# BMS.net
KiCad netlist of a schematic drawn in EAGLE
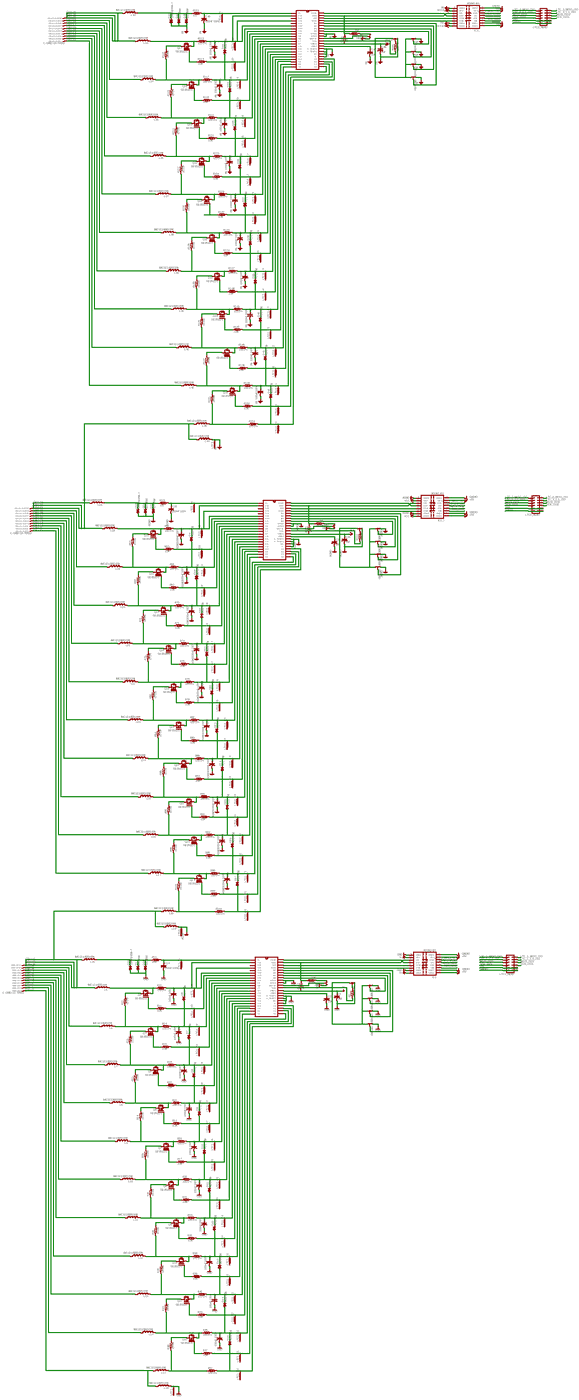
[diagram p0: schematic, sheet 1, overview]
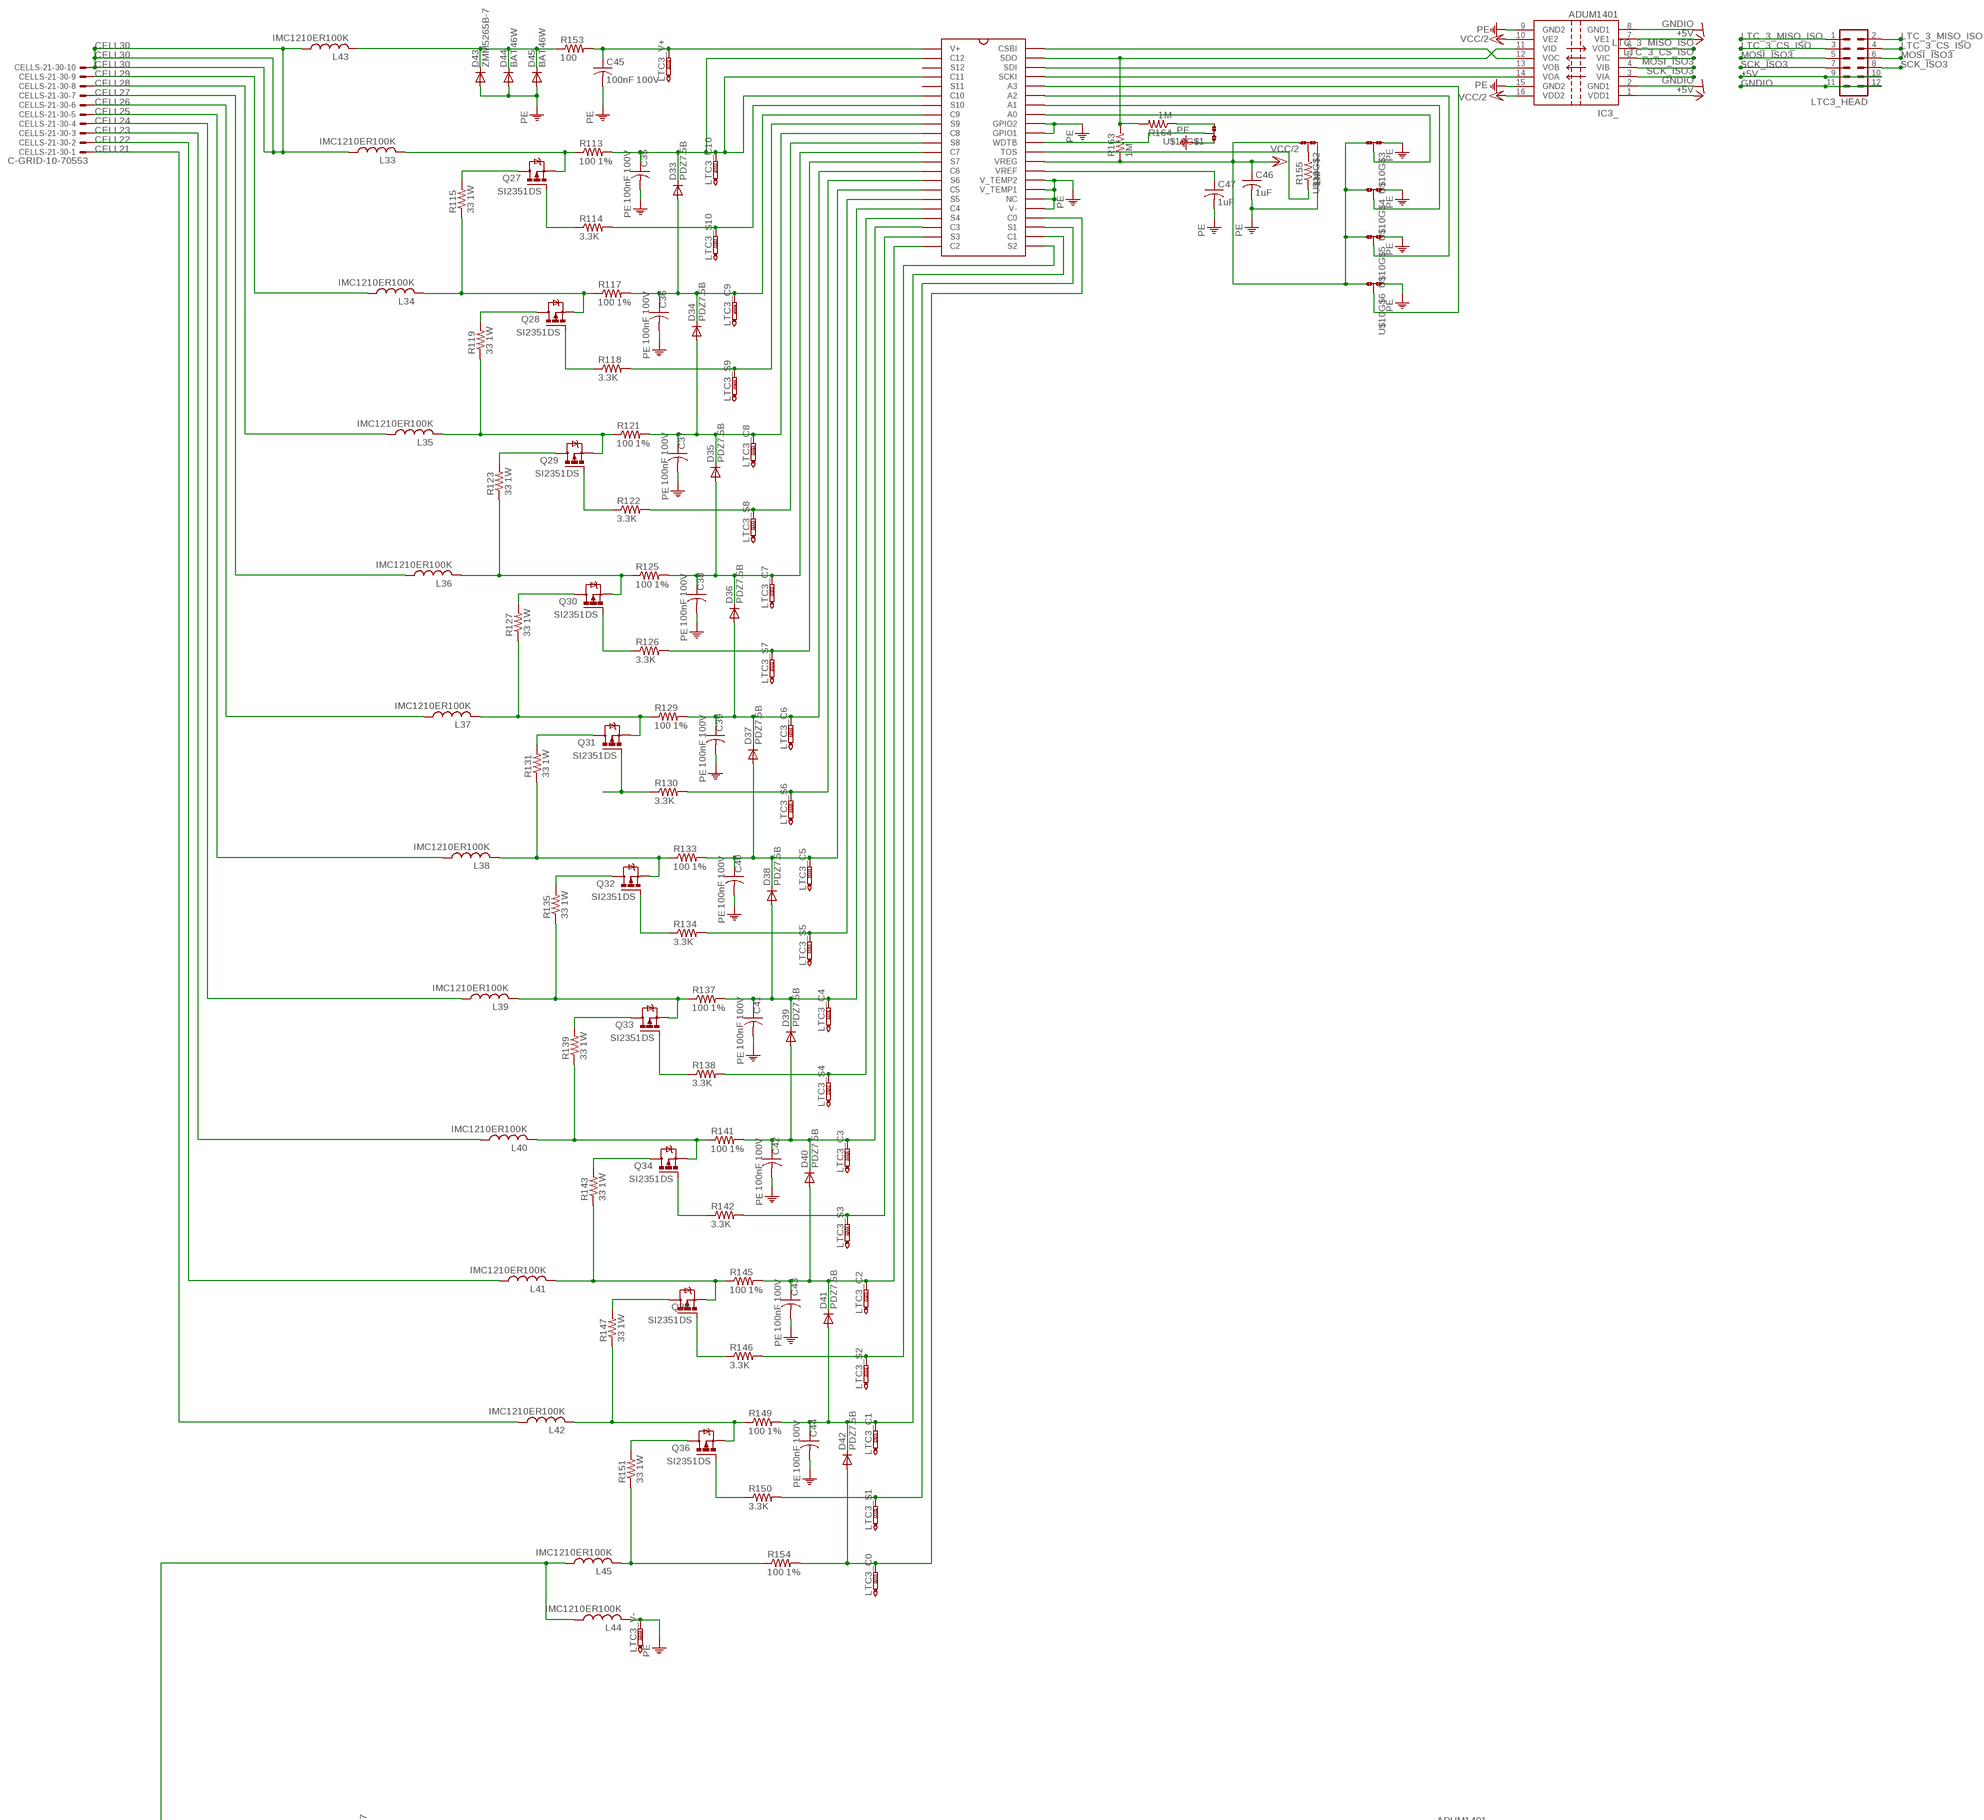
[diagram p1: schematic, sheet 1, part 1 of 4]
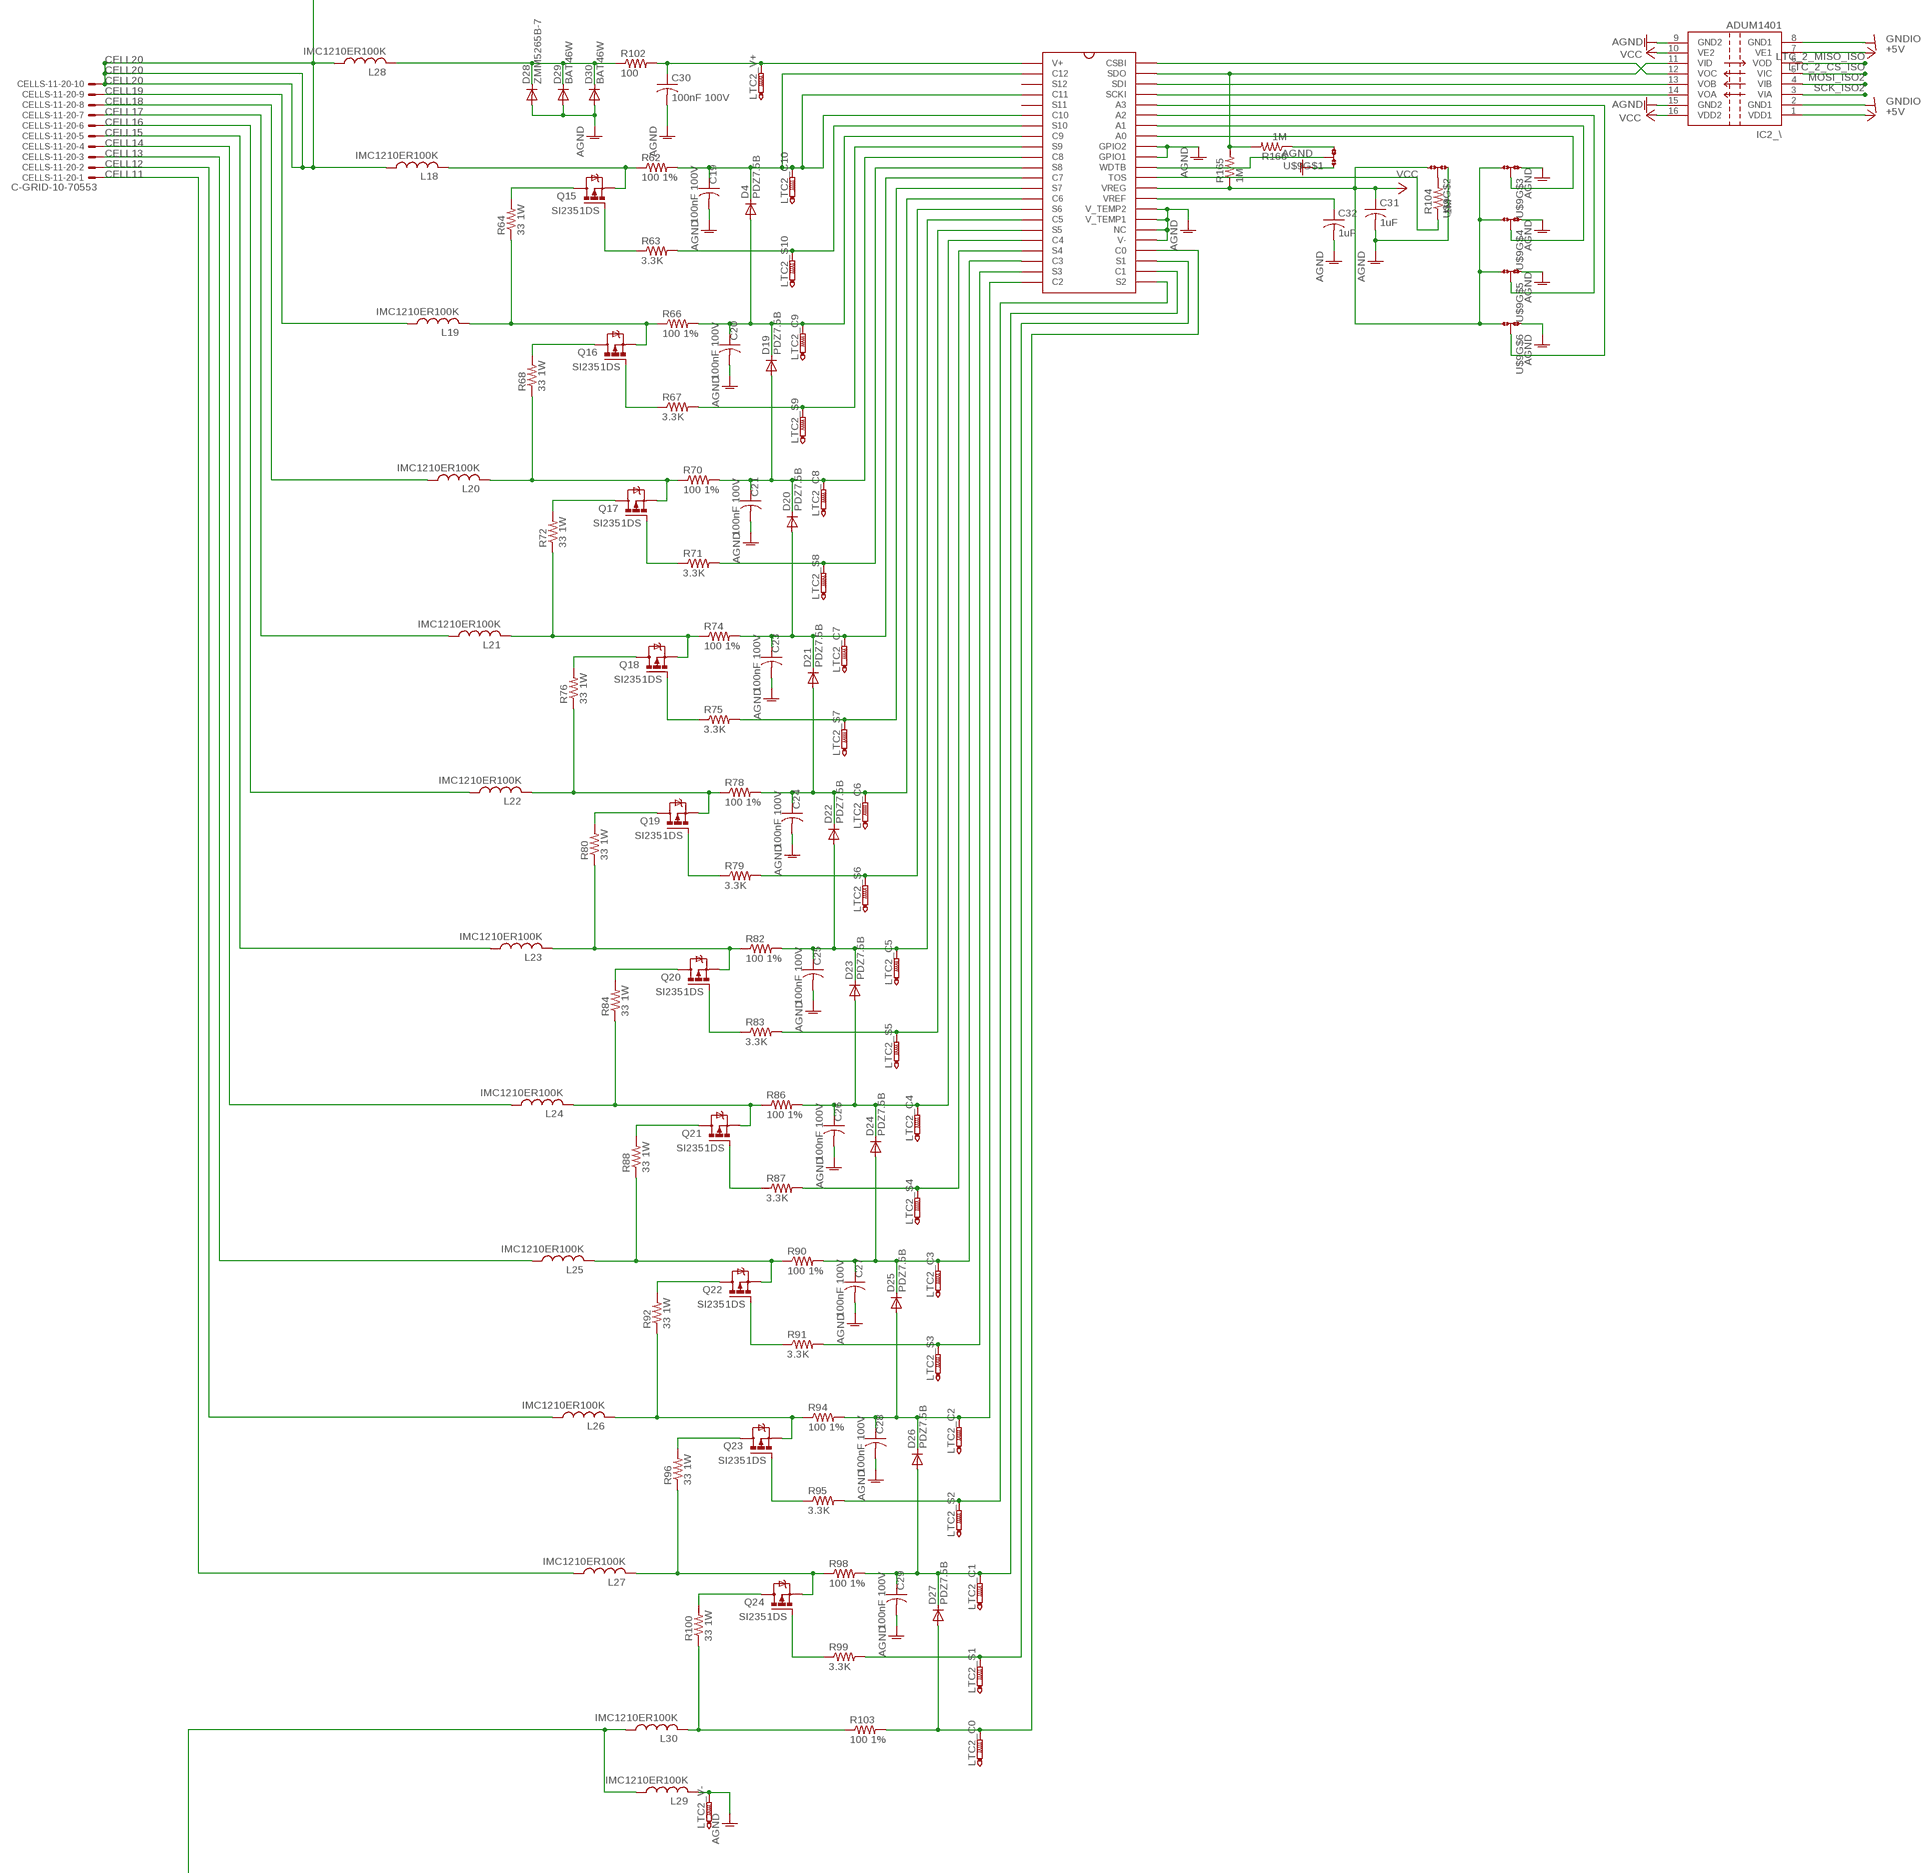
[diagram p2: schematic, sheet 1, part 2 of 4]
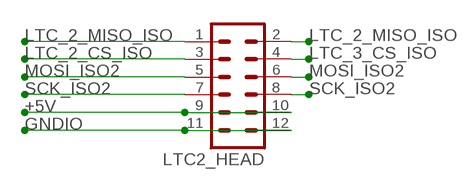
[diagram p3: schematic, sheet 1, part 3 of 4]
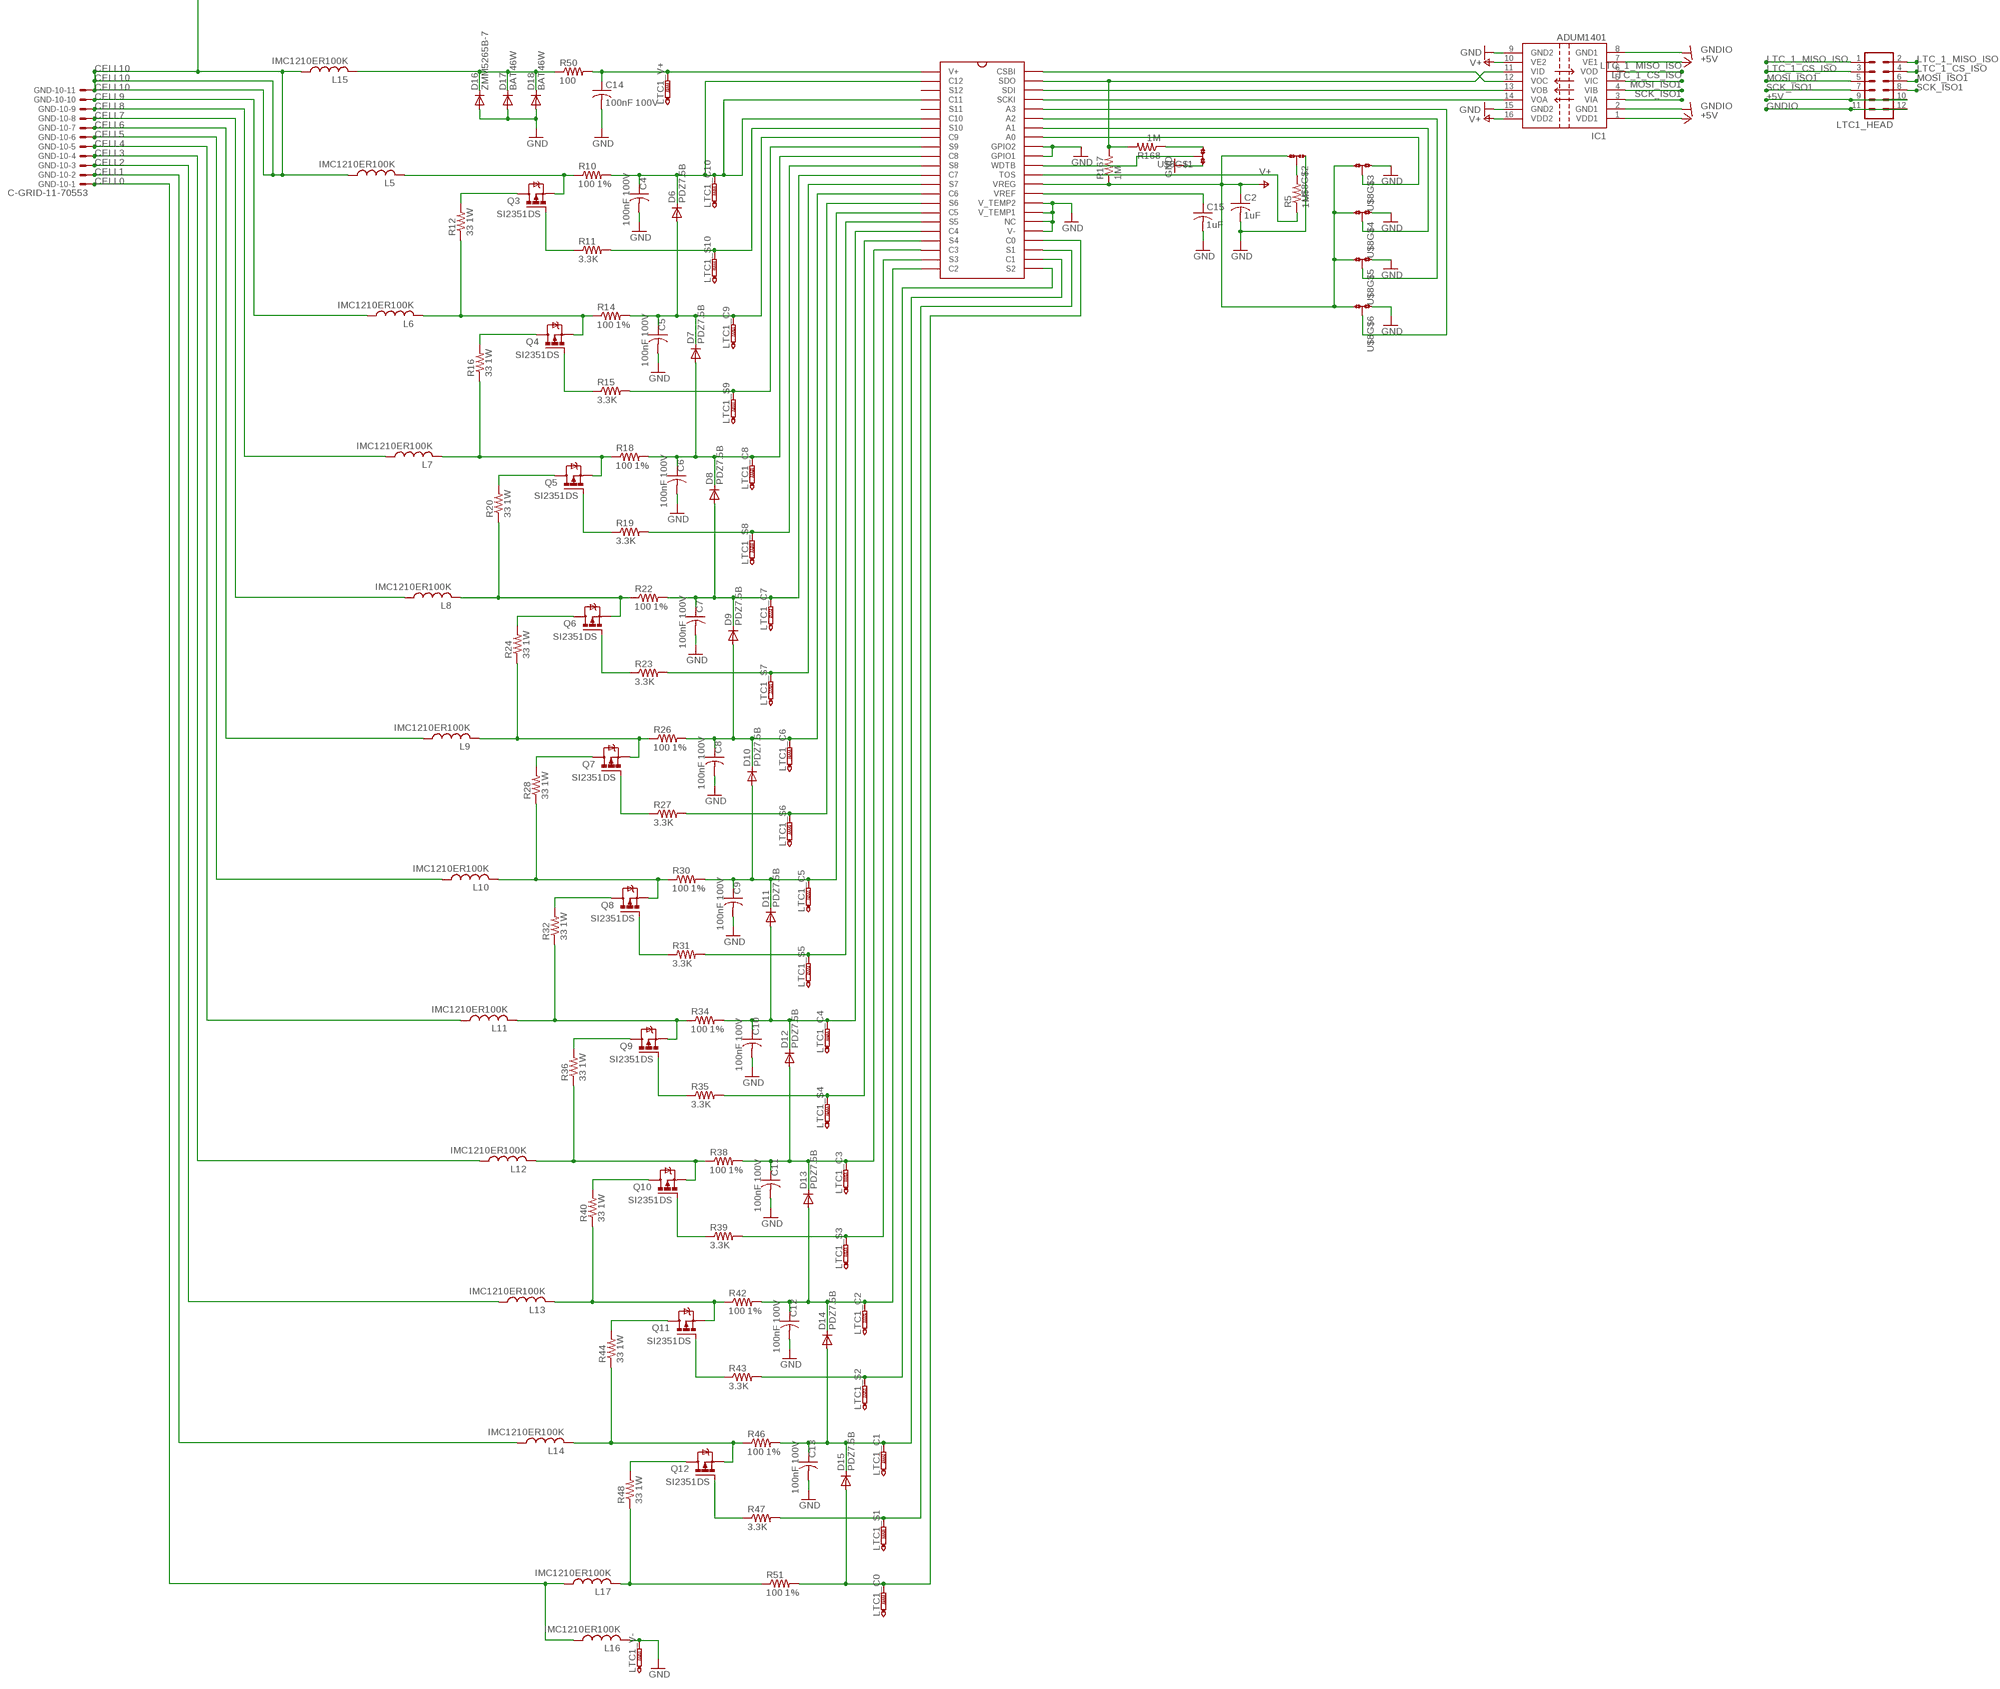
[diagram p4: schematic, sheet 1, part 4 of 4]
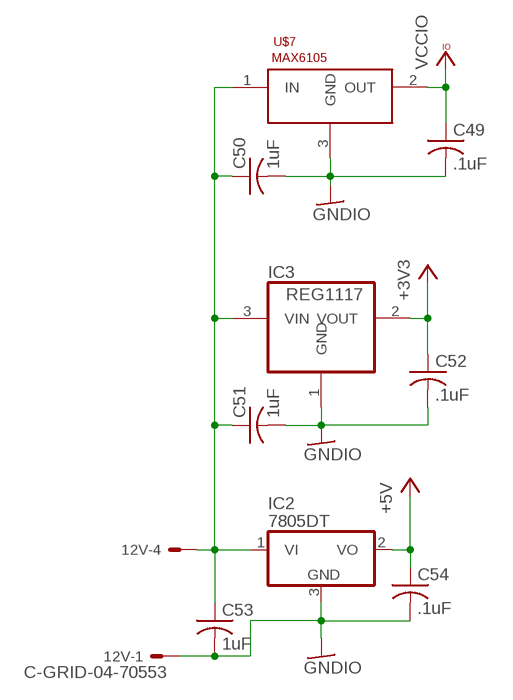
[diagram p5: schematic, sheet 2]
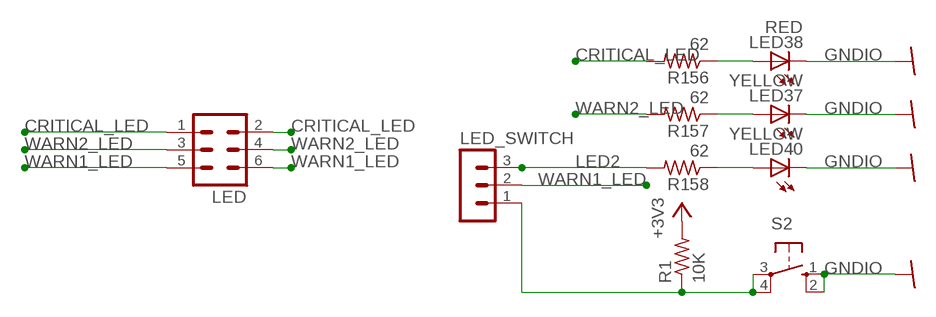
[diagram p6: schematic, sheet 3]
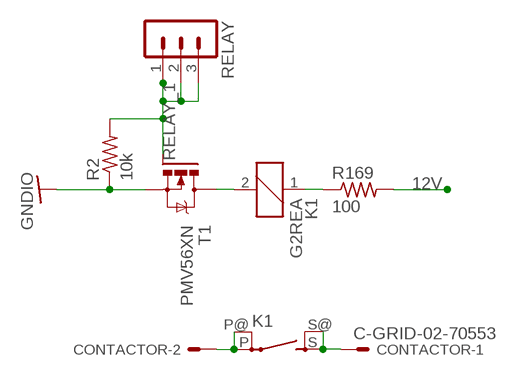
[diagram p7: schematic, sheet 4]
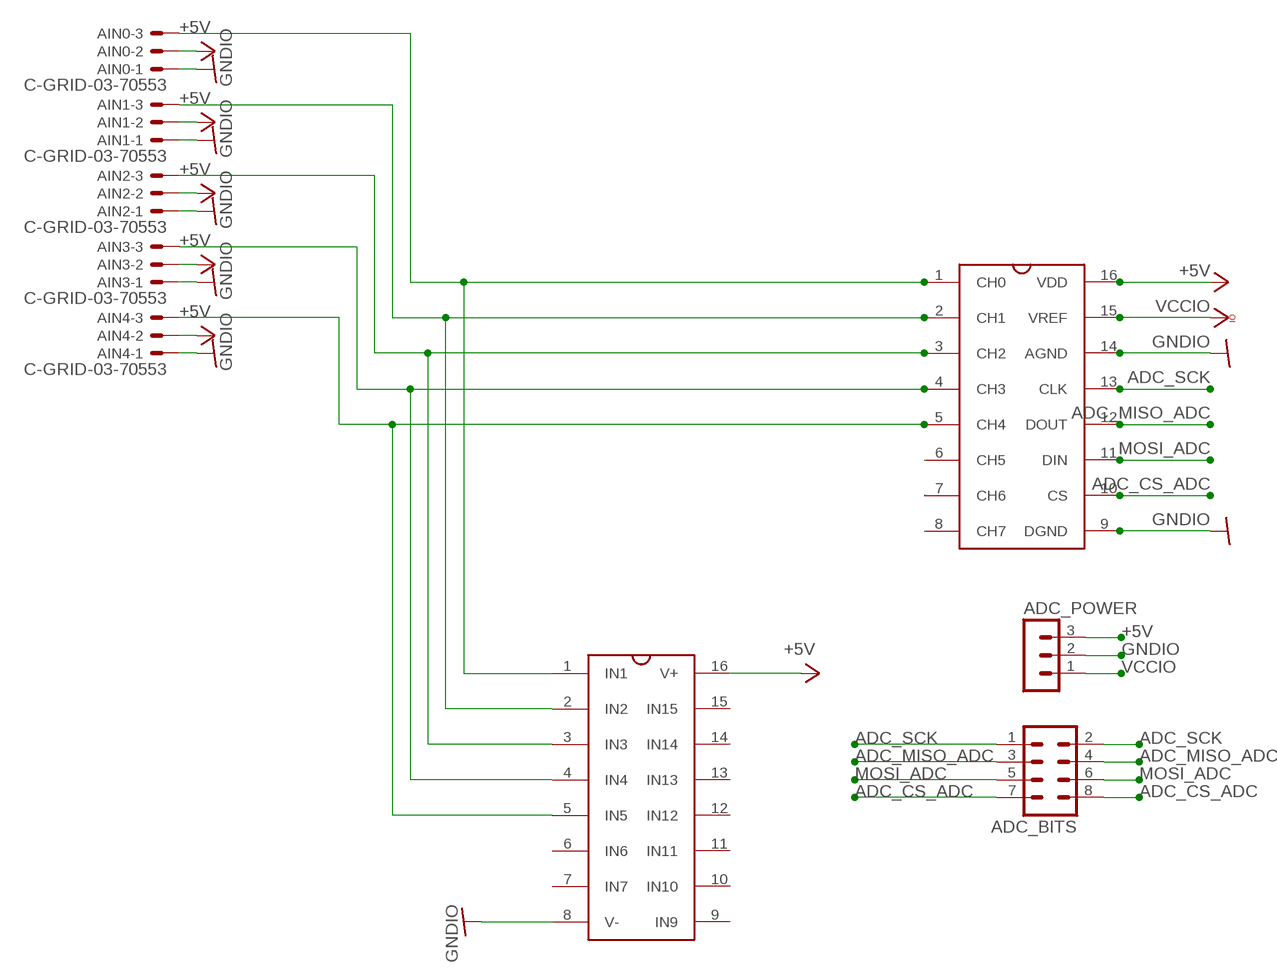
[diagram p8: schematic, sheet 5]
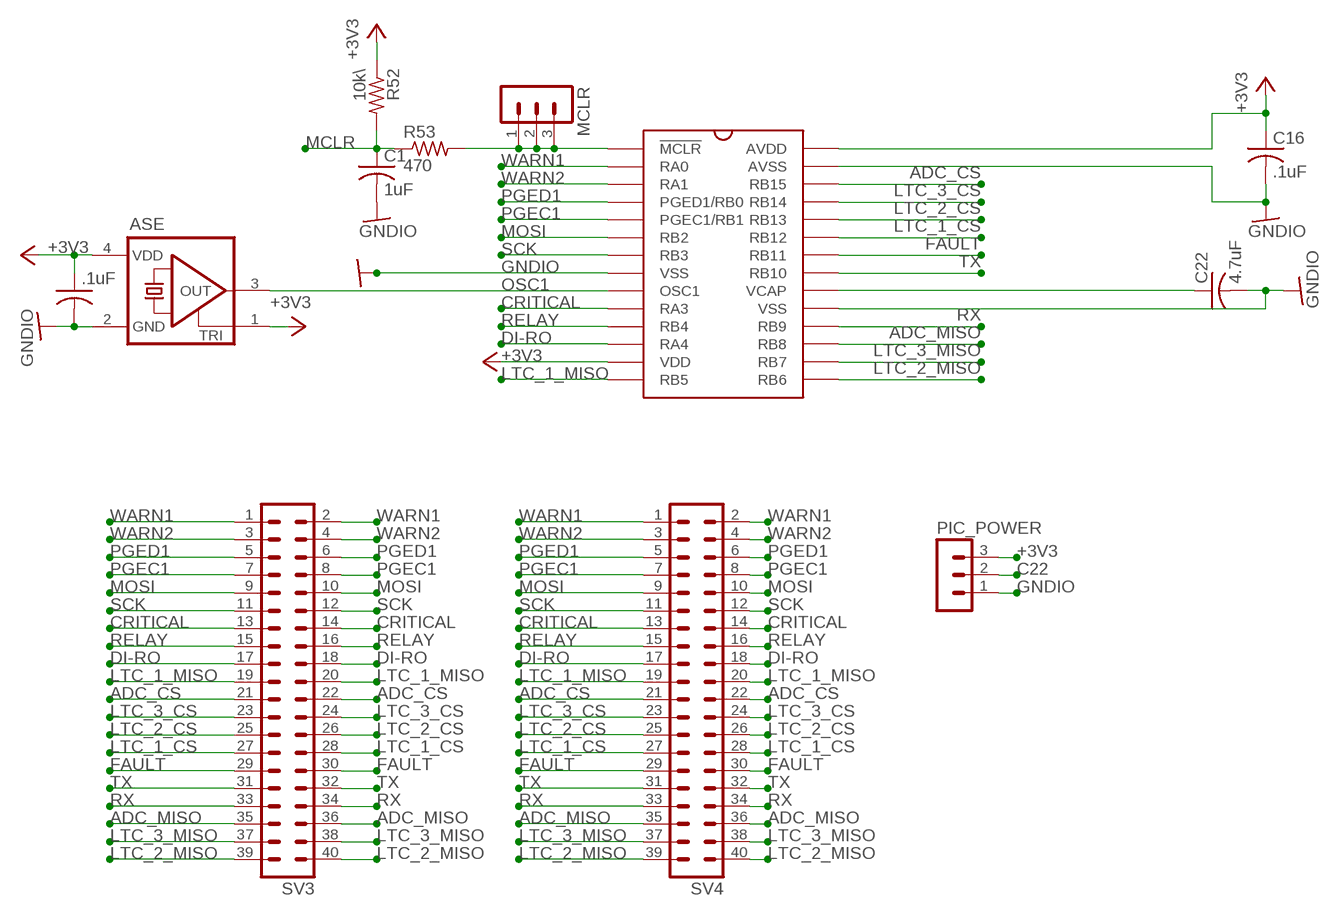
[diagram p9: schematic, sheet 6]
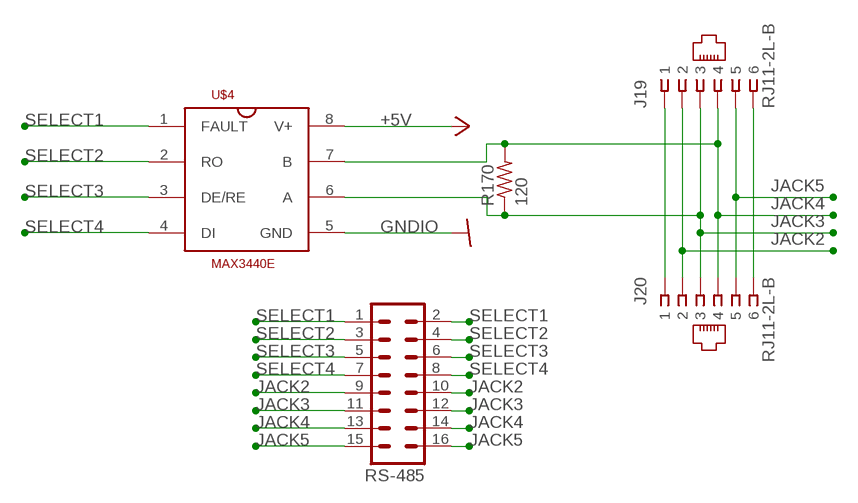
[diagram p10: schematic, sheet 7]
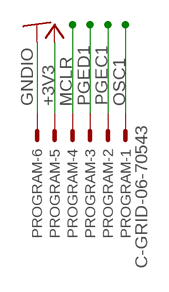
[diagram p11: schematic, sheet 8]

(export (version "E")
  (design (tool "Eeschema 10.0.6"))
  (components
    (comp (ref "C2")
      (value "1uF")
      (footprint "eagle-import:C1206")
      (libsource (lib "eagle-import") (part "C-USC1206"))
    )
    (comp (ref "C4")
      (value "100nF 100V")
      (footprint "eagle-import:C1206")
      (libsource (lib "eagle-import") (part "C-USC1206"))
    )
    (comp (ref "C5")
      (value "100nF 100V")
      (footprint "eagle-import:C1206")
      (libsource (lib "eagle-import") (part "C-USC1206"))
    )
    (comp (ref "C6")
      (value "100nF 100V")
      (footprint "eagle-import:C1206")
      (libsource (lib "eagle-import") (part "C-USC1206"))
    )
    (comp (ref "C7")
      (value "100nF 100V")
      (footprint "eagle-import:C1206")
      (libsource (lib "eagle-import") (part "C-USC1206"))
    )
    (comp (ref "C8")
      (value "100nF 100V")
      (footprint "eagle-import:C1206")
      (libsource (lib "eagle-import") (part "C-USC1206"))
    )
    (comp (ref "C9")
      (value "100nF 100V")
      (footprint "eagle-import:C1206")
      (libsource (lib "eagle-import") (part "C-USC1206"))
    )
    (comp (ref "C10")
      (value "100nF 100V")
      (footprint "eagle-import:C1206")
      (libsource (lib "eagle-import") (part "C-USC1206"))
    )
    (comp (ref "C11")
      (value "100nF 100V")
      (footprint "eagle-import:C1206")
      (libsource (lib "eagle-import") (part "C-USC1206"))
    )
    (comp (ref "C12")
      (value "100nF 100V")
      (footprint "eagle-import:C1206")
      (libsource (lib "eagle-import") (part "C-USC1206"))
    )
    (comp (ref "C13")
      (value "100nF 100V")
      (footprint "eagle-import:C1206")
      (libsource (lib "eagle-import") (part "C-USC1206"))
    )
    (comp (ref "C14")
      (value "100nF 100V")
      (footprint "eagle-import:C1206")
      (libsource (lib "eagle-import") (part "C-USC1206"))
    )
    (comp (ref "C15")
      (value "1uF")
      (footprint "eagle-import:C1206")
      (libsource (lib "eagle-import") (part "C-USC1206"))
    )
    (comp (ref "C19")
      (value "100nF 100V")
      (footprint "eagle-import:C1206")
      (libsource (lib "eagle-import") (part "C-USC1206"))
    )
    (comp (ref "C20")
      (value "100nF 100V")
      (footprint "eagle-import:C1206")
      (libsource (lib "eagle-import") (part "C-USC1206"))
    )
    (comp (ref "C21")
      (value "100nF 100V")
      (footprint "eagle-import:C1206")
      (libsource (lib "eagle-import") (part "C-USC1206"))
    )
    (comp (ref "C23")
      (value "100nF 100V")
      (footprint "eagle-import:C1206")
      (libsource (lib "eagle-import") (part "C-USC1206"))
    )
    (comp (ref "C24")
      (value "100nF 100V")
      (footprint "eagle-import:C1206")
      (libsource (lib "eagle-import") (part "C-USC1206"))
    )
    (comp (ref "C25")
      (value "100nF 100V")
      (footprint "eagle-import:C1206")
      (libsource (lib "eagle-import") (part "C-USC1206"))
    )
    (comp (ref "C26")
      (value "100nF 100V")
      (footprint "eagle-import:C1206")
      (libsource (lib "eagle-import") (part "C-USC1206"))
    )
    (comp (ref "C27")
      (value "100nF 100V")
      (footprint "eagle-import:C1206")
      (libsource (lib "eagle-import") (part "C-USC1206"))
    )
    (comp (ref "C28")
      (value "100nF 100V")
      (footprint "eagle-import:C1206")
      (libsource (lib "eagle-import") (part "C-USC1206"))
    )
    (comp (ref "C29")
      (value "100nF 100V")
      (footprint "eagle-import:C1206")
      (libsource (lib "eagle-import") (part "C-USC1206"))
    )
    (comp (ref "C30")
      (value "100nF 100V")
      (footprint "eagle-import:C1206")
      (libsource (lib "eagle-import") (part "C-USC1206"))
    )
    (comp (ref "C31")
      (value "1uF")
      (footprint "eagle-import:C1206")
      (libsource (lib "eagle-import") (part "C-USC1206"))
    )
    (comp (ref "C32")
      (value "1uF")
      (footprint "eagle-import:C1206")
      (libsource (lib "eagle-import") (part "C-USC1206"))
    )
    (comp (ref "C35")
      (value "100nF 100V")
      (footprint "eagle-import:C1206")
      (libsource (lib "eagle-import") (part "C-USC1206"))
    )
    (comp (ref "C36")
      (value "100nF 100V")
      (footprint "eagle-import:C1206")
      (libsource (lib "eagle-import") (part "C-USC1206"))
    )
    (comp (ref "C37")
      (value "100nF 100V")
      (footprint "eagle-import:C1206")
      (libsource (lib "eagle-import") (part "C-USC1206"))
    )
    (comp (ref "C38")
      (value "100nF 100V")
      (footprint "eagle-import:C1206")
      (libsource (lib "eagle-import") (part "C-USC1206"))
    )
    (comp (ref "C39")
      (value "100nF 100V")
      (footprint "eagle-import:C1206")
      (libsource (lib "eagle-import") (part "C-USC1206"))
    )
    (comp (ref "C40")
      (value "100nF 100V")
      (footprint "eagle-import:C1206")
      (libsource (lib "eagle-import") (part "C-USC1206"))
    )
    (comp (ref "C41")
      (value "100nF 100V")
      (footprint "eagle-import:C1206")
      (libsource (lib "eagle-import") (part "C-USC1206"))
    )
    (comp (ref "C42")
      (value "100nF 100V")
      (footprint "eagle-import:C1206")
      (libsource (lib "eagle-import") (part "C-USC1206"))
    )
    (comp (ref "C43")
      (value "100nF 100V")
      (footprint "eagle-import:C1206")
      (libsource (lib "eagle-import") (part "C-USC1206"))
    )
    (comp (ref "C44")
      (value "100nF 100V")
      (footprint "eagle-import:C1206")
      (libsource (lib "eagle-import") (part "C-USC1206"))
    )
    (comp (ref "C45")
      (value "100nF 100V")
      (footprint "eagle-import:C1206")
      (libsource (lib "eagle-import") (part "C-USC1206"))
    )
    (comp (ref "C46")
      (value "1uF")
      (footprint "eagle-import:C1206")
      (libsource (lib "eagle-import") (part "C-USC1206"))
    )
    (comp (ref "C47")
      (value "1uF")
      (footprint "eagle-import:C1206")
      (libsource (lib "eagle-import") (part "C-USC1206"))
    )
    (comp (ref "CELLS-11-20")
      (value "C-GRID-10-70553")
      (footprint "eagle-import:70553-10")
      (libsource (lib "eagle-import") (part "C-GRID-10-70553"))
    )
    (comp (ref "CELLS-21-30")
      (value "C-GRID-10-70553")
      (footprint "eagle-import:70553-10")
      (libsource (lib "eagle-import") (part "C-GRID-10-70553"))
    )
    (comp (ref "D4")
      (value "PDZ7.5B")
      (footprint "eagle-import:SOD323-W")
      (libsource (lib "eagle-import") (part "DIODE-SOD323-W"))
    )
    (comp (ref "D6")
      (value "PDZ7.5B")
      (footprint "eagle-import:SOD323-W")
      (libsource (lib "eagle-import") (part "DIODE-SOD323-W"))
    )
    (comp (ref "D7")
      (value "PDZ7.5B")
      (footprint "eagle-import:SOD323-W")
      (libsource (lib "eagle-import") (part "DIODE-SOD323-W"))
    )
    (comp (ref "D8")
      (value "PDZ7.5B")
      (footprint "eagle-import:SOD323-W")
      (libsource (lib "eagle-import") (part "DIODE-SOD323-W"))
    )
    (comp (ref "D9")
      (value "PDZ7.5B")
      (footprint "eagle-import:SOD323-W")
      (libsource (lib "eagle-import") (part "DIODE-SOD323-W"))
    )
    (comp (ref "D10")
      (value "PDZ7.5B")
      (footprint "eagle-import:SOD323-W")
      (libsource (lib "eagle-import") (part "DIODE-SOD323-W"))
    )
    (comp (ref "D11")
      (value "PDZ7.5B")
      (footprint "eagle-import:SOD323-W")
      (libsource (lib "eagle-import") (part "DIODE-SOD323-W"))
    )
    (comp (ref "D12")
      (value "PDZ7.5B")
      (footprint "eagle-import:SOD323-W")
      (libsource (lib "eagle-import") (part "DIODE-SOD323-W"))
    )
    (comp (ref "D13")
      (value "PDZ7.5B")
      (footprint "eagle-import:SOD323-W")
      (libsource (lib "eagle-import") (part "DIODE-SOD323-W"))
    )
    (comp (ref "D14")
      (value "PDZ7.5B")
      (footprint "eagle-import:SOD323-W")
      (libsource (lib "eagle-import") (part "DIODE-SOD323-W"))
    )
    (comp (ref "D15")
      (value "PDZ7.5B")
      (footprint "eagle-import:SOD323-W")
      (libsource (lib "eagle-import") (part "DIODE-SOD323-W"))
    )
    (comp (ref "D16")
      (value "ZMM5265B-7")
      (footprint "eagle-import:MINIMELF")
      (libsource (lib "eagle-import") (part "DIODE-MINIMELF"))
    )
    (comp (ref "D17")
      (value "BAT46W")
      (footprint "eagle-import:SOD123")
      (libsource (lib "eagle-import") (part "DIODE-SOD123"))
    )
    (comp (ref "D18")
      (value "BAT46W")
      (footprint "eagle-import:SOD123")
      (libsource (lib "eagle-import") (part "DIODE-SOD123"))
    )
    (comp (ref "D19")
      (value "PDZ7.5B")
      (footprint "eagle-import:SOD323-W")
      (libsource (lib "eagle-import") (part "DIODE-SOD323-W"))
    )
    (comp (ref "D20")
      (value "PDZ7.5B")
      (footprint "eagle-import:SOD323-W")
      (libsource (lib "eagle-import") (part "DIODE-SOD323-W"))
    )
    (comp (ref "D21")
      (value "PDZ7.5B")
      (footprint "eagle-import:SOD323-W")
      (libsource (lib "eagle-import") (part "DIODE-SOD323-W"))
    )
    (comp (ref "D22")
      (value "PDZ7.5B")
      (footprint "eagle-import:SOD323-W")
      (libsource (lib "eagle-import") (part "DIODE-SOD323-W"))
    )
    (comp (ref "D23")
      (value "PDZ7.5B")
      (footprint "eagle-import:SOD323-W")
      (libsource (lib "eagle-import") (part "DIODE-SOD323-W"))
    )
    (comp (ref "D24")
      (value "PDZ7.5B")
      (footprint "eagle-import:SOD323-W")
      (libsource (lib "eagle-import") (part "DIODE-SOD323-W"))
    )
    (comp (ref "D25")
      (value "PDZ7.5B")
      (footprint "eagle-import:SOD323-W")
      (libsource (lib "eagle-import") (part "DIODE-SOD323-W"))
    )
    (comp (ref "D26")
      (value "PDZ7.5B")
      (footprint "eagle-import:SOD323-W")
      (libsource (lib "eagle-import") (part "DIODE-SOD323-W"))
    )
    (comp (ref "D27")
      (value "PDZ7.5B")
      (footprint "eagle-import:SOD323-W")
      (libsource (lib "eagle-import") (part "DIODE-SOD323-W"))
    )
    (comp (ref "D28")
      (value "ZMM5265B-7")
      (footprint "eagle-import:MINIMELF")
      (libsource (lib "eagle-import") (part "DIODE-MINIMELF"))
    )
    (comp (ref "D29")
      (value "BAT46W")
      (footprint "eagle-import:SOD123")
      (libsource (lib "eagle-import") (part "DIODE-SOD123"))
    )
    (comp (ref "D30")
      (value "BAT46W")
      (footprint "eagle-import:SOD123")
      (libsource (lib "eagle-import") (part "DIODE-SOD123"))
    )
    (comp (ref "D33")
      (value "PDZ7.5B")
      (footprint "eagle-import:SOD323-W")
      (libsource (lib "eagle-import") (part "DIODE-SOD323-W"))
    )
    (comp (ref "D34")
      (value "PDZ7.5B")
      (footprint "eagle-import:SOD323-W")
      (libsource (lib "eagle-import") (part "DIODE-SOD323-W"))
    )
    (comp (ref "D35")
      (value "PDZ7.5B")
      (footprint "eagle-import:SOD323-W")
      (libsource (lib "eagle-import") (part "DIODE-SOD323-W"))
    )
    (comp (ref "D36")
      (value "PDZ7.5B")
      (footprint "eagle-import:SOD323-W")
      (libsource (lib "eagle-import") (part "DIODE-SOD323-W"))
    )
    (comp (ref "D37")
      (value "PDZ7.5B")
      (footprint "eagle-import:SOD323-W")
      (libsource (lib "eagle-import") (part "DIODE-SOD323-W"))
    )
    (comp (ref "D38")
      (value "PDZ7.5B")
      (footprint "eagle-import:SOD323-W")
      (libsource (lib "eagle-import") (part "DIODE-SOD323-W"))
    )
    (comp (ref "D39")
      (value "PDZ7.5B")
      (footprint "eagle-import:SOD323-W")
      (libsource (lib "eagle-import") (part "DIODE-SOD323-W"))
    )
    (comp (ref "D40")
      (value "PDZ7.5B")
      (footprint "eagle-import:SOD323-W")
      (libsource (lib "eagle-import") (part "DIODE-SOD323-W"))
    )
    (comp (ref "D41")
      (value "PDZ7.5B")
      (footprint "eagle-import:SOD323-W")
      (libsource (lib "eagle-import") (part "DIODE-SOD323-W"))
    )
    (comp (ref "D42")
      (value "PDZ7.5B")
      (footprint "eagle-import:SOD323-W")
      (libsource (lib "eagle-import") (part "DIODE-SOD323-W"))
    )
    (comp (ref "D43")
      (value "ZMM5265B-7")
      (footprint "eagle-import:MINIMELF")
      (libsource (lib "eagle-import") (part "DIODE-MINIMELF"))
    )
    (comp (ref "D44")
      (value "BAT46W")
      (footprint "eagle-import:SOD123")
      (libsource (lib "eagle-import") (part "DIODE-SOD123"))
    )
    (comp (ref "D45")
      (value "BAT46W")
      (footprint "eagle-import:SOD123")
      (libsource (lib "eagle-import") (part "DIODE-SOD123"))
    )
    (comp (ref "GND-10")
      (value "C-GRID-11-70553")
      (footprint "eagle-import:70553-11")
      (libsource (lib "eagle-import") (part "C-GRID-11-70553"))
    )
    (comp (ref "IC1")
      (value "ADUM1401")
      (footprint "eagle-import:SO16W")
      (libsource (lib "eagle-import") (part "ADUM1401"))
    )
    (comp (ref "IC2_\\")
      (value "ADUM1401")
      (footprint "eagle-import:SO16W")
      (libsource (lib "eagle-import") (part "ADUM1401"))
    )
    (comp (ref "IC3_")
      (value "ADUM1401")
      (footprint "eagle-import:SO16W")
      (libsource (lib "eagle-import") (part "ADUM1401"))
    )
    (comp (ref "L5")
      (value "IMC1210ER100K")
      (footprint "eagle-import:L3225M")
      (libsource (lib "eagle-import") (part "L-USL3225M"))
    )
    (comp (ref "L6")
      (value "IMC1210ER100K")
      (footprint "eagle-import:L3225M")
      (libsource (lib "eagle-import") (part "L-USL3225M"))
    )
    (comp (ref "L7")
      (value "IMC1210ER100K")
      (footprint "eagle-import:L3225M")
      (libsource (lib "eagle-import") (part "L-USL3225M"))
    )
    (comp (ref "L8")
      (value "IMC1210ER100K")
      (footprint "eagle-import:L3225M")
      (libsource (lib "eagle-import") (part "L-USL3225M"))
    )
    (comp (ref "L9")
      (value "IMC1210ER100K")
      (footprint "eagle-import:L3225M")
      (libsource (lib "eagle-import") (part "L-USL3225M"))
    )
    (comp (ref "L10")
      (value "IMC1210ER100K")
      (footprint "eagle-import:L3225M")
      (libsource (lib "eagle-import") (part "L-USL3225M"))
    )
    (comp (ref "L11")
      (value "IMC1210ER100K")
      (footprint "eagle-import:L3225M")
      (libsource (lib "eagle-import") (part "L-USL3225M"))
    )
    (comp (ref "L12")
      (value "IMC1210ER100K")
      (footprint "eagle-import:L3225M")
      (libsource (lib "eagle-import") (part "L-USL3225M"))
    )
    (comp (ref "L13")
      (value "IMC1210ER100K")
      (footprint "eagle-import:L3225M")
      (libsource (lib "eagle-import") (part "L-USL3225M"))
    )
    (comp (ref "L14")
      (value "IMC1210ER100K")
      (footprint "eagle-import:L3225M")
      (libsource (lib "eagle-import") (part "L-USL3225M"))
    )
    (comp (ref "L15")
      (value "IMC1210ER100K")
      (footprint "eagle-import:L3225M")
      (libsource (lib "eagle-import") (part "L-USL3225M"))
    )
    (comp (ref "L16")
      (value "IMC1210ER100K")
      (footprint "eagle-import:L3225M")
      (libsource (lib "eagle-import") (part "L-USL3225M"))
    )
    (comp (ref "L17")
      (value "IMC1210ER100K")
      (footprint "eagle-import:L3225M")
      (libsource (lib "eagle-import") (part "L-USL3225M"))
    )
    (comp (ref "L18")
      (value "IMC1210ER100K")
      (footprint "eagle-import:L3225M")
      (libsource (lib "eagle-import") (part "L-USL3225M"))
    )
    (comp (ref "L19")
      (value "IMC1210ER100K")
      (footprint "eagle-import:L3225M")
      (libsource (lib "eagle-import") (part "L-USL3225M"))
    )
    (comp (ref "L20")
      (value "IMC1210ER100K")
      (footprint "eagle-import:L3225M")
      (libsource (lib "eagle-import") (part "L-USL3225M"))
    )
    (comp (ref "L21")
      (value "IMC1210ER100K")
      (footprint "eagle-import:L3225M")
      (libsource (lib "eagle-import") (part "L-USL3225M"))
    )
    (comp (ref "L22")
      (value "IMC1210ER100K")
      (footprint "eagle-import:L3225M")
      (libsource (lib "eagle-import") (part "L-USL3225M"))
    )
    (comp (ref "L23")
      (value "IMC1210ER100K")
      (footprint "eagle-import:L3225M")
      (libsource (lib "eagle-import") (part "L-USL3225M"))
    )
    (comp (ref "L24")
      (value "IMC1210ER100K")
      (footprint "eagle-import:L3225M")
      (libsource (lib "eagle-import") (part "L-USL3225M"))
    )
    (comp (ref "L25")
      (value "IMC1210ER100K")
      (footprint "eagle-import:L3225M")
      (libsource (lib "eagle-import") (part "L-USL3225M"))
    )
    (comp (ref "L26")
      (value "IMC1210ER100K")
      (footprint "eagle-import:L3225M")
      (libsource (lib "eagle-import") (part "L-USL3225M"))
    )
    (comp (ref "L27")
      (value "IMC1210ER100K")
      (footprint "eagle-import:L3225M")
      (libsource (lib "eagle-import") (part "L-USL3225M"))
    )
    (comp (ref "L28")
      (value "IMC1210ER100K")
      (footprint "eagle-import:L3225M")
      (libsource (lib "eagle-import") (part "L-USL3225M"))
    )
    (comp (ref "L29")
      (value "IMC1210ER100K")
      (footprint "eagle-import:L3225M")
      (libsource (lib "eagle-import") (part "L-USL3225M"))
    )
    (comp (ref "L30")
      (value "IMC1210ER100K")
      (footprint "eagle-import:L3225M")
      (libsource (lib "eagle-import") (part "L-USL3225M"))
    )
    (comp (ref "L33")
      (value "IMC1210ER100K")
      (footprint "eagle-import:L3225M")
      (libsource (lib "eagle-import") (part "L-USL3225M"))
    )
    (comp (ref "L34")
      (value "IMC1210ER100K")
      (footprint "eagle-import:L3225M")
      (libsource (lib "eagle-import") (part "L-USL3225M"))
    )
    (comp (ref "L35")
      (value "IMC1210ER100K")
      (footprint "eagle-import:L3225M")
      (libsource (lib "eagle-import") (part "L-USL3225M"))
    )
    (comp (ref "L36")
      (value "IMC1210ER100K")
      (footprint "eagle-import:L3225M")
      (libsource (lib "eagle-import") (part "L-USL3225M"))
    )
    (comp (ref "L37")
      (value "IMC1210ER100K")
      (footprint "eagle-import:L3225M")
      (libsource (lib "eagle-import") (part "L-USL3225M"))
    )
    (comp (ref "L38")
      (value "IMC1210ER100K")
      (footprint "eagle-import:L3225M")
      (libsource (lib "eagle-import") (part "L-USL3225M"))
    )
    (comp (ref "L39")
      (value "IMC1210ER100K")
      (footprint "eagle-import:L3225M")
      (libsource (lib "eagle-import") (part "L-USL3225M"))
    )
    (comp (ref "L40")
      (value "IMC1210ER100K")
      (footprint "eagle-import:L3225M")
      (libsource (lib "eagle-import") (part "L-USL3225M"))
    )
    (comp (ref "L41")
      (value "IMC1210ER100K")
      (footprint "eagle-import:L3225M")
      (libsource (lib "eagle-import") (part "L-USL3225M"))
    )
    (comp (ref "L42")
      (value "IMC1210ER100K")
      (footprint "eagle-import:L3225M")
      (libsource (lib "eagle-import") (part "L-USL3225M"))
    )
    (comp (ref "L43")
      (value "IMC1210ER100K")
      (footprint "eagle-import:L3225M")
      (libsource (lib "eagle-import") (part "L-USL3225M"))
    )
    (comp (ref "L44")
      (value "IMC1210ER100K")
      (footprint "eagle-import:L3225M")
      (libsource (lib "eagle-import") (part "L-USL3225M"))
    )
    (comp (ref "L45")
      (value "IMC1210ER100K")
      (footprint "eagle-import:L3225M")
      (libsource (lib "eagle-import") (part "L-USL3225M"))
    )
    (comp (ref "LTC1")
      (value "LTC6803-4")
      (footprint "eagle-import:SSOP44")
      (libsource (lib "eagle-import") (part "LTC6803-4"))
    )
    (comp (ref "LTC1_C0")
      (value "TESTPAD-20MIL")
      (footprint "eagle-import:20MIL")
      (libsource (lib "eagle-import") (part "TESTPAD-20MIL"))
    )
    (comp (ref "LTC1_C1")
      (value "TESTPAD-20MIL")
      (footprint "eagle-import:20MIL")
      (libsource (lib "eagle-import") (part "TESTPAD-20MIL"))
    )
    (comp (ref "LTC1_C2")
      (value "TESTPAD-20MIL")
      (footprint "eagle-import:20MIL")
      (libsource (lib "eagle-import") (part "TESTPAD-20MIL"))
    )
    (comp (ref "LTC1_C3")
      (value "TESTPAD-20MIL")
      (footprint "eagle-import:20MIL")
      (libsource (lib "eagle-import") (part "TESTPAD-20MIL"))
    )
    (comp (ref "LTC1_C4")
      (value "TESTPAD-20MIL")
      (footprint "eagle-import:20MIL")
      (libsource (lib "eagle-import") (part "TESTPAD-20MIL"))
    )
    (comp (ref "LTC1_C5")
      (value "TESTPAD-20MIL")
      (footprint "eagle-import:20MIL")
      (libsource (lib "eagle-import") (part "TESTPAD-20MIL"))
    )
    (comp (ref "LTC1_C6")
      (value "TESTPAD-20MIL")
      (footprint "eagle-import:20MIL")
      (libsource (lib "eagle-import") (part "TESTPAD-20MIL"))
    )
    (comp (ref "LTC1_C7")
      (value "TESTPAD-20MIL")
      (footprint "eagle-import:20MIL")
      (libsource (lib "eagle-import") (part "TESTPAD-20MIL"))
    )
    (comp (ref "LTC1_C8")
      (value "TESTPAD-20MIL")
      (footprint "eagle-import:20MIL")
      (libsource (lib "eagle-import") (part "TESTPAD-20MIL"))
    )
    (comp (ref "LTC1_C9")
      (value "TESTPAD-20MIL")
      (footprint "eagle-import:20MIL")
      (libsource (lib "eagle-import") (part "TESTPAD-20MIL"))
    )
    (comp (ref "LTC1_C10")
      (value "TESTPAD-20MIL")
      (footprint "eagle-import:20MIL")
      (libsource (lib "eagle-import") (part "TESTPAD-20MIL"))
    )
    (comp (ref "LTC1_HEAD")
      (value "MA06-2")
      (footprint "eagle-import:MA06-2")
      (libsource (lib "eagle-import") (part "MA06-2"))
    )
    (comp (ref "LTC1_S1")
      (value "TESTPAD-20MIL")
      (footprint "eagle-import:20MIL")
      (libsource (lib "eagle-import") (part "TESTPAD-20MIL"))
    )
    (comp (ref "LTC1_S2")
      (value "TESTPAD-20MIL")
      (footprint "eagle-import:20MIL")
      (libsource (lib "eagle-import") (part "TESTPAD-20MIL"))
    )
    (comp (ref "LTC1_S3")
      (value "TESTPAD-20MIL")
      (footprint "eagle-import:20MIL")
      (libsource (lib "eagle-import") (part "TESTPAD-20MIL"))
    )
    (comp (ref "LTC1_S4")
      (value "TESTPAD-20MIL")
      (footprint "eagle-import:20MIL")
      (libsource (lib "eagle-import") (part "TESTPAD-20MIL"))
    )
    (comp (ref "LTC1_S5")
      (value "TESTPAD-20MIL")
      (footprint "eagle-import:20MIL")
      (libsource (lib "eagle-import") (part "TESTPAD-20MIL"))
    )
    (comp (ref "LTC1_S6")
      (value "TESTPAD-20MIL")
      (footprint "eagle-import:20MIL")
      (libsource (lib "eagle-import") (part "TESTPAD-20MIL"))
    )
    (comp (ref "LTC1_S7")
      (value "TESTPAD-20MIL")
      (footprint "eagle-import:20MIL")
      (libsource (lib "eagle-import") (part "TESTPAD-20MIL"))
    )
    (comp (ref "LTC1_S8")
      (value "TESTPAD-20MIL")
      (footprint "eagle-import:20MIL")
      (libsource (lib "eagle-import") (part "TESTPAD-20MIL"))
    )
    (comp (ref "LTC1_S9")
      (value "TESTPAD-20MIL")
      (footprint "eagle-import:20MIL")
      (libsource (lib "eagle-import") (part "TESTPAD-20MIL"))
    )
    (comp (ref "LTC1_S10")
      (value "TESTPAD-20MIL")
      (footprint "eagle-import:20MIL")
      (libsource (lib "eagle-import") (part "TESTPAD-20MIL"))
    )
    (comp (ref "LTC1_V+")
      (value "TESTPAD-20MIL")
      (footprint "eagle-import:20MIL")
      (libsource (lib "eagle-import") (part "TESTPAD-20MIL"))
    )
    (comp (ref "LTC1_V-")
      (value "TESTPAD-20MIL")
      (footprint "eagle-import:20MIL")
      (libsource (lib "eagle-import") (part "TESTPAD-20MIL"))
    )
    (comp (ref "LTC2")
      (value "LTC6803-4")
      (footprint "eagle-import:SSOP44")
      (libsource (lib "eagle-import") (part "LTC6803-4"))
    )
    (comp (ref "LTC2_C0")
      (value "TESTPAD-20MIL")
      (footprint "eagle-import:20MIL")
      (libsource (lib "eagle-import") (part "TESTPAD-20MIL"))
    )
    (comp (ref "LTC2_C1")
      (value "TESTPAD-20MIL")
      (footprint "eagle-import:20MIL")
      (libsource (lib "eagle-import") (part "TESTPAD-20MIL"))
    )
    (comp (ref "LTC2_C2")
      (value "TESTPAD-20MIL")
      (footprint "eagle-import:20MIL")
      (libsource (lib "eagle-import") (part "TESTPAD-20MIL"))
    )
    (comp (ref "LTC2_C3")
      (value "TESTPAD-20MIL")
      (footprint "eagle-import:20MIL")
      (libsource (lib "eagle-import") (part "TESTPAD-20MIL"))
    )
    (comp (ref "LTC2_C4")
      (value "TESTPAD-20MIL")
      (footprint "eagle-import:20MIL")
      (libsource (lib "eagle-import") (part "TESTPAD-20MIL"))
    )
    (comp (ref "LTC2_C5")
      (value "TESTPAD-20MIL")
      (footprint "eagle-import:20MIL")
      (libsource (lib "eagle-import") (part "TESTPAD-20MIL"))
    )
    (comp (ref "LTC2_C6")
      (value "TESTPAD-20MIL")
      (footprint "eagle-import:20MIL")
      (libsource (lib "eagle-import") (part "TESTPAD-20MIL"))
    )
    (comp (ref "LTC2_C7")
      (value "TESTPAD-20MIL")
      (footprint "eagle-import:20MIL")
      (libsource (lib "eagle-import") (part "TESTPAD-20MIL"))
    )
    (comp (ref "LTC2_C8")
      (value "TESTPAD-20MIL")
      (footprint "eagle-import:20MIL")
      (libsource (lib "eagle-import") (part "TESTPAD-20MIL"))
    )
    (comp (ref "LTC2_C9")
      (value "TESTPAD-20MIL")
      (footprint "eagle-import:20MIL")
      (libsource (lib "eagle-import") (part "TESTPAD-20MIL"))
    )
    (comp (ref "LTC2_C10")
      (value "TESTPAD-20MIL")
      (footprint "eagle-import:20MIL")
      (libsource (lib "eagle-import") (part "TESTPAD-20MIL"))
    )
    (comp (ref "LTC2_HEAD")
      (value "MA06-2")
      (footprint "eagle-import:MA06-2")
      (libsource (lib "eagle-import") (part "MA06-2"))
    )
    (comp (ref "LTC2_S1")
      (value "TESTPAD-20MIL")
      (footprint "eagle-import:20MIL")
      (libsource (lib "eagle-import") (part "TESTPAD-20MIL"))
    )
    (comp (ref "LTC2_S2")
      (value "TESTPAD-20MIL")
      (footprint "eagle-import:20MIL")
      (libsource (lib "eagle-import") (part "TESTPAD-20MIL"))
    )
    (comp (ref "LTC2_S3")
      (value "TESTPAD-20MIL")
      (footprint "eagle-import:20MIL")
      (libsource (lib "eagle-import") (part "TESTPAD-20MIL"))
    )
    (comp (ref "LTC2_S4")
      (value "TESTPAD-20MIL")
      (footprint "eagle-import:20MIL")
      (libsource (lib "eagle-import") (part "TESTPAD-20MIL"))
    )
    (comp (ref "LTC2_S5")
      (value "TESTPAD-20MIL")
      (footprint "eagle-import:20MIL")
      (libsource (lib "eagle-import") (part "TESTPAD-20MIL"))
    )
    (comp (ref "LTC2_S6")
      (value "TESTPAD-20MIL")
      (footprint "eagle-import:20MIL")
      (libsource (lib "eagle-import") (part "TESTPAD-20MIL"))
    )
    (comp (ref "LTC2_S7")
      (value "TESTPAD-20MIL")
      (footprint "eagle-import:20MIL")
      (libsource (lib "eagle-import") (part "TESTPAD-20MIL"))
    )
    (comp (ref "LTC2_S8")
      (value "TESTPAD-20MIL")
      (footprint "eagle-import:20MIL")
      (libsource (lib "eagle-import") (part "TESTPAD-20MIL"))
    )
    (comp (ref "LTC2_S9")
      (value "TESTPAD-20MIL")
      (footprint "eagle-import:20MIL")
      (libsource (lib "eagle-import") (part "TESTPAD-20MIL"))
    )
    (comp (ref "LTC2_S10")
      (value "TESTPAD-20MIL")
      (footprint "eagle-import:20MIL")
      (libsource (lib "eagle-import") (part "TESTPAD-20MIL"))
    )
    (comp (ref "LTC2_V+")
      (value "TESTPAD-20MIL")
      (footprint "eagle-import:20MIL")
      (libsource (lib "eagle-import") (part "TESTPAD-20MIL"))
    )
    (comp (ref "LTC2_V-")
      (value "TESTPAD-20MIL")
      (footprint "eagle-import:20MIL")
      (libsource (lib "eagle-import") (part "TESTPAD-20MIL"))
    )
    (comp (ref "LTC3")
      (value "LTC6803-4")
      (footprint "eagle-import:SSOP44")
      (libsource (lib "eagle-import") (part "LTC6803-4"))
    )
    (comp (ref "LTC3_C0")
      (value "TESTPAD-20MIL")
      (footprint "eagle-import:20MIL")
      (libsource (lib "eagle-import") (part "TESTPAD-20MIL"))
    )
    (comp (ref "LTC3_C1")
      (value "TESTPAD-20MIL")
      (footprint "eagle-import:20MIL")
      (libsource (lib "eagle-import") (part "TESTPAD-20MIL"))
    )
    (comp (ref "LTC3_C2")
      (value "TESTPAD-20MIL")
      (footprint "eagle-import:20MIL")
      (libsource (lib "eagle-import") (part "TESTPAD-20MIL"))
    )
    (comp (ref "LTC3_C3")
      (value "TESTPAD-20MIL")
      (footprint "eagle-import:20MIL")
      (libsource (lib "eagle-import") (part "TESTPAD-20MIL"))
    )
    (comp (ref "LTC3_C4")
      (value "TESTPAD-20MIL")
      (footprint "eagle-import:20MIL")
      (libsource (lib "eagle-import") (part "TESTPAD-20MIL"))
    )
    (comp (ref "LTC3_C5")
      (value "TESTPAD-20MIL")
      (footprint "eagle-import:20MIL")
      (libsource (lib "eagle-import") (part "TESTPAD-20MIL"))
    )
    (comp (ref "LTC3_C6")
      (value "TESTPAD-20MIL")
      (footprint "eagle-import:20MIL")
      (libsource (lib "eagle-import") (part "TESTPAD-20MIL"))
    )
    (comp (ref "LTC3_C7")
      (value "TESTPAD-20MIL")
      (footprint "eagle-import:20MIL")
      (libsource (lib "eagle-import") (part "TESTPAD-20MIL"))
    )
    (comp (ref "LTC3_C8")
      (value "TESTPAD-20MIL")
      (footprint "eagle-import:20MIL")
      (libsource (lib "eagle-import") (part "TESTPAD-20MIL"))
    )
    (comp (ref "LTC3_C9")
      (value "TESTPAD-20MIL")
      (footprint "eagle-import:20MIL")
      (libsource (lib "eagle-import") (part "TESTPAD-20MIL"))
    )
    (comp (ref "LTC3_C10")
      (value "TESTPAD-20MIL")
      (footprint "eagle-import:20MIL")
      (libsource (lib "eagle-import") (part "TESTPAD-20MIL"))
    )
    (comp (ref "LTC3_HEAD")
      (value "MA06-2")
      (footprint "eagle-import:MA06-2")
      (libsource (lib "eagle-import") (part "MA06-2"))
    )
    (comp (ref "LTC3_S1")
      (value "TESTPAD-20MIL")
      (footprint "eagle-import:20MIL")
      (libsource (lib "eagle-import") (part "TESTPAD-20MIL"))
    )
    (comp (ref "LTC3_S2")
      (value "TESTPAD-20MIL")
      (footprint "eagle-import:20MIL")
      (libsource (lib "eagle-import") (part "TESTPAD-20MIL"))
    )
    (comp (ref "LTC3_S3")
      (value "TESTPAD-20MIL")
      (footprint "eagle-import:20MIL")
      (libsource (lib "eagle-import") (part "TESTPAD-20MIL"))
    )
    (comp (ref "LTC3_S4")
      (value "TESTPAD-20MIL")
      (footprint "eagle-import:20MIL")
      (libsource (lib "eagle-import") (part "TESTPAD-20MIL"))
    )
    (comp (ref "LTC3_S5")
      (value "TESTPAD-20MIL")
      (footprint "eagle-import:20MIL")
      (libsource (lib "eagle-import") (part "TESTPAD-20MIL"))
    )
    (comp (ref "LTC3_S6")
      (value "TESTPAD-20MIL")
      (footprint "eagle-import:20MIL")
      (libsource (lib "eagle-import") (part "TESTPAD-20MIL"))
    )
    (comp (ref "LTC3_S7")
      (value "TESTPAD-20MIL")
      (footprint "eagle-import:20MIL")
      (libsource (lib "eagle-import") (part "TESTPAD-20MIL"))
    )
    (comp (ref "LTC3_S8")
      (value "TESTPAD-20MIL")
      (footprint "eagle-import:20MIL")
      (libsource (lib "eagle-import") (part "TESTPAD-20MIL"))
    )
    (comp (ref "LTC3_S9")
      (value "TESTPAD-20MIL")
      (footprint "eagle-import:20MIL")
      (libsource (lib "eagle-import") (part "TESTPAD-20MIL"))
    )
    (comp (ref "LTC3_S10")
      (value "TESTPAD-20MIL")
      (footprint "eagle-import:20MIL")
      (libsource (lib "eagle-import") (part "TESTPAD-20MIL"))
    )
    (comp (ref "LTC3_V+")
      (value "TESTPAD-20MIL")
      (footprint "eagle-import:20MIL")
      (libsource (lib "eagle-import") (part "TESTPAD-20MIL"))
    )
    (comp (ref "LTC3_V-")
      (value "TESTPAD-20MIL")
      (footprint "eagle-import:20MIL")
      (libsource (lib "eagle-import") (part "TESTPAD-20MIL"))
    )
    (comp (ref "Q3")
      (value "SI2351DS")
      (footprint "eagle-import:MICRO3")
      (libsource (lib "eagle-import") (part "IRLML5203"))
    )
    (comp (ref "Q4")
      (value "SI2351DS")
      (footprint "eagle-import:MICRO3")
      (libsource (lib "eagle-import") (part "IRLML5203"))
    )
    (comp (ref "Q5")
      (value "SI2351DS")
      (footprint "eagle-import:MICRO3")
      (libsource (lib "eagle-import") (part "IRLML5203"))
    )
    (comp (ref "Q6")
      (value "SI2351DS")
      (footprint "eagle-import:MICRO3")
      (libsource (lib "eagle-import") (part "IRLML5203"))
    )
    (comp (ref "Q7")
      (value "SI2351DS")
      (footprint "eagle-import:MICRO3")
      (libsource (lib "eagle-import") (part "IRLML5203"))
    )
    (comp (ref "Q8")
      (value "SI2351DS")
      (footprint "eagle-import:MICRO3")
      (libsource (lib "eagle-import") (part "IRLML5203"))
    )
    (comp (ref "Q9")
      (value "SI2351DS")
      (footprint "eagle-import:MICRO3")
      (libsource (lib "eagle-import") (part "IRLML5203"))
    )
    (comp (ref "Q10")
      (value "SI2351DS")
      (footprint "eagle-import:MICRO3")
      (libsource (lib "eagle-import") (part "IRLML5203"))
    )
    (comp (ref "Q11")
      (value "SI2351DS")
      (footprint "eagle-import:MICRO3")
      (libsource (lib "eagle-import") (part "IRLML5203"))
    )
    (comp (ref "Q12")
      (value "SI2351DS")
      (footprint "eagle-import:MICRO3")
      (libsource (lib "eagle-import") (part "IRLML5203"))
    )
    (comp (ref "Q15")
      (value "SI2351DS")
      (footprint "eagle-import:MICRO3")
      (libsource (lib "eagle-import") (part "IRLML5203"))
    )
    (comp (ref "Q16")
      (value "SI2351DS")
      (footprint "eagle-import:MICRO3")
      (libsource (lib "eagle-import") (part "IRLML5203"))
    )
    (comp (ref "Q17")
      (value "SI2351DS")
      (footprint "eagle-import:MICRO3")
      (libsource (lib "eagle-import") (part "IRLML5203"))
    )
    (comp (ref "Q18")
      (value "SI2351DS")
      (footprint "eagle-import:MICRO3")
      (libsource (lib "eagle-import") (part "IRLML5203"))
    )
    (comp (ref "Q19")
      (value "SI2351DS")
      (footprint "eagle-import:MICRO3")
      (libsource (lib "eagle-import") (part "IRLML5203"))
    )
    (comp (ref "Q20")
      (value "SI2351DS")
      (footprint "eagle-import:MICRO3")
      (libsource (lib "eagle-import") (part "IRLML5203"))
    )
    (comp (ref "Q21")
      (value "SI2351DS")
      (footprint "eagle-import:MICRO3")
      (libsource (lib "eagle-import") (part "IRLML5203"))
    )
    (comp (ref "Q22")
      (value "SI2351DS")
      (footprint "eagle-import:MICRO3")
      (libsource (lib "eagle-import") (part "IRLML5203"))
    )
    (comp (ref "Q23")
      (value "SI2351DS")
      (footprint "eagle-import:MICRO3")
      (libsource (lib "eagle-import") (part "IRLML5203"))
    )
    (comp (ref "Q24")
      (value "SI2351DS")
      (footprint "eagle-import:MICRO3")
      (libsource (lib "eagle-import") (part "IRLML5203"))
    )
    (comp (ref "Q27")
      (value "SI2351DS")
      (footprint "eagle-import:MICRO3")
      (libsource (lib "eagle-import") (part "IRLML5203"))
    )
    (comp (ref "Q28")
      (value "SI2351DS")
      (footprint "eagle-import:MICRO3")
      (libsource (lib "eagle-import") (part "IRLML5203"))
    )
    (comp (ref "Q29")
      (value "SI2351DS")
      (footprint "eagle-import:MICRO3")
      (libsource (lib "eagle-import") (part "IRLML5203"))
    )
    (comp (ref "Q30")
      (value "SI2351DS")
      (footprint "eagle-import:MICRO3")
      (libsource (lib "eagle-import") (part "IRLML5203"))
    )
    (comp (ref "Q31")
      (value "SI2351DS")
      (footprint "eagle-import:MICRO3")
      (libsource (lib "eagle-import") (part "IRLML5203"))
    )
    (comp (ref "Q32")
      (value "SI2351DS")
      (footprint "eagle-import:MICRO3")
      (libsource (lib "eagle-import") (part "IRLML5203"))
    )
    (comp (ref "Q33")
      (value "SI2351DS")
      (footprint "eagle-import:MICRO3")
      (libsource (lib "eagle-import") (part "IRLML5203"))
    )
    (comp (ref "Q34")
      (value "SI2351DS")
      (footprint "eagle-import:MICRO3")
      (libsource (lib "eagle-import") (part "IRLML5203"))
    )
    (comp (ref "Q35")
      (value "SI2351DS")
      (footprint "eagle-import:MICRO3")
      (libsource (lib "eagle-import") (part "IRLML5203"))
    )
    (comp (ref "Q36")
      (value "SI2351DS")
      (footprint "eagle-import:MICRO3")
      (libsource (lib "eagle-import") (part "IRLML5203"))
    )
    (comp (ref "R5")
      (value "1M")
      (footprint "eagle-import:R1206")
      (libsource (lib "eagle-import") (part "R-US_R1206"))
    )
    (comp (ref "R10")
      (value "100 1%")
      (footprint "eagle-import:R1206")
      (libsource (lib "eagle-import") (part "R-US_R1206"))
    )
    (comp (ref "R11")
      (value "3.3K")
      (footprint "eagle-import:R1206")
      (libsource (lib "eagle-import") (part "R-US_R1206"))
    )
    (comp (ref "R12")
      (value "33 1W")
      (footprint "eagle-import:R2512")
      (libsource (lib "eagle-import") (part "R-US_R2512"))
    )
    (comp (ref "R14")
      (value "100 1%")
      (footprint "eagle-import:R1206")
      (libsource (lib "eagle-import") (part "R-US_R1206"))
    )
    (comp (ref "R15")
      (value "3.3K")
      (footprint "eagle-import:R1206")
      (libsource (lib "eagle-import") (part "R-US_R1206"))
    )
    (comp (ref "R16")
      (value "33 1W")
      (footprint "eagle-import:R2512")
      (libsource (lib "eagle-import") (part "R-US_R2512"))
    )
    (comp (ref "R18")
      (value "100 1%")
      (footprint "eagle-import:R1206")
      (libsource (lib "eagle-import") (part "R-US_R1206"))
    )
    (comp (ref "R19")
      (value "3.3K")
      (footprint "eagle-import:R1206")
      (libsource (lib "eagle-import") (part "R-US_R1206"))
    )
    (comp (ref "R20")
      (value "33 1W")
      (footprint "eagle-import:R2512")
      (libsource (lib "eagle-import") (part "R-US_R2512"))
    )
    (comp (ref "R22")
      (value "100 1%")
      (footprint "eagle-import:R1206")
      (libsource (lib "eagle-import") (part "R-US_R1206"))
    )
    (comp (ref "R23")
      (value "3.3K")
      (footprint "eagle-import:R1206")
      (libsource (lib "eagle-import") (part "R-US_R1206"))
    )
    (comp (ref "R24")
      (value "33 1W")
      (footprint "eagle-import:R2512")
      (libsource (lib "eagle-import") (part "R-US_R2512"))
    )
    (comp (ref "R26")
      (value "100 1%")
      (footprint "eagle-import:R1206")
      (libsource (lib "eagle-import") (part "R-US_R1206"))
    )
    (comp (ref "R27")
      (value "3.3K")
      (footprint "eagle-import:R1206")
      (libsource (lib "eagle-import") (part "R-US_R1206"))
    )
    (comp (ref "R28")
      (value "33 1W")
      (footprint "eagle-import:R2512")
      (libsource (lib "eagle-import") (part "R-US_R2512"))
    )
    (comp (ref "R30")
      (value "100 1%")
      (footprint "eagle-import:R1206")
      (libsource (lib "eagle-import") (part "R-US_R1206"))
    )
    (comp (ref "R31")
      (value "3.3K")
      (footprint "eagle-import:R1206")
      (libsource (lib "eagle-import") (part "R-US_R1206"))
    )
    (comp (ref "R32")
      (value "33 1W")
      (footprint "eagle-import:R2512")
      (libsource (lib "eagle-import") (part "R-US_R2512"))
    )
    (comp (ref "R34")
      (value "100 1%")
      (footprint "eagle-import:R1206")
      (libsource (lib "eagle-import") (part "R-US_R1206"))
    )
    (comp (ref "R35")
      (value "3.3K")
      (footprint "eagle-import:R1206")
      (libsource (lib "eagle-import") (part "R-US_R1206"))
    )
    (comp (ref "R36")
      (value "33 1W")
      (footprint "eagle-import:R2512")
      (libsource (lib "eagle-import") (part "R-US_R2512"))
    )
    (comp (ref "R38")
      (value "100 1%")
      (footprint "eagle-import:R1206")
      (libsource (lib "eagle-import") (part "R-US_R1206"))
    )
    (comp (ref "R39")
      (value "3.3K")
      (footprint "eagle-import:R1206")
      (libsource (lib "eagle-import") (part "R-US_R1206"))
    )
    (comp (ref "R40")
      (value "33 1W")
      (footprint "eagle-import:R2512")
      (libsource (lib "eagle-import") (part "R-US_R2512"))
    )
    (comp (ref "R42")
      (value "100 1%")
      (footprint "eagle-import:R1206")
      (libsource (lib "eagle-import") (part "R-US_R1206"))
    )
    (comp (ref "R43")
      (value "3.3K")
      (footprint "eagle-import:R1206")
      (libsource (lib "eagle-import") (part "R-US_R1206"))
    )
    (comp (ref "R44")
      (value "33 1W")
      (footprint "eagle-import:R2512")
      (libsource (lib "eagle-import") (part "R-US_R2512"))
    )
    (comp (ref "R46")
      (value "100 1%")
      (footprint "eagle-import:R1206")
      (libsource (lib "eagle-import") (part "R-US_R1206"))
    )
    (comp (ref "R47")
      (value "3.3K")
      (footprint "eagle-import:R1206")
      (libsource (lib "eagle-import") (part "R-US_R1206"))
    )
    (comp (ref "R48")
      (value "33 1W")
      (footprint "eagle-import:R2512")
      (libsource (lib "eagle-import") (part "R-US_R2512"))
    )
    (comp (ref "R50")
      (value "100")
      (footprint "eagle-import:R1206")
      (libsource (lib "eagle-import") (part "R-US_R1206"))
    )
    (comp (ref "R51")
      (value "100 1%")
      (footprint "eagle-import:R1206")
      (libsource (lib "eagle-import") (part "R-US_R1206"))
    )
    (comp (ref "R62")
      (value "100 1%")
      (footprint "eagle-import:R1206")
      (libsource (lib "eagle-import") (part "R-US_R1206"))
    )
    (comp (ref "R63")
      (value "3.3K")
      (footprint "eagle-import:R1206")
      (libsource (lib "eagle-import") (part "R-US_R1206"))
    )
    (comp (ref "R64")
      (value "33 1W")
      (footprint "eagle-import:R2512")
      (libsource (lib "eagle-import") (part "R-US_R2512"))
    )
    (comp (ref "R66")
      (value "100 1%")
      (footprint "eagle-import:R1206")
      (libsource (lib "eagle-import") (part "R-US_R1206"))
    )
    (comp (ref "R67")
      (value "3.3K")
      (footprint "eagle-import:R1206")
      (libsource (lib "eagle-import") (part "R-US_R1206"))
    )
    (comp (ref "R68")
      (value "33 1W")
      (footprint "eagle-import:R2512")
      (libsource (lib "eagle-import") (part "R-US_R2512"))
    )
    (comp (ref "R70")
      (value "100 1%")
      (footprint "eagle-import:R1206")
      (libsource (lib "eagle-import") (part "R-US_R1206"))
    )
    (comp (ref "R71")
      (value "3.3K")
      (footprint "eagle-import:R1206")
      (libsource (lib "eagle-import") (part "R-US_R1206"))
    )
    (comp (ref "R72")
      (value "33 1W")
      (footprint "eagle-import:R2512")
      (libsource (lib "eagle-import") (part "R-US_R2512"))
    )
    (comp (ref "R74")
      (value "100 1%")
      (footprint "eagle-import:R1206")
      (libsource (lib "eagle-import") (part "R-US_R1206"))
    )
    (comp (ref "R75")
      (value "3.3K")
      (footprint "eagle-import:R1206")
      (libsource (lib "eagle-import") (part "R-US_R1206"))
    )
    (comp (ref "R76")
      (value "33 1W")
      (footprint "eagle-import:R2512")
      (libsource (lib "eagle-import") (part "R-US_R2512"))
    )
    (comp (ref "R78")
      (value "100 1%")
      (footprint "eagle-import:R1206")
      (libsource (lib "eagle-import") (part "R-US_R1206"))
    )
    (comp (ref "R79")
      (value "3.3K")
      (footprint "eagle-import:R1206")
      (libsource (lib "eagle-import") (part "R-US_R1206"))
    )
    (comp (ref "R80")
      (value "33 1W")
      (footprint "eagle-import:R2512")
      (libsource (lib "eagle-import") (part "R-US_R2512"))
    )
    (comp (ref "R82")
      (value "100 1%")
      (footprint "eagle-import:R1206")
      (libsource (lib "eagle-import") (part "R-US_R1206"))
    )
    (comp (ref "R83")
      (value "3.3K")
      (footprint "eagle-import:R1206")
      (libsource (lib "eagle-import") (part "R-US_R1206"))
    )
    (comp (ref "R84")
      (value "33 1W")
      (footprint "eagle-import:R2512")
      (libsource (lib "eagle-import") (part "R-US_R2512"))
    )
    (comp (ref "R86")
      (value "100 1%")
      (footprint "eagle-import:R1206")
      (libsource (lib "eagle-import") (part "R-US_R1206"))
    )
    (comp (ref "R87")
      (value "3.3K")
      (footprint "eagle-import:R1206")
      (libsource (lib "eagle-import") (part "R-US_R1206"))
    )
    (comp (ref "R88")
      (value "33 1W")
      (footprint "eagle-import:R2512")
      (libsource (lib "eagle-import") (part "R-US_R2512"))
    )
    (comp (ref "R90")
      (value "100 1%")
      (footprint "eagle-import:R1206")
      (libsource (lib "eagle-import") (part "R-US_R1206"))
    )
    (comp (ref "R91")
      (value "3.3K")
      (footprint "eagle-import:R1206")
      (libsource (lib "eagle-import") (part "R-US_R1206"))
    )
    (comp (ref "R92")
      (value "33 1W")
      (footprint "eagle-import:R2512")
      (libsource (lib "eagle-import") (part "R-US_R2512"))
    )
    (comp (ref "R94")
      (value "100 1%")
      (footprint "eagle-import:R1206")
      (libsource (lib "eagle-import") (part "R-US_R1206"))
    )
    (comp (ref "R95")
      (value "3.3K")
      (footprint "eagle-import:R1206")
      (libsource (lib "eagle-import") (part "R-US_R1206"))
    )
    (comp (ref "R96")
      (value "33 1W")
      (footprint "eagle-import:R2512")
      (libsource (lib "eagle-import") (part "R-US_R2512"))
    )
    (comp (ref "R98")
      (value "100 1%")
      (footprint "eagle-import:R1206")
      (libsource (lib "eagle-import") (part "R-US_R1206"))
    )
    (comp (ref "R99")
      (value "3.3K")
      (footprint "eagle-import:R1206")
      (libsource (lib "eagle-import") (part "R-US_R1206"))
    )
    (comp (ref "R100")
      (value "33 1W")
      (footprint "eagle-import:R2512")
      (libsource (lib "eagle-import") (part "R-US_R2512"))
    )
    (comp (ref "R102")
      (value "100")
      (footprint "eagle-import:R1206")
      (libsource (lib "eagle-import") (part "R-US_R1206"))
    )
    (comp (ref "R103")
      (value "100 1%")
      (footprint "eagle-import:R1206")
      (libsource (lib "eagle-import") (part "R-US_R1206"))
    )
    (comp (ref "R104")
      (value "1M")
      (footprint "eagle-import:R1206")
      (libsource (lib "eagle-import") (part "R-US_R1206"))
    )
    (comp (ref "R113")
      (value "100 1%")
      (footprint "eagle-import:R1206")
      (libsource (lib "eagle-import") (part "R-US_R1206"))
    )
    (comp (ref "R114")
      (value "3.3K")
      (footprint "eagle-import:R1206")
      (libsource (lib "eagle-import") (part "R-US_R1206"))
    )
    (comp (ref "R115")
      (value "33 1W")
      (footprint "eagle-import:R2512")
      (libsource (lib "eagle-import") (part "R-US_R2512"))
    )
    (comp (ref "R117")
      (value "100 1%")
      (footprint "eagle-import:R1206")
      (libsource (lib "eagle-import") (part "R-US_R1206"))
    )
    (comp (ref "R118")
      (value "3.3K")
      (footprint "eagle-import:R1206")
      (libsource (lib "eagle-import") (part "R-US_R1206"))
    )
    (comp (ref "R119")
      (value "33 1W")
      (footprint "eagle-import:R2512")
      (libsource (lib "eagle-import") (part "R-US_R2512"))
    )
    (comp (ref "R121")
      (value "100 1%")
      (footprint "eagle-import:R1206")
      (libsource (lib "eagle-import") (part "R-US_R1206"))
    )
    (comp (ref "R122")
      (value "3.3K")
      (footprint "eagle-import:R1206")
      (libsource (lib "eagle-import") (part "R-US_R1206"))
    )
    (comp (ref "R123")
      (value "33 1W")
      (footprint "eagle-import:R2512")
      (libsource (lib "eagle-import") (part "R-US_R2512"))
    )
    (comp (ref "R125")
      (value "100 1%")
      (footprint "eagle-import:R1206")
      (libsource (lib "eagle-import") (part "R-US_R1206"))
    )
    (comp (ref "R126")
      (value "3.3K")
      (footprint "eagle-import:R1206")
      (libsource (lib "eagle-import") (part "R-US_R1206"))
    )
    (comp (ref "R127")
      (value "33 1W")
      (footprint "eagle-import:R2512")
      (libsource (lib "eagle-import") (part "R-US_R2512"))
    )
    (comp (ref "R129")
      (value "100 1%")
      (footprint "eagle-import:R1206")
      (libsource (lib "eagle-import") (part "R-US_R1206"))
    )
    (comp (ref "R130")
      (value "3.3K")
      (footprint "eagle-import:R1206")
      (libsource (lib "eagle-import") (part "R-US_R1206"))
    )
    (comp (ref "R131")
      (value "33 1W")
      (footprint "eagle-import:R2512")
      (libsource (lib "eagle-import") (part "R-US_R2512"))
    )
    (comp (ref "R133")
      (value "100 1%")
      (footprint "eagle-import:R1206")
      (libsource (lib "eagle-import") (part "R-US_R1206"))
    )
    (comp (ref "R134")
      (value "3.3K")
      (footprint "eagle-import:R1206")
      (libsource (lib "eagle-import") (part "R-US_R1206"))
    )
    (comp (ref "R135")
      (value "33 1W")
      (footprint "eagle-import:R2512")
      (libsource (lib "eagle-import") (part "R-US_R2512"))
    )
    (comp (ref "R137")
      (value "100 1%")
      (footprint "eagle-import:R1206")
      (libsource (lib "eagle-import") (part "R-US_R1206"))
    )
    (comp (ref "R138")
      (value "3.3K")
      (footprint "eagle-import:R1206")
      (libsource (lib "eagle-import") (part "R-US_R1206"))
    )
    (comp (ref "R139")
      (value "33 1W")
      (footprint "eagle-import:R2512")
      (libsource (lib "eagle-import") (part "R-US_R2512"))
    )
    (comp (ref "R141")
      (value "100 1%")
      (footprint "eagle-import:R1206")
      (libsource (lib "eagle-import") (part "R-US_R1206"))
    )
    (comp (ref "R142")
      (value "3.3K")
      (footprint "eagle-import:R1206")
      (libsource (lib "eagle-import") (part "R-US_R1206"))
    )
    (comp (ref "R143")
      (value "33 1W")
      (footprint "eagle-import:R2512")
      (libsource (lib "eagle-import") (part "R-US_R2512"))
    )
    (comp (ref "R145")
      (value "100 1%")
      (footprint "eagle-import:R1206")
      (libsource (lib "eagle-import") (part "R-US_R1206"))
    )
    (comp (ref "R146")
      (value "3.3K")
      (footprint "eagle-import:R1206")
      (libsource (lib "eagle-import") (part "R-US_R1206"))
    )
    (comp (ref "R147")
      (value "33 1W")
      (footprint "eagle-import:R2512")
      (libsource (lib "eagle-import") (part "R-US_R2512"))
    )
    (comp (ref "R149")
      (value "100 1%")
      (footprint "eagle-import:R1206")
      (libsource (lib "eagle-import") (part "R-US_R1206"))
    )
    (comp (ref "R150")
      (value "3.3K")
      (footprint "eagle-import:R1206")
      (libsource (lib "eagle-import") (part "R-US_R1206"))
    )
    (comp (ref "R151")
      (value "33 1W")
      (footprint "eagle-import:R2512")
      (libsource (lib "eagle-import") (part "R-US_R2512"))
    )
    (comp (ref "R153")
      (value "100")
      (footprint "eagle-import:R1206")
      (libsource (lib "eagle-import") (part "R-US_R1206"))
    )
    (comp (ref "R154")
      (value "100 1%")
      (footprint "eagle-import:R1206")
      (libsource (lib "eagle-import") (part "R-US_R1206"))
    )
    (comp (ref "R155")
      (value "1M")
      (footprint "eagle-import:R1206")
      (libsource (lib "eagle-import") (part "R-US_R1206"))
    )
    (comp (ref "R163")
      (value "1M")
      (footprint "eagle-import:R1206")
      (libsource (lib "eagle-import") (part "resistor_R-US_R1206"))
    )
    (comp (ref "R164")
      (value "1M")
      (footprint "eagle-import:R1206")
      (libsource (lib "eagle-import") (part "resistor_R-US_R1206"))
    )
    (comp (ref "R165")
      (value "1M")
      (footprint "eagle-import:R1206")
      (libsource (lib "eagle-import") (part "resistor_R-US_R1206"))
    )
    (comp (ref "R166")
      (value "1M")
      (footprint "eagle-import:R1206")
      (libsource (lib "eagle-import") (part "resistor_R-US_R1206"))
    )
    (comp (ref "R167")
      (value "1M")
      (footprint "eagle-import:R1206")
      (libsource (lib "eagle-import") (part "resistor_R-US_R1206"))
    )
    (comp (ref "R168")
      (value "1M")
      (footprint "eagle-import:R1206")
      (libsource (lib "eagle-import") (part "resistor_R-US_R1206"))
    )
    (comp (ref "U$8")
      (value "3ROW_6POS")
      (footprint "eagle-import:3ROW_6POS")
      (libsource (lib "eagle-import") (part "3ROW_6POS"))
    )
    (comp (ref "U$9")
      (value "3ROW_6POS")
      (footprint "eagle-import:3ROW_6POS")
      (libsource (lib "eagle-import") (part "3ROW_6POS"))
    )
    (comp (ref "U$10")
      (value "3ROW_6POS")
      (footprint "eagle-import:3ROW_6POS")
      (libsource (lib "eagle-import") (part "3ROW_6POS"))
    )
    (comp (ref "LED")
      (value "MA03-2")
      (footprint "eagle-import:MA03-2")
      (libsource (lib "eagle-import") (part "MA03-2"))
    )
    (comp (ref "LED37")
      (value "YELLOW")
      (footprint "eagle-import:CHIPLED_1206")
      (libsource (lib "eagle-import") (part "LEDCHIPLED_1206"))
    )
    (comp (ref "LED38")
      (value "RED")
      (footprint "eagle-import:CHIPLED_1206")
      (libsource (lib "eagle-import") (part "LEDCHIPLED_1206"))
    )
    (comp (ref "LED40")
      (value "YELLOW")
      (footprint "eagle-import:CHIPLED_1206")
      (libsource (lib "eagle-import") (part "LEDCHIPLED_1206"))
    )
    (comp (ref "LED_SWITCH")
      (value "MA03-1")
      (footprint "eagle-import:MA03-1")
      (libsource (lib "eagle-import") (part "MA03-1"))
    )
    (comp (ref "R1")
      (value "10K")
      (footprint "eagle-import:R1206")
      (libsource (lib "eagle-import") (part "R-US_R1206"))
    )
    (comp (ref "R156")
      (value "62")
      (footprint "eagle-import:R1206")
      (libsource (lib "eagle-import") (part "R-US_R1206"))
    )
    (comp (ref "R157")
      (value "62")
      (footprint "eagle-import:R1206")
      (libsource (lib "eagle-import") (part "R-US_R1206"))
    )
    (comp (ref "R158")
      (value "62")
      (footprint "eagle-import:R1206")
      (libsource (lib "eagle-import") (part "R-US_R1206"))
    )
    (comp (ref "S2")
      (value "10-XX")
      (footprint "eagle-import:B3F-10XX")
      (fields (field (name "MPN") "B3F-1000"))
      (libsource (lib "eagle-import") (part "10-XX"))
    )
    (comp (ref "CONTACTOR")
      (value "C-GRID-02-70553")
      (footprint "eagle-import:70553-02")
      (libsource (lib "eagle-import") (part "C-GRID-02-70553"))
    )
    (comp (ref "K1")
      (value "G2REA")
      (footprint "eagle-import:G2REA")
      (libsource (lib "eagle-import") (part "G2REA"))
    )
    (comp (ref "R2")
      (value "10k")
      (footprint "eagle-import:R1206")
      (libsource (lib "eagle-import") (part "R-US_R1206"))
    )
    (comp (ref "R169")
      (value "100")
      (footprint "eagle-import:R1206")
      (libsource (lib "eagle-import") (part "R-US_R1206"))
    )
    (comp (ref "RELAY")
      (value "MA03-1")
      (footprint "eagle-import:MA03-1")
      (libsource (lib "eagle-import") (part "MA03-1"))
    )
    (comp (ref "T1")
      (value "PMV56XN")
      (footprint "eagle-import:SOT23")
      (fields (field (name "PART_NUM") "PMV56XN,215"))
      (libsource (lib "eagle-import") (part "N-CHANNEL_MOSFETPMV56XN,215"))
    )
    (comp (ref "J19")
      (value "RJ11-2L-B")
      (footprint "eagle-import:RJ11-NO_SHIELD")
      (fields (field (name "MF") "TYCO ELECTRONICS"))
      (libsource (lib "eagle-import") (part "RJ11-2L-B"))
    )
    (comp (ref "J20")
      (value "RJ11-2L-B")
      (footprint "eagle-import:RJ11-NO_SHIELD")
      (fields (field (name "MF") "TYCO ELECTRONICS"))
      (libsource (lib "eagle-import") (part "RJ11-2L-B"))
    )
    (comp (ref "R170")
      (value "120")
      (footprint "eagle-import:R1206")
      (libsource (lib "eagle-import") (part "R-US_R1206"))
    )
    (comp (ref "RS-485")
      (value "MA08-2")
      (footprint "eagle-import:MA08-2")
      (libsource (lib "eagle-import") (part "MA08-2"))
    )
    (comp (ref "U$4")
      (value "MAX3440E")
      (footprint "eagle-import:SO-08")
      (libsource (lib "eagle-import") (part "MAX3440E"))
    )
    (comp (ref "12V")
      (value "C-GRID-04-70553")
      (footprint "eagle-import:70553-04")
      (libsource (lib "eagle-import") (part "C-GRID-04-70553"))
    )
    (comp (ref "C49")
      (value ".1uF")
      (footprint "eagle-import:C1206")
      (libsource (lib "eagle-import") (part "C-USC1206"))
    )
    (comp (ref "C50")
      (value "1uF")
      (footprint "eagle-import:C1206")
      (libsource (lib "eagle-import") (part "C-USC1206"))
    )
    (comp (ref "C51")
      (value "1uF")
      (footprint "eagle-import:C1206")
      (libsource (lib "eagle-import") (part "C-USC1206"))
    )
    (comp (ref "C52")
      (value ".1uF")
      (footprint "eagle-import:C1206")
      (libsource (lib "eagle-import") (part "C-USC1206"))
    )
    (comp (ref "C53")
      (value "1uF")
      (footprint "eagle-import:C1206")
      (libsource (lib "eagle-import") (part "C-USC1206"))
    )
    (comp (ref "C54")
      (value ".1uF")
      (footprint "eagle-import:C1206")
      (libsource (lib "eagle-import") (part "C-USC1206"))
    )
    (comp (ref "IC2")
      (value "7805DT")
      (footprint "eagle-import:TO252")
      (libsource (lib "eagle-import") (part "78DT05"))
    )
    (comp (ref "IC3")
      (value "REG1117")
      (footprint "eagle-import:SOT223")
      (libsource (lib "eagle-import") (part "REG1117"))
    )
    (comp (ref "U$7")
      (value "MAX6105")
      (footprint "eagle-import:SOT23")
      (libsource (lib "eagle-import") (part "MAX6103"))
    )
    (comp (ref "PROGRAM")
      (value "C-GRID-06-70543")
      (footprint "eagle-import:70543-06")
      (libsource (lib "eagle-import") (part "C-GRID-06-70543"))
    )
    (comp (ref "ADC_BITS")
      (value "MA04-2")
      (footprint "eagle-import:MA04-2")
      (libsource (lib "eagle-import") (part "MA04-2"))
    )
    (comp (ref "ADC_POWER")
      (value "MA03-1")
      (footprint "eagle-import:MA03-1")
      (libsource (lib "eagle-import") (part "MA03-1"))
    )
    (comp (ref "AIN0")
      (value "C-GRID-03-70553")
      (footprint "eagle-import:70553-03")
      (libsource (lib "eagle-import") (part "C-GRID-03-70553"))
    )
    (comp (ref "AIN1")
      (value "C-GRID-03-70553")
      (footprint "eagle-import:70553-03")
      (libsource (lib "eagle-import") (part "C-GRID-03-70553"))
    )
    (comp (ref "AIN2")
      (value "C-GRID-03-70553")
      (footprint "eagle-import:70553-03")
      (libsource (lib "eagle-import") (part "C-GRID-03-70553"))
    )
    (comp (ref "AIN3")
      (value "C-GRID-03-70553")
      (footprint "eagle-import:70553-03")
      (libsource (lib "eagle-import") (part "C-GRID-03-70553"))
    )
    (comp (ref "AIN4")
      (value "C-GRID-03-70553")
      (footprint "eagle-import:70553-03")
      (libsource (lib "eagle-import") (part "C-GRID-03-70553"))
    )
    (comp (ref "U$1")
      (value "SP720APP")
      (footprint "eagle-import:SO16")
      (libsource (lib "eagle-import") (part "SP720APP"))
    )
    (comp (ref "U$6")
      (value "MCP-3008")
      (footprint "eagle-import:SO16")
      (libsource (lib "eagle-import") (part "MCP-3008"))
    )
    (comp (ref "C1")
      (value "1uF")
      (footprint "eagle-import:C1206")
      (libsource (lib "eagle-import") (part "C-USC1206"))
    )
    (comp (ref "C16")
      (value ".1uF")
      (footprint "eagle-import:C1206")
      (libsource (lib "eagle-import") (part "C-USC1206"))
    )
    (comp (ref "C22")
      (value "4.7uF")
      (footprint "eagle-import:C1206")
      (libsource (lib "eagle-import") (part "C-USC1206"))
    )
    (comp (ref "C48")
      (value ".1uF")
      (footprint "eagle-import:C1206")
      (libsource (lib "eagle-import") (part "C-USC1206"))
    )
    (comp (ref "MCLR")
      (value "MA03-1")
      (footprint "eagle-import:MA03-1")
      (libsource (lib "eagle-import") (part "MA03-1"))
    )
    (comp (ref "PIC_POWER")
      (value "MA03-1")
      (footprint "eagle-import:MA03-1")
      (libsource (lib "eagle-import") (part "MA03-1"))
    )
    (comp (ref "R52")
      (value "10k\\")
      (footprint "eagle-import:R1206")
      (libsource (lib "eagle-import") (part "R-US_R1206"))
    )
    (comp (ref "R53")
      (value "470")
      (footprint "eagle-import:R1206")
      (libsource (lib "eagle-import") (part "R-US_R1206"))
    )
    (comp (ref "SV3")
      (value "MA20-2")
      (footprint "eagle-import:MA20-2")
      (libsource (lib "eagle-import") (part "MA20-2"))
    )
    (comp (ref "SV4")
      (value "MA20-2")
      (footprint "eagle-import:MA20-2")
      (libsource (lib "eagle-import") (part "MA20-2"))
    )
    (comp (ref "U$2")
      (value "PIC24HJ128GP-202")
      (footprint "eagle-import:SO28W")
      (libsource (lib "eagle-import") (part "PIC24HJ128GP-202"))
    )
    (comp (ref "U$3")
      (value "ASE")
      (footprint "eagle-import:ASE")
      (libsource (lib "eagle-import") (part "ASE"))
    )
  )
  (nets
    (net (code "1") (name "+3V3") (class "Default")
      (node (ref "C16") (pin "1") (pinfunction "1_1") (pintype "passive"))
      (node (ref "C48") (pin "1") (pinfunction "1_1") (pintype "passive"))
      (node (ref "C52") (pin "1") (pinfunction "1_1") (pintype "passive"))
      (node (ref "IC3") (pin "2") (pinfunction "VOUT_2") (pintype "output"))
      (node (ref "PIC_POWER") (pin "3") (pinfunction "3_3") (pintype "passive"))
      (node (ref "PROGRAM") (pin "5") (pinfunction "S_5") (pintype "passive"))
      (node (ref "R1") (pin "2") (pinfunction "2_2") (pintype "passive"))
      (node (ref "R52") (pin "1") (pinfunction "1_1") (pintype "passive"))
      (node (ref "U$2") (pin "13") (pinfunction "VDD_13") (pintype "bidirectional"))
      (node (ref "U$2") (pin "28") (pinfunction "AVDD_28") (pintype "bidirectional"))
      (node (ref "U$3") (pin "1") (pinfunction "TRI_1") (pintype "input"))
      (node (ref "U$3") (pin "4") (pinfunction "VDD_4") (pintype "power_in"))
    )
    (net (code "2") (name "+5V") (class "Default")
      (node (ref "ADC_POWER") (pin "3") (pinfunction "3_3") (pintype "passive"))
      (node (ref "AIN0") (pin "2") (pinfunction "S_2") (pintype "passive"))
      (node (ref "AIN1") (pin "2") (pinfunction "S_2") (pintype "passive"))
      (node (ref "AIN2") (pin "2") (pinfunction "S_2") (pintype "passive"))
      (node (ref "AIN3") (pin "2") (pinfunction "S_2") (pintype "passive"))
      (node (ref "AIN4") (pin "2") (pinfunction "S_2") (pintype "passive"))
      (node (ref "C54") (pin "1") (pinfunction "1_1") (pintype "passive"))
      (node (ref "IC1") (pin "1") (pinfunction "VDD1_1") (pintype "power_in"))
      (node (ref "IC1") (pin "7") (pinfunction "VE1_7") (pintype "passive"))
      (node (ref "IC2") (pin "2") (pinfunction "VO_2") (pintype "passive"))
      (node (ref "IC2_\\") (pin "1") (pinfunction "VDD1_1") (pintype "power_in"))
      (node (ref "IC2_\\") (pin "7") (pinfunction "VE1_7") (pintype "passive"))
      (node (ref "IC3_") (pin "1") (pinfunction "VDD1_1") (pintype "power_in"))
      (node (ref "IC3_") (pin "7") (pinfunction "VE1_7") (pintype "passive"))
      (node (ref "LTC1_HEAD") (pin "10") (pinfunction "10_10") (pintype "passive"))
      (node (ref "LTC1_HEAD") (pin "9") (pinfunction "9_9") (pintype "passive"))
      (node (ref "LTC2_HEAD") (pin "10") (pinfunction "10_10") (pintype "passive"))
      (node (ref "LTC2_HEAD") (pin "9") (pinfunction "9_9") (pintype "passive"))
      (node (ref "LTC3_HEAD") (pin "10") (pinfunction "10_10") (pintype "passive"))
      (node (ref "LTC3_HEAD") (pin "9") (pinfunction "9_9") (pintype "passive"))
      (node (ref "U$1") (pin "16") (pinfunction "V+_16") (pintype "bidirectional"))
      (node (ref "U$4") (pin "8") (pinfunction "V+_8") (pintype "bidirectional"))
      (node (ref "U$6") (pin "16") (pinfunction "VDD_16") (pintype "bidirectional"))
    )
    (net (code "3") (name "12V") (class "Default")
      (node (ref "12V") (pin "4") (pinfunction "S_4") (pintype "passive"))
      (node (ref "C50") (pin "1") (pinfunction "1_1") (pintype "passive"))
      (node (ref "C51") (pin "1") (pinfunction "1_1") (pintype "passive"))
      (node (ref "C53") (pin "1") (pinfunction "1_1") (pintype "passive"))
      (node (ref "IC2") (pin "1") (pinfunction "VI_1") (pintype "input"))
      (node (ref "IC3") (pin "3") (pinfunction "VIN_3") (pintype "input"))
      (node (ref "R169") (pin "2") (pinfunction "2_2") (pintype "passive"))
      (node (ref "U$7") (pin "1") (pinfunction "IN_1") (pintype "bidirectional"))
    )
    (net (code "4") (name "ADC_CS") (class "Default")
      (node (ref "SV3") (pin "21") (pinfunction "21_21") (pintype "passive"))
      (node (ref "SV3") (pin "22") (pinfunction "22_22") (pintype "passive"))
      (node (ref "SV4") (pin "21") (pinfunction "21_21") (pintype "passive"))
      (node (ref "SV4") (pin "22") (pinfunction "22_22") (pintype "passive"))
      (node (ref "U$2") (pin "26") (pinfunction "RB15_26") (pintype "bidirectional"))
    )
    (net (code "5") (name "ADC_CS_ADC") (class "Default")
      (node (ref "ADC_BITS") (pin "7") (pinfunction "7_7") (pintype "passive"))
      (node (ref "ADC_BITS") (pin "8") (pinfunction "8_8") (pintype "passive"))
      (node (ref "U$6") (pin "10") (pinfunction "CS_10") (pintype "bidirectional"))
    )
    (net (code "6") (name "ADC_MISO") (class "Default")
      (node (ref "SV3") (pin "35") (pinfunction "35_35") (pintype "passive"))
      (node (ref "SV3") (pin "36") (pinfunction "36_36") (pintype "passive"))
      (node (ref "SV4") (pin "35") (pinfunction "35_35") (pintype "passive"))
      (node (ref "SV4") (pin "36") (pinfunction "36_36") (pintype "passive"))
      (node (ref "U$2") (pin "17") (pinfunction "RB8_17") (pintype "bidirectional"))
    )
    (net (code "7") (name "ADC_MISO_ADC") (class "Default")
      (node (ref "ADC_BITS") (pin "3") (pinfunction "3_3") (pintype "passive"))
      (node (ref "ADC_BITS") (pin "4") (pinfunction "4_4") (pintype "passive"))
      (node (ref "U$6") (pin "12") (pinfunction "DOUT_12") (pintype "bidirectional"))
    )
    (net (code "8") (name "ADC_SCK") (class "Default")
      (node (ref "ADC_BITS") (pin "1") (pinfunction "1_1") (pintype "passive"))
      (node (ref "ADC_BITS") (pin "2") (pinfunction "2_2") (pintype "passive"))
      (node (ref "U$6") (pin "13") (pinfunction "CLK_13") (pintype "bidirectional"))
    )
    (net (code "9") (name "AGND") (class "Default")
      (node (ref "C19") (pin "2") (pinfunction "2_2") (pintype "passive"))
      (node (ref "C20") (pin "2") (pinfunction "2_2") (pintype "passive"))
      (node (ref "C21") (pin "2") (pinfunction "2_2") (pintype "passive"))
      (node (ref "C23") (pin "2") (pinfunction "2_2") (pintype "passive"))
      (node (ref "C24") (pin "2") (pinfunction "2_2") (pintype "passive"))
      (node (ref "C25") (pin "2") (pinfunction "2_2") (pintype "passive"))
      (node (ref "C26") (pin "2") (pinfunction "2_2") (pintype "passive"))
      (node (ref "C27") (pin "2") (pinfunction "2_2") (pintype "passive"))
      (node (ref "C28") (pin "2") (pinfunction "2_2") (pintype "passive"))
      (node (ref "C29") (pin "2") (pinfunction "2_2") (pintype "passive"))
      (node (ref "C30") (pin "2") (pinfunction "2_2") (pintype "passive"))
      (node (ref "C31") (pin "2") (pinfunction "2_2") (pintype "passive"))
      (node (ref "C32") (pin "2") (pinfunction "2_2") (pintype "passive"))
      (node (ref "D28") (pin "A") (pinfunction "A_A") (pintype "passive"))
      (node (ref "D29") (pin "A") (pinfunction "A_A") (pintype "passive"))
      (node (ref "D30") (pin "A") (pinfunction "A_A") (pintype "passive"))
      (node (ref "IC2_\\") (pin "15") (pinfunction "GND2_15") (pintype "power_in"))
      (node (ref "IC2_\\") (pin "9") (pinfunction "GND2_9") (pintype "power_in"))
      (node (ref "L29") (pin "2") (pinfunction "2_2") (pintype "passive"))
      (node (ref "LTC2") (pin "P$27") (pinfunction "V-_P$27") (pintype "bidirectional"))
      (node (ref "LTC2") (pin "P$28") (pinfunction "NC_P$28") (pintype "bidirectional"))
      (node (ref "LTC2") (pin "P$29") (pinfunction "V_TEMP1_P$29") (pintype "bidirectional"))
      (node (ref "LTC2") (pin "P$30") (pinfunction "V_TEMP2_P$30") (pintype "bidirectional"))
      (node (ref "LTC2") (pin "P$35") (pinfunction "GPIO1_P$35") (pintype "bidirectional"))
      (node (ref "LTC2") (pin "P$36") (pinfunction "GPIO2_P$36") (pintype "bidirectional"))
      (node (ref "LTC2_V-") (pin "P$1") (pinfunction "TP_P$1") (pintype "input"))
      (node (ref "U$9") (pin "1") (pinfunction "1_1") (pintype "passive"))
      (node (ref "U$9") (pin "10") (pinfunction "1_10") (pintype "passive"))
      (node (ref "U$9") (pin "13") (pinfunction "1_13") (pintype "passive"))
      (node (ref "U$9") (pin "16") (pinfunction "1_16") (pintype "passive"))
      (node (ref "U$9") (pin "4") (pinfunction "1_4") (pintype "passive"))
      (node (ref "U$9") (pin "7") (pinfunction "1_7") (pintype "passive"))
    )
    (net (code "10") (name "C22") (class "Default")
      (node (ref "C22") (pin "1") (pinfunction "1_1") (pintype "passive"))
      (node (ref "PIC_POWER") (pin "2") (pinfunction "2_2") (pintype "passive"))
      (node (ref "U$2") (pin "20") (pinfunction "VCAP_20") (pintype "bidirectional"))
    )
    (net (code "11") (name "CELL0") (class "Default")
      (node (ref "GND-10") (pin "1") (pinfunction "S_1") (pintype "passive"))
      (node (ref "L16") (pin "1") (pinfunction "1_1") (pintype "passive"))
      (node (ref "L17") (pin "1") (pinfunction "1_1") (pintype "passive"))
    )
    (net (code "12") (name "CELL1") (class "Default")
      (node (ref "GND-10") (pin "2") (pinfunction "S_2") (pintype "passive"))
      (node (ref "L14") (pin "1") (pinfunction "1_1") (pintype "passive"))
    )
    (net (code "13") (name "CELL2") (class "Default")
      (node (ref "GND-10") (pin "3") (pinfunction "S_3") (pintype "passive"))
      (node (ref "L13") (pin "1") (pinfunction "1_1") (pintype "passive"))
    )
    (net (code "14") (name "CELL3") (class "Default")
      (node (ref "GND-10") (pin "4") (pinfunction "S_4") (pintype "passive"))
      (node (ref "L12") (pin "1") (pinfunction "1_1") (pintype "passive"))
    )
    (net (code "15") (name "CELL4") (class "Default")
      (node (ref "GND-10") (pin "5") (pinfunction "S_5") (pintype "passive"))
      (node (ref "L11") (pin "1") (pinfunction "1_1") (pintype "passive"))
    )
    (net (code "16") (name "CELL5") (class "Default")
      (node (ref "GND-10") (pin "6") (pinfunction "S_6") (pintype "passive"))
      (node (ref "L10") (pin "1") (pinfunction "1_1") (pintype "passive"))
    )
    (net (code "17") (name "CELL6") (class "Default")
      (node (ref "GND-10") (pin "7") (pinfunction "S_7") (pintype "passive"))
      (node (ref "L9") (pin "1") (pinfunction "1_1") (pintype "passive"))
    )
    (net (code "18") (name "CELL7") (class "Default")
      (node (ref "GND-10") (pin "8") (pinfunction "S_8") (pintype "passive"))
      (node (ref "L8") (pin "1") (pinfunction "1_1") (pintype "passive"))
    )
    (net (code "19") (name "CELL8") (class "Default")
      (node (ref "GND-10") (pin "9") (pinfunction "S_9") (pintype "passive"))
      (node (ref "L7") (pin "1") (pinfunction "1_1") (pintype "passive"))
    )
    (net (code "20") (name "CELL9") (class "Default")
      (node (ref "GND-10") (pin "10") (pinfunction "S_10") (pintype "passive"))
      (node (ref "L6") (pin "1") (pinfunction "1_1") (pintype "passive"))
    )
    (net (code "21") (name "CELL10") (class "Default")
      (node (ref "GND-10") (pin "11") (pinfunction "S_11") (pintype "passive"))
      (node (ref "L15") (pin "1") (pinfunction "1_1") (pintype "passive"))
      (node (ref "L29") (pin "1") (pinfunction "1_1") (pintype "passive"))
      (node (ref "L30") (pin "1") (pinfunction "1_1") (pintype "passive"))
      (node (ref "L5") (pin "1") (pinfunction "1_1") (pintype "passive"))
    )
    (net (code "22") (name "CELL11") (class "Default")
      (node (ref "CELLS-11-20") (pin "1") (pinfunction "S_1") (pintype "passive"))
      (node (ref "L27") (pin "1") (pinfunction "1_1") (pintype "passive"))
    )
    (net (code "23") (name "CELL12") (class "Default")
      (node (ref "CELLS-11-20") (pin "2") (pinfunction "S_2") (pintype "passive"))
      (node (ref "L26") (pin "1") (pinfunction "1_1") (pintype "passive"))
    )
    (net (code "24") (name "CELL13") (class "Default")
      (node (ref "CELLS-11-20") (pin "3") (pinfunction "S_3") (pintype "passive"))
      (node (ref "L25") (pin "1") (pinfunction "1_1") (pintype "passive"))
    )
    (net (code "25") (name "CELL14") (class "Default")
      (node (ref "CELLS-11-20") (pin "4") (pinfunction "S_4") (pintype "passive"))
      (node (ref "L24") (pin "1") (pinfunction "1_1") (pintype "passive"))
    )
    (net (code "26") (name "CELL15") (class "Default")
      (node (ref "CELLS-11-20") (pin "5") (pinfunction "S_5") (pintype "passive"))
      (node (ref "L23") (pin "1") (pinfunction "1_1") (pintype "passive"))
    )
    (net (code "27") (name "CELL16") (class "Default")
      (node (ref "CELLS-11-20") (pin "6") (pinfunction "S_6") (pintype "passive"))
      (node (ref "L22") (pin "1") (pinfunction "1_1") (pintype "passive"))
    )
    (net (code "28") (name "CELL17") (class "Default")
      (node (ref "CELLS-11-20") (pin "7") (pinfunction "S_7") (pintype "passive"))
      (node (ref "L21") (pin "1") (pinfunction "1_1") (pintype "passive"))
    )
    (net (code "29") (name "CELL18") (class "Default")
      (node (ref "CELLS-11-20") (pin "8") (pinfunction "S_8") (pintype "passive"))
      (node (ref "L20") (pin "1") (pinfunction "1_1") (pintype "passive"))
    )
    (net (code "30") (name "CELL19") (class "Default")
      (node (ref "CELLS-11-20") (pin "9") (pinfunction "S_9") (pintype "passive"))
      (node (ref "L19") (pin "1") (pinfunction "1_1") (pintype "passive"))
    )
    (net (code "31") (name "CELL20") (class "Default")
      (node (ref "CELLS-11-20") (pin "10") (pinfunction "S_10") (pintype "passive"))
      (node (ref "L18") (pin "1") (pinfunction "1_1") (pintype "passive"))
      (node (ref "L28") (pin "1") (pinfunction "1_1") (pintype "passive"))
      (node (ref "L44") (pin "1") (pinfunction "1_1") (pintype "passive"))
      (node (ref "L45") (pin "1") (pinfunction "1_1") (pintype "passive"))
    )
    (net (code "32") (name "CELL21") (class "Default")
      (node (ref "CELLS-21-30") (pin "1") (pinfunction "S_1") (pintype "passive"))
      (node (ref "L42") (pin "1") (pinfunction "1_1") (pintype "passive"))
    )
    (net (code "33") (name "CELL22") (class "Default")
      (node (ref "CELLS-21-30") (pin "2") (pinfunction "S_2") (pintype "passive"))
      (node (ref "L41") (pin "1") (pinfunction "1_1") (pintype "passive"))
    )
    (net (code "34") (name "CELL23") (class "Default")
      (node (ref "CELLS-21-30") (pin "3") (pinfunction "S_3") (pintype "passive"))
      (node (ref "L40") (pin "1") (pinfunction "1_1") (pintype "passive"))
    )
    (net (code "35") (name "CELL24") (class "Default")
      (node (ref "CELLS-21-30") (pin "4") (pinfunction "S_4") (pintype "passive"))
      (node (ref "L39") (pin "1") (pinfunction "1_1") (pintype "passive"))
    )
    (net (code "36") (name "CELL25") (class "Default")
      (node (ref "CELLS-21-30") (pin "5") (pinfunction "S_5") (pintype "passive"))
      (node (ref "L38") (pin "1") (pinfunction "1_1") (pintype "passive"))
    )
    (net (code "37") (name "CELL26") (class "Default")
      (node (ref "CELLS-21-30") (pin "6") (pinfunction "S_6") (pintype "passive"))
      (node (ref "L37") (pin "1") (pinfunction "1_1") (pintype "passive"))
    )
    (net (code "38") (name "CELL27") (class "Default")
      (node (ref "CELLS-21-30") (pin "7") (pinfunction "S_7") (pintype "passive"))
      (node (ref "L36") (pin "1") (pinfunction "1_1") (pintype "passive"))
    )
    (net (code "39") (name "CELL28") (class "Default")
      (node (ref "CELLS-21-30") (pin "8") (pinfunction "S_8") (pintype "passive"))
      (node (ref "L35") (pin "1") (pinfunction "1_1") (pintype "passive"))
    )
    (net (code "40") (name "CELL29") (class "Default")
      (node (ref "CELLS-21-30") (pin "9") (pinfunction "S_9") (pintype "passive"))
      (node (ref "L34") (pin "1") (pinfunction "1_1") (pintype "passive"))
    )
    (net (code "41") (name "CELL30") (class "Default")
      (node (ref "CELLS-21-30") (pin "10") (pinfunction "S_10") (pintype "passive"))
      (node (ref "L33") (pin "1") (pinfunction "1_1") (pintype "passive"))
      (node (ref "L43") (pin "1") (pinfunction "1_1") (pintype "passive"))
    )
    (net (code "42") (name "CRITICAL") (class "Default")
      (node (ref "SV3") (pin "13") (pinfunction "13_13") (pintype "passive"))
      (node (ref "SV3") (pin "14") (pinfunction "14_14") (pintype "passive"))
      (node (ref "SV4") (pin "13") (pinfunction "13_13") (pintype "passive"))
      (node (ref "SV4") (pin "14") (pinfunction "14_14") (pintype "passive"))
      (node (ref "U$2") (pin "10") (pinfunction "RA3_10") (pintype "bidirectional"))
    )
    (net (code "43") (name "CRITICAL_LED") (class "Default")
      (node (ref "LED") (pin "1") (pinfunction "1_1") (pintype "passive"))
      (node (ref "LED") (pin "2") (pinfunction "2_2") (pintype "passive"))
      (node (ref "R156") (pin "2") (pinfunction "2_2") (pintype "passive"))
    )
    (net (code "44") (name "DI-RO") (class "Default")
      (node (ref "SV3") (pin "17") (pinfunction "17_17") (pintype "passive"))
      (node (ref "SV3") (pin "18") (pinfunction "18_18") (pintype "passive"))
      (node (ref "SV4") (pin "17") (pinfunction "17_17") (pintype "passive"))
      (node (ref "SV4") (pin "18") (pinfunction "18_18") (pintype "passive"))
      (node (ref "U$2") (pin "12") (pinfunction "RA4_12") (pintype "bidirectional"))
    )
    (net (code "45") (name "FAULT") (class "Default")
      (node (ref "SV3") (pin "29") (pinfunction "29_29") (pintype "passive"))
      (node (ref "SV3") (pin "30") (pinfunction "30_30") (pintype "passive"))
      (node (ref "SV4") (pin "29") (pinfunction "29_29") (pintype "passive"))
      (node (ref "SV4") (pin "30") (pinfunction "30_30") (pintype "passive"))
      (node (ref "U$2") (pin "22") (pinfunction "RB11_22") (pintype "bidirectional"))
    )
    (net (code "46") (name "GND") (class "Default")
      (node (ref "C10") (pin "2") (pinfunction "2_2") (pintype "passive"))
      (node (ref "C11") (pin "2") (pinfunction "2_2") (pintype "passive"))
      (node (ref "C12") (pin "2") (pinfunction "2_2") (pintype "passive"))
      (node (ref "C13") (pin "2") (pinfunction "2_2") (pintype "passive"))
      (node (ref "C14") (pin "2") (pinfunction "2_2") (pintype "passive"))
      (node (ref "C15") (pin "2") (pinfunction "2_2") (pintype "passive"))
      (node (ref "C2") (pin "2") (pinfunction "2_2") (pintype "passive"))
      (node (ref "C4") (pin "2") (pinfunction "2_2") (pintype "passive"))
      (node (ref "C5") (pin "2") (pinfunction "2_2") (pintype "passive"))
      (node (ref "C6") (pin "2") (pinfunction "2_2") (pintype "passive"))
      (node (ref "C7") (pin "2") (pinfunction "2_2") (pintype "passive"))
      (node (ref "C8") (pin "2") (pinfunction "2_2") (pintype "passive"))
      (node (ref "C9") (pin "2") (pinfunction "2_2") (pintype "passive"))
      (node (ref "D16") (pin "A") (pinfunction "A_A") (pintype "passive"))
      (node (ref "D17") (pin "A") (pinfunction "A_A") (pintype "passive"))
      (node (ref "D18") (pin "A") (pinfunction "A_A") (pintype "passive"))
      (node (ref "IC1") (pin "15") (pinfunction "GND2_15") (pintype "power_in"))
      (node (ref "IC1") (pin "9") (pinfunction "GND2_9") (pintype "power_in"))
      (node (ref "L16") (pin "2") (pinfunction "2_2") (pintype "passive"))
      (node (ref "LTC1") (pin "P$27") (pinfunction "V-_P$27") (pintype "bidirectional"))
      (node (ref "LTC1") (pin "P$28") (pinfunction "NC_P$28") (pintype "bidirectional"))
      (node (ref "LTC1") (pin "P$29") (pinfunction "V_TEMP1_P$29") (pintype "bidirectional"))
      (node (ref "LTC1") (pin "P$30") (pinfunction "V_TEMP2_P$30") (pintype "bidirectional"))
      (node (ref "LTC1") (pin "P$35") (pinfunction "GPIO1_P$35") (pintype "bidirectional"))
      (node (ref "LTC1") (pin "P$36") (pinfunction "GPIO2_P$36") (pintype "bidirectional"))
      (node (ref "LTC1_V-") (pin "P$1") (pinfunction "TP_P$1") (pintype "input"))
      (node (ref "U$8") (pin "1") (pinfunction "1_1") (pintype "passive"))
      (node (ref "U$8") (pin "10") (pinfunction "1_10") (pintype "passive"))
      (node (ref "U$8") (pin "13") (pinfunction "1_13") (pintype "passive"))
      (node (ref "U$8") (pin "16") (pinfunction "1_16") (pintype "passive"))
      (node (ref "U$8") (pin "4") (pinfunction "1_4") (pintype "passive"))
      (node (ref "U$8") (pin "7") (pinfunction "1_7") (pintype "passive"))
    )
    (net (code "47") (name "GNDIO") (class "Default")
      (node (ref "12V") (pin "1") (pinfunction "S_1") (pintype "passive"))
      (node (ref "ADC_POWER") (pin "2") (pinfunction "2_2") (pintype "passive"))
      (node (ref "AIN0") (pin "1") (pinfunction "S_1") (pintype "passive"))
      (node (ref "AIN1") (pin "1") (pinfunction "S_1") (pintype "passive"))
      (node (ref "AIN2") (pin "1") (pinfunction "S_1") (pintype "passive"))
      (node (ref "AIN3") (pin "1") (pinfunction "S_1") (pintype "passive"))
      (node (ref "AIN4") (pin "1") (pinfunction "S_1") (pintype "passive"))
      (node (ref "C1") (pin "2") (pinfunction "2_2") (pintype "passive"))
      (node (ref "C16") (pin "2") (pinfunction "2_2") (pintype "passive"))
      (node (ref "C22") (pin "2") (pinfunction "2_2") (pintype "passive"))
      (node (ref "C48") (pin "2") (pinfunction "2_2") (pintype "passive"))
      (node (ref "C49") (pin "2") (pinfunction "2_2") (pintype "passive"))
      (node (ref "C50") (pin "2") (pinfunction "2_2") (pintype "passive"))
      (node (ref "C51") (pin "2") (pinfunction "2_2") (pintype "passive"))
      (node (ref "C52") (pin "2") (pinfunction "2_2") (pintype "passive"))
      (node (ref "C53") (pin "2") (pinfunction "2_2") (pintype "passive"))
      (node (ref "C54") (pin "2") (pinfunction "2_2") (pintype "passive"))
      (node (ref "IC1") (pin "2") (pinfunction "GND1_2") (pintype "power_in"))
      (node (ref "IC1") (pin "8") (pinfunction "GND1_8") (pintype "power_in"))
      (node (ref "IC2") (pin "3") (pinfunction "GND_3") (pintype "passive"))
      (node (ref "IC2_\\") (pin "2") (pinfunction "GND1_2") (pintype "power_in"))
      (node (ref "IC2_\\") (pin "8") (pinfunction "GND1_8") (pintype "power_in"))
      (node (ref "IC3") (pin "1") (pinfunction "GND_1") (pintype "power_in"))
      (node (ref "IC3_") (pin "2") (pinfunction "GND1_2") (pintype "power_in"))
      (node (ref "IC3_") (pin "8") (pinfunction "GND1_8") (pintype "power_in"))
      (node (ref "LED37") (pin "C") (pinfunction "C_C") (pintype "passive"))
      (node (ref "LED38") (pin "C") (pinfunction "C_C") (pintype "passive"))
      (node (ref "LED40") (pin "C") (pinfunction "C_C") (pintype "passive"))
      (node (ref "LTC1_HEAD") (pin "11") (pinfunction "11_11") (pintype "passive"))
      (node (ref "LTC1_HEAD") (pin "12") (pinfunction "12_12") (pintype "passive"))
      (node (ref "LTC2_HEAD") (pin "11") (pinfunction "11_11") (pintype "passive"))
      (node (ref "LTC2_HEAD") (pin "12") (pinfunction "12_12") (pintype "passive"))
      (node (ref "LTC3_HEAD") (pin "11") (pinfunction "11_11") (pintype "passive"))
      (node (ref "LTC3_HEAD") (pin "12") (pinfunction "12_12") (pintype "passive"))
      (node (ref "PIC_POWER") (pin "1") (pinfunction "1_1") (pintype "passive"))
      (node (ref "PROGRAM") (pin "6") (pinfunction "S_6") (pintype "passive"))
      (node (ref "R2") (pin "1") (pinfunction "1_1") (pintype "passive"))
      (node (ref "S2") (pin "1") (pinfunction "S_1") (pintype "passive"))
      (node (ref "S2") (pin "2") (pinfunction "S1_2") (pintype "passive"))
      (node (ref "T1") (pin "2") (pinfunction "S_2") (pintype "passive"))
      (node (ref "U$1") (pin "8") (pinfunction "V-_8") (pintype "bidirectional"))
      (node (ref "U$2") (pin "19") (pinfunction "VSS_19") (pintype "bidirectional"))
      (node (ref "U$2") (pin "27") (pinfunction "AVSS_27") (pintype "bidirectional"))
      (node (ref "U$2") (pin "8") (pinfunction "VSS_8") (pintype "bidirectional"))
      (node (ref "U$3") (pin "2") (pinfunction "GND_2") (pintype "power_in"))
      (node (ref "U$4") (pin "5") (pinfunction "GND_5") (pintype "bidirectional"))
      (node (ref "U$6") (pin "14") (pinfunction "AGND_14") (pintype "bidirectional"))
      (node (ref "U$6") (pin "9") (pinfunction "DGND_9") (pintype "bidirectional"))
      (node (ref "U$7") (pin "3") (pinfunction "GND_3") (pintype "bidirectional"))
    )
    (net (code "48") (name "JACK2") (class "Default")
      (node (ref "J19") (pin "2") (pinfunction "2_2") (pintype "passive"))
      (node (ref "J20") (pin "2") (pinfunction "2_2") (pintype "passive"))
      (node (ref "RS-485") (pin "10") (pinfunction "10_10") (pintype "passive"))
      (node (ref "RS-485") (pin "9") (pinfunction "9_9") (pintype "passive"))
    )
    (net (code "49") (name "JACK3") (class "Default")
      (node (ref "J19") (pin "3") (pinfunction "3_3") (pintype "passive"))
      (node (ref "J20") (pin "3") (pinfunction "3_3") (pintype "passive"))
      (node (ref "R170") (pin "1") (pinfunction "1_1") (pintype "passive"))
      (node (ref "RS-485") (pin "11") (pinfunction "11_11") (pintype "passive"))
      (node (ref "RS-485") (pin "12") (pinfunction "12_12") (pintype "passive"))
      (node (ref "U$4") (pin "6") (pinfunction "A_6") (pintype "bidirectional"))
    )
    (net (code "50") (name "JACK4") (class "Default")
      (node (ref "J19") (pin "4") (pinfunction "4_4") (pintype "passive"))
      (node (ref "J20") (pin "4") (pinfunction "4_4") (pintype "passive"))
      (node (ref "R170") (pin "2") (pinfunction "2_2") (pintype "passive"))
      (node (ref "RS-485") (pin "13") (pinfunction "13_13") (pintype "passive"))
      (node (ref "RS-485") (pin "14") (pinfunction "14_14") (pintype "passive"))
      (node (ref "U$4") (pin "7") (pinfunction "B_7") (pintype "bidirectional"))
    )
    (net (code "51") (name "JACK5") (class "Default")
      (node (ref "J19") (pin "5") (pinfunction "5_5") (pintype "passive"))
      (node (ref "J20") (pin "5") (pinfunction "5_5") (pintype "passive"))
      (node (ref "RS-485") (pin "15") (pinfunction "15_15") (pintype "passive"))
      (node (ref "RS-485") (pin "16") (pinfunction "16_16") (pintype "passive"))
    )
    (net (code "52") (name "LED2") (class "Default")
      (node (ref "LED_SWITCH") (pin "3") (pinfunction "3_3") (pintype "passive"))
      (node (ref "R158") (pin "2") (pinfunction "2_2") (pintype "passive"))
    )
    (net (code "53") (name "LTC_1_CS") (class "Default")
      (node (ref "SV3") (pin "27") (pinfunction "27_27") (pintype "passive"))
      (node (ref "SV3") (pin "28") (pinfunction "28_28") (pintype "passive"))
      (node (ref "SV4") (pin "27") (pinfunction "27_27") (pintype "passive"))
      (node (ref "SV4") (pin "28") (pinfunction "28_28") (pintype "passive"))
      (node (ref "U$2") (pin "23") (pinfunction "RB12_23") (pintype "bidirectional"))
    )
    (net (code "54") (name "LTC_1_CS_ISO") (class "Default")
      (node (ref "IC1") (pin "5") (pinfunction "VIC_5") (pintype "input"))
      (node (ref "LTC1_HEAD") (pin "3") (pinfunction "3_3") (pintype "passive"))
      (node (ref "LTC1_HEAD") (pin "4") (pinfunction "4_4") (pintype "passive"))
    )
    (net (code "55") (name "LTC_1_MISO") (class "Default")
      (node (ref "SV3") (pin "19") (pinfunction "19_19") (pintype "passive"))
      (node (ref "SV3") (pin "20") (pinfunction "20_20") (pintype "passive"))
      (node (ref "SV4") (pin "19") (pinfunction "19_19") (pintype "passive"))
      (node (ref "SV4") (pin "20") (pinfunction "20_20") (pintype "passive"))
      (node (ref "U$2") (pin "14") (pinfunction "RB5_14") (pintype "bidirectional"))
    )
    (net (code "56") (name "LTC_1_MISO_ISO") (class "Default")
      (node (ref "IC1") (pin "6") (pinfunction "VOD_6") (pintype "output"))
      (node (ref "LTC1_HEAD") (pin "1") (pinfunction "1_1") (pintype "passive"))
      (node (ref "LTC1_HEAD") (pin "2") (pinfunction "2_2") (pintype "passive"))
    )
    (net (code "57") (name "LTC_2_CS") (class "Default")
      (node (ref "SV3") (pin "25") (pinfunction "25_25") (pintype "passive"))
      (node (ref "SV3") (pin "26") (pinfunction "26_26") (pintype "passive"))
      (node (ref "SV4") (pin "25") (pinfunction "25_25") (pintype "passive"))
      (node (ref "SV4") (pin "26") (pinfunction "26_26") (pintype "passive"))
      (node (ref "U$2") (pin "24") (pinfunction "RB13_24") (pintype "bidirectional"))
    )
    (net (code "58") (name "LTC_2_CS_ISO") (class "Default")
      (node (ref "IC2_\\") (pin "5") (pinfunction "VIC_5") (pintype "input"))
      (node (ref "LTC2_HEAD") (pin "3") (pinfunction "3_3") (pintype "passive"))
    )
    (net (code "59") (name "LTC_2_MISO") (class "Default")
      (node (ref "SV3") (pin "39") (pinfunction "39_39") (pintype "passive"))
      (node (ref "SV3") (pin "40") (pinfunction "40_40") (pintype "passive"))
      (node (ref "SV4") (pin "39") (pinfunction "39_39") (pintype "passive"))
      (node (ref "SV4") (pin "40") (pinfunction "40_40") (pintype "passive"))
      (node (ref "U$2") (pin "15") (pinfunction "RB6_15") (pintype "bidirectional"))
    )
    (net (code "60") (name "LTC_2_MISO_ISO") (class "Default")
      (node (ref "IC2_\\") (pin "6") (pinfunction "VOD_6") (pintype "output"))
      (node (ref "LTC2_HEAD") (pin "1") (pinfunction "1_1") (pintype "passive"))
      (node (ref "LTC2_HEAD") (pin "2") (pinfunction "2_2") (pintype "passive"))
    )
    (net (code "61") (name "LTC_3_CS") (class "Default")
      (node (ref "SV3") (pin "23") (pinfunction "23_23") (pintype "passive"))
      (node (ref "SV3") (pin "24") (pinfunction "24_24") (pintype "passive"))
      (node (ref "SV4") (pin "23") (pinfunction "23_23") (pintype "passive"))
      (node (ref "SV4") (pin "24") (pinfunction "24_24") (pintype "passive"))
      (node (ref "U$2") (pin "25") (pinfunction "RB14_25") (pintype "bidirectional"))
    )
    (net (code "62") (name "LTC_3_CS_ISO") (class "Default")
      (node (ref "IC3_") (pin "5") (pinfunction "VIC_5") (pintype "input"))
      (node (ref "LTC2_HEAD") (pin "4") (pinfunction "4_4") (pintype "passive"))
      (node (ref "LTC3_HEAD") (pin "3") (pinfunction "3_3") (pintype "passive"))
      (node (ref "LTC3_HEAD") (pin "4") (pinfunction "4_4") (pintype "passive"))
    )
    (net (code "63") (name "LTC_3_MISO") (class "Default")
      (node (ref "SV3") (pin "37") (pinfunction "37_37") (pintype "passive"))
      (node (ref "SV3") (pin "38") (pinfunction "38_38") (pintype "passive"))
      (node (ref "SV4") (pin "37") (pinfunction "37_37") (pintype "passive"))
      (node (ref "SV4") (pin "38") (pinfunction "38_38") (pintype "passive"))
      (node (ref "U$2") (pin "16") (pinfunction "RB7_16") (pintype "bidirectional"))
    )
    (net (code "64") (name "LTC_3_MISO_ISO") (class "Default")
      (node (ref "IC3_") (pin "6") (pinfunction "VOD_6") (pintype "output"))
      (node (ref "LTC3_HEAD") (pin "1") (pinfunction "1_1") (pintype "passive"))
      (node (ref "LTC3_HEAD") (pin "2") (pinfunction "2_2") (pintype "passive"))
    )
    (net (code "65") (name "MCLR") (class "Default")
      (node (ref "C1") (pin "1") (pinfunction "1_1") (pintype "passive"))
      (node (ref "PROGRAM") (pin "4") (pinfunction "S_4") (pintype "passive"))
      (node (ref "R52") (pin "2") (pinfunction "2_2") (pintype "passive"))
      (node (ref "R53") (pin "1") (pinfunction "1_1") (pintype "passive"))
    )
    (net (code "66") (name "MOSI") (class "Default")
      (node (ref "SV3") (pin "10") (pinfunction "10_10") (pintype "passive"))
      (node (ref "SV3") (pin "9") (pinfunction "9_9") (pintype "passive"))
      (node (ref "SV4") (pin "10") (pinfunction "10_10") (pintype "passive"))
      (node (ref "SV4") (pin "9") (pinfunction "9_9") (pintype "passive"))
      (node (ref "U$2") (pin "6") (pinfunction "RB2_6") (pintype "bidirectional"))
    )
    (net (code "67") (name "MOSI_ADC") (class "Default")
      (node (ref "ADC_BITS") (pin "5") (pinfunction "5_5") (pintype "passive"))
      (node (ref "ADC_BITS") (pin "6") (pinfunction "6_6") (pintype "passive"))
      (node (ref "U$6") (pin "11") (pinfunction "DIN_11") (pintype "bidirectional"))
    )
    (net (code "68") (name "MOSI_ISO1") (class "Default")
      (node (ref "IC1") (pin "4") (pinfunction "VIB_4") (pintype "input"))
      (node (ref "LTC1_HEAD") (pin "5") (pinfunction "5_5") (pintype "passive"))
      (node (ref "LTC1_HEAD") (pin "6") (pinfunction "6_6") (pintype "passive"))
    )
    (net (code "69") (name "MOSI_ISO2") (class "Default")
      (node (ref "IC2_\\") (pin "4") (pinfunction "VIB_4") (pintype "input"))
      (node (ref "LTC2_HEAD") (pin "5") (pinfunction "5_5") (pintype "passive"))
      (node (ref "LTC2_HEAD") (pin "6") (pinfunction "6_6") (pintype "passive"))
    )
    (net (code "70") (name "MOSI_ISO3") (class "Default")
      (node (ref "IC3_") (pin "4") (pinfunction "VIB_4") (pintype "input"))
      (node (ref "LTC3_HEAD") (pin "5") (pinfunction "5_5") (pintype "passive"))
      (node (ref "LTC3_HEAD") (pin "6") (pinfunction "6_6") (pintype "passive"))
    )
    (net (code "71") (name "Net-(AIN0C-S)") (class "Default")
      (node (ref "AIN0") (pin "3") (pinfunction "S_3") (pintype "passive"))
      (node (ref "U$1") (pin "1") (pinfunction "IN1_1") (pintype "bidirectional"))
      (node (ref "U$6") (pin "1") (pinfunction "CH0_1") (pintype "bidirectional"))
    )
    (net (code "72") (name "Net-(AIN1C-S)") (class "Default")
      (node (ref "AIN1") (pin "3") (pinfunction "S_3") (pintype "passive"))
      (node (ref "U$1") (pin "2") (pinfunction "IN2_2") (pintype "bidirectional"))
      (node (ref "U$6") (pin "2") (pinfunction "CH1_2") (pintype "bidirectional"))
    )
    (net (code "73") (name "Net-(AIN2C-S)") (class "Default")
      (node (ref "AIN2") (pin "3") (pinfunction "S_3") (pintype "passive"))
      (node (ref "U$1") (pin "3") (pinfunction "IN3_3") (pintype "bidirectional"))
      (node (ref "U$6") (pin "3") (pinfunction "CH2_3") (pintype "bidirectional"))
    )
    (net (code "74") (name "Net-(AIN3C-S)") (class "Default")
      (node (ref "AIN3") (pin "3") (pinfunction "S_3") (pintype "passive"))
      (node (ref "U$1") (pin "4") (pinfunction "IN4_4") (pintype "bidirectional"))
      (node (ref "U$6") (pin "4") (pinfunction "CH3_4") (pintype "bidirectional"))
    )
    (net (code "75") (name "Net-(AIN4C-S)") (class "Default")
      (node (ref "AIN4") (pin "3") (pinfunction "S_3") (pintype "passive"))
      (node (ref "U$1") (pin "5") (pinfunction "IN5_5") (pintype "bidirectional"))
      (node (ref "U$6") (pin "5") (pinfunction "CH4_5") (pintype "bidirectional"))
    )
    (net (code "76") (name "Net-(CONTACTORA-S)") (class "Default")
      (node (ref "CONTACTOR") (pin "1") (pinfunction "S_1") (pintype "passive"))
      (node (ref "K1") (pin "S") (pinfunction "S_S") (pintype "passive"))
      (node (ref "K1") (pin "S@") (pinfunction "S_S@") (pintype "passive"))
    )
    (net (code "77") (name "Net-(CONTACTORB-S)") (class "Default")
      (node (ref "CONTACTOR") (pin "2") (pinfunction "S_2") (pintype "passive"))
      (node (ref "K1") (pin "P") (pinfunction "P_P") (pintype "passive"))
      (node (ref "K1") (pin "P@") (pinfunction "P_P@") (pintype "passive"))
    )
    (net (code "78") (name "Net-(D16-PadC)") (class "Default")
      (node (ref "D16") (pin "C") (pinfunction "C_C") (pintype "passive"))
      (node (ref "D17") (pin "C") (pinfunction "C_C") (pintype "passive"))
      (node (ref "D18") (pin "C") (pinfunction "C_C") (pintype "passive"))
      (node (ref "L15") (pin "2") (pinfunction "2_2") (pintype "passive"))
      (node (ref "R50") (pin "1") (pinfunction "1_1") (pintype "passive"))
    )
    (net (code "79") (name "Net-(D28-PadC)") (class "Default")
      (node (ref "D28") (pin "C") (pinfunction "C_C") (pintype "passive"))
      (node (ref "D29") (pin "C") (pinfunction "C_C") (pintype "passive"))
      (node (ref "D30") (pin "C") (pinfunction "C_C") (pintype "passive"))
      (node (ref "L28") (pin "2") (pinfunction "2_2") (pintype "passive"))
      (node (ref "R102") (pin "1") (pinfunction "1_1") (pintype "passive"))
    )
    (net (code "80") (name "Net-(D43-PadC)") (class "Default")
      (node (ref "D43") (pin "C") (pinfunction "C_C") (pintype "passive"))
      (node (ref "D44") (pin "C") (pinfunction "C_C") (pintype "passive"))
      (node (ref "D45") (pin "C") (pinfunction "C_C") (pintype "passive"))
      (node (ref "L43") (pin "2") (pinfunction "2_2") (pintype "passive"))
      (node (ref "R153") (pin "1") (pinfunction "1_1") (pintype "passive"))
    )
    (net (code "81") (name "Net-(IC1-VID)") (class "Default")
      (node (ref "IC1") (pin "11") (pinfunction "VID_11") (pintype "input"))
      (node (ref "LTC1") (pin "P$43") (pinfunction "SDO_P$43") (pintype "bidirectional"))
      (node (ref "R167") (pin "2") (pinfunction "2_2") (pintype "passive"))
      (node (ref "R168") (pin "2") (pinfunction "2_2") (pintype "passive"))
    )
    (net (code "82") (name "Net-(IC1-VOA)") (class "Default")
      (node (ref "IC1") (pin "14") (pinfunction "VOA_14") (pintype "output"))
      (node (ref "LTC1") (pin "P$41") (pinfunction "SCKI_P$41") (pintype "bidirectional"))
    )
    (net (code "83") (name "Net-(IC1-VOB)") (class "Default")
      (node (ref "IC1") (pin "13") (pinfunction "VOB_13") (pintype "output"))
      (node (ref "LTC1") (pin "P$42") (pinfunction "SDI_P$42") (pintype "bidirectional"))
    )
    (net (code "84") (name "Net-(IC1-VOC)") (class "Default")
      (node (ref "IC1") (pin "12") (pinfunction "VOC_12") (pintype "output"))
      (node (ref "LTC1") (pin "P$44") (pinfunction "CSBI_P$44") (pintype "bidirectional"))
    )
    (net (code "85") (name "Net-(IC2_\\-VID)") (class "Default")
      (node (ref "IC2_\\") (pin "11") (pinfunction "VID_11") (pintype "input"))
      (node (ref "LTC2") (pin "P$43") (pinfunction "SDO_P$43") (pintype "bidirectional"))
      (node (ref "R165") (pin "2") (pinfunction "2_2") (pintype "passive"))
      (node (ref "R166") (pin "2") (pinfunction "2_2") (pintype "passive"))
    )
    (net (code "86") (name "Net-(IC2_\\-VOA)") (class "Default")
      (node (ref "IC2_\\") (pin "14") (pinfunction "VOA_14") (pintype "output"))
      (node (ref "LTC2") (pin "P$41") (pinfunction "SCKI_P$41") (pintype "bidirectional"))
    )
    (net (code "87") (name "Net-(IC2_\\-VOB)") (class "Default")
      (node (ref "IC2_\\") (pin "13") (pinfunction "VOB_13") (pintype "output"))
      (node (ref "LTC2") (pin "P$42") (pinfunction "SDI_P$42") (pintype "bidirectional"))
    )
    (net (code "88") (name "Net-(IC2_\\-VOC)") (class "Default")
      (node (ref "IC2_\\") (pin "12") (pinfunction "VOC_12") (pintype "output"))
      (node (ref "LTC2") (pin "P$44") (pinfunction "CSBI_P$44") (pintype "bidirectional"))
    )
    (net (code "89") (name "Net-(IC3_-VID)") (class "Default")
      (node (ref "IC3_") (pin "11") (pinfunction "VID_11") (pintype "input"))
      (node (ref "LTC3") (pin "P$43") (pinfunction "SDO_P$43") (pintype "bidirectional"))
      (node (ref "R163") (pin "2") (pinfunction "2_2") (pintype "passive"))
      (node (ref "R164") (pin "2") (pinfunction "2_2") (pintype "passive"))
    )
    (net (code "90") (name "Net-(IC3_-VOA)") (class "Default")
      (node (ref "IC3_") (pin "14") (pinfunction "VOA_14") (pintype "output"))
      (node (ref "LTC3") (pin "P$41") (pinfunction "SCKI_P$41") (pintype "bidirectional"))
    )
    (net (code "91") (name "Net-(IC3_-VOB)") (class "Default")
      (node (ref "IC3_") (pin "13") (pinfunction "VOB_13") (pintype "output"))
      (node (ref "LTC3") (pin "P$42") (pinfunction "SDI_P$42") (pintype "bidirectional"))
    )
    (net (code "92") (name "Net-(IC3_-VOC)") (class "Default")
      (node (ref "IC3_") (pin "12") (pinfunction "VOC_12") (pintype "output"))
      (node (ref "LTC3") (pin "P$44") (pinfunction "CSBI_P$44") (pintype "bidirectional"))
    )
    (net (code "93") (name "Net-(J19-Pad1)") (class "Default")
      (node (ref "J19") (pin "1") (pinfunction "1_1") (pintype "passive"))
      (node (ref "J20") (pin "1") (pinfunction "1_1") (pintype "passive"))
    )
    (net (code "94") (name "Net-(J19-Pad6)") (class "Default")
      (node (ref "J19") (pin "6") (pinfunction "6_6") (pintype "passive"))
      (node (ref "J20") (pin "6") (pinfunction "6_6") (pintype "passive"))
    )
    (net (code "95") (name "Net-(K1-Pad1)") (class "Default")
      (node (ref "K1") (pin "1") (pinfunction "1_1") (pintype "passive"))
      (node (ref "R169") (pin "1") (pinfunction "1_1") (pintype "passive"))
    )
    (net (code "96") (name "Net-(L17-Pad2)") (class "Default")
      (node (ref "L17") (pin "2") (pinfunction "2_2") (pintype "passive"))
      (node (ref "R48") (pin "1") (pinfunction "1_1") (pintype "passive"))
      (node (ref "R51") (pin "1") (pinfunction "1_1") (pintype "passive"))
    )
    (net (code "97") (name "Net-(L30-Pad2)") (class "Default")
      (node (ref "L30") (pin "2") (pinfunction "2_2") (pintype "passive"))
      (node (ref "R100") (pin "1") (pinfunction "1_1") (pintype "passive"))
      (node (ref "R103") (pin "1") (pinfunction "1_1") (pintype "passive"))
    )
    (net (code "98") (name "Net-(L45-Pad2)") (class "Default")
      (node (ref "L45") (pin "2") (pinfunction "2_2") (pintype "passive"))
      (node (ref "R151") (pin "1") (pinfunction "1_1") (pintype "passive"))
      (node (ref "R154") (pin "1") (pinfunction "1_1") (pintype "passive"))
    )
    (net (code "99") (name "Net-(LED37-PadA)") (class "Default")
      (node (ref "LED37") (pin "A") (pinfunction "A_A") (pintype "passive"))
      (node (ref "R157") (pin "1") (pinfunction "1_1") (pintype "passive"))
    )
    (net (code "100") (name "Net-(LED38-PadA)") (class "Default")
      (node (ref "LED38") (pin "A") (pinfunction "A_A") (pintype "passive"))
      (node (ref "R156") (pin "1") (pinfunction "1_1") (pintype "passive"))
    )
    (net (code "101") (name "Net-(LED40-PadA)") (class "Default")
      (node (ref "LED40") (pin "A") (pinfunction "A_A") (pintype "passive"))
      (node (ref "R158") (pin "1") (pinfunction "1_1") (pintype "passive"))
    )
    (net (code "102") (name "Net-(LTC1-A0)") (class "Default")
      (node (ref "LTC1") (pin "P$37") (pinfunction "A0_P$37") (pintype "bidirectional"))
      (node (ref "U$8") (pin "8") (pinfunction "2_8") (pintype "passive"))
    )
    (net (code "103") (name "Net-(LTC1-A1)") (class "Default")
      (node (ref "LTC1") (pin "P$38") (pinfunction "A1_P$38") (pintype "bidirectional"))
      (node (ref "U$8") (pin "11") (pinfunction "2_11") (pintype "passive"))
    )
    (net (code "104") (name "Net-(LTC1-A2)") (class "Default")
      (node (ref "LTC1") (pin "P$39") (pinfunction "A2_P$39") (pintype "bidirectional"))
      (node (ref "U$8") (pin "14") (pinfunction "2_14") (pintype "passive"))
    )
    (net (code "105") (name "Net-(LTC1-A3)") (class "Default")
      (node (ref "LTC1") (pin "P$40") (pinfunction "A3_P$40") (pintype "bidirectional"))
      (node (ref "U$8") (pin "17") (pinfunction "2_17") (pintype "passive"))
    )
    (net (code "106") (name "Net-(LTC1-C0)") (class "Default")
      (node (ref "D15") (pin "A") (pinfunction "A_A") (pintype "passive"))
      (node (ref "LTC1") (pin "P$26") (pinfunction "C0_P$26") (pintype "bidirectional"))
      (node (ref "LTC1_C0") (pin "P$1") (pinfunction "TP_P$1") (pintype "input"))
      (node (ref "R51") (pin "2") (pinfunction "2_2") (pintype "passive"))
    )
    (net (code "107") (name "Net-(LTC1-C1)") (class "Default")
      (node (ref "C13") (pin "1") (pinfunction "1_1") (pintype "passive"))
      (node (ref "D14") (pin "A") (pinfunction "A_A") (pintype "passive"))
      (node (ref "D15") (pin "C") (pinfunction "C_C") (pintype "passive"))
      (node (ref "LTC1") (pin "P$24") (pinfunction "C1_P$24") (pintype "bidirectional"))
      (node (ref "LTC1_C1") (pin "P$1") (pinfunction "TP_P$1") (pintype "input"))
      (node (ref "R46") (pin "2") (pinfunction "2_2") (pintype "passive"))
    )
    (net (code "108") (name "Net-(LTC1-C2)") (class "Default")
      (node (ref "C12") (pin "1") (pinfunction "1_1") (pintype "passive"))
      (node (ref "D13") (pin "A") (pinfunction "A_A") (pintype "passive"))
      (node (ref "D14") (pin "C") (pinfunction "C_C") (pintype "passive"))
      (node (ref "LTC1") (pin "P$22") (pinfunction "C2_P$22") (pintype "bidirectional"))
      (node (ref "LTC1_C2") (pin "P$1") (pinfunction "TP_P$1") (pintype "input"))
      (node (ref "R42") (pin "2") (pinfunction "2_2") (pintype "passive"))
    )
    (net (code "109") (name "Net-(LTC1-C3)") (class "Default")
      (node (ref "C11") (pin "1") (pinfunction "1_1") (pintype "passive"))
      (node (ref "D12") (pin "A") (pinfunction "A_A") (pintype "passive"))
      (node (ref "D13") (pin "C") (pinfunction "C_C") (pintype "passive"))
      (node (ref "LTC1") (pin "P$20") (pinfunction "C3_P$20") (pintype "bidirectional"))
      (node (ref "LTC1_C3") (pin "P$1") (pinfunction "TP_P$1") (pintype "input"))
      (node (ref "R38") (pin "2") (pinfunction "2_2") (pintype "passive"))
    )
    (net (code "110") (name "Net-(LTC1-C4)") (class "Default")
      (node (ref "C10") (pin "1") (pinfunction "1_1") (pintype "passive"))
      (node (ref "D11") (pin "A") (pinfunction "A_A") (pintype "passive"))
      (node (ref "D12") (pin "C") (pinfunction "C_C") (pintype "passive"))
      (node (ref "LTC1") (pin "P$18") (pinfunction "C4_P$18") (pintype "bidirectional"))
      (node (ref "LTC1_C4") (pin "P$1") (pinfunction "TP_P$1") (pintype "input"))
      (node (ref "R34") (pin "2") (pinfunction "2_2") (pintype "passive"))
    )
    (net (code "111") (name "Net-(LTC1-C5)") (class "Default")
      (node (ref "C9") (pin "1") (pinfunction "1_1") (pintype "passive"))
      (node (ref "D10") (pin "A") (pinfunction "A_A") (pintype "passive"))
      (node (ref "D11") (pin "C") (pinfunction "C_C") (pintype "passive"))
      (node (ref "LTC1") (pin "P$16") (pinfunction "C5_P$16") (pintype "bidirectional"))
      (node (ref "LTC1_C5") (pin "P$1") (pinfunction "TP_P$1") (pintype "input"))
      (node (ref "R30") (pin "2") (pinfunction "2_2") (pintype "passive"))
    )
    (net (code "112") (name "Net-(LTC1-C6)") (class "Default")
      (node (ref "C8") (pin "1") (pinfunction "1_1") (pintype "passive"))
      (node (ref "D10") (pin "C") (pinfunction "C_C") (pintype "passive"))
      (node (ref "D9") (pin "A") (pinfunction "A_A") (pintype "passive"))
      (node (ref "LTC1") (pin "P$14") (pinfunction "C6_P$14") (pintype "bidirectional"))
      (node (ref "LTC1_C6") (pin "P$1") (pinfunction "TP_P$1") (pintype "input"))
      (node (ref "R26") (pin "2") (pinfunction "2_2") (pintype "passive"))
    )
    (net (code "113") (name "Net-(LTC1-C7)") (class "Default")
      (node (ref "C7") (pin "1") (pinfunction "1_1") (pintype "passive"))
      (node (ref "D8") (pin "A") (pinfunction "A_A") (pintype "passive"))
      (node (ref "D9") (pin "C") (pinfunction "C_C") (pintype "passive"))
      (node (ref "LTC1") (pin "P$12") (pinfunction "C7_P$12") (pintype "bidirectional"))
      (node (ref "LTC1_C7") (pin "P$1") (pinfunction "TP_P$1") (pintype "input"))
      (node (ref "R22") (pin "2") (pinfunction "2_2") (pintype "passive"))
    )
    (net (code "114") (name "Net-(LTC1-C8)") (class "Default")
      (node (ref "C6") (pin "1") (pinfunction "1_1") (pintype "passive"))
      (node (ref "D7") (pin "A") (pinfunction "A_A") (pintype "passive"))
      (node (ref "D8") (pin "C") (pinfunction "C_C") (pintype "passive"))
      (node (ref "LTC1") (pin "P$10") (pinfunction "C8_P$10") (pintype "bidirectional"))
      (node (ref "LTC1_C8") (pin "P$1") (pinfunction "TP_P$1") (pintype "input"))
      (node (ref "R18") (pin "2") (pinfunction "2_2") (pintype "passive"))
    )
    (net (code "115") (name "Net-(LTC1-C9)") (class "Default")
      (node (ref "C5") (pin "1") (pinfunction "1_1") (pintype "passive"))
      (node (ref "D6") (pin "A") (pinfunction "A_A") (pintype "passive"))
      (node (ref "D7") (pin "C") (pinfunction "C_C") (pintype "passive"))
      (node (ref "LTC1") (pin "P$8") (pinfunction "C9_P$8") (pintype "bidirectional"))
      (node (ref "LTC1_C9") (pin "P$1") (pinfunction "TP_P$1") (pintype "input"))
      (node (ref "R14") (pin "2") (pinfunction "2_2") (pintype "passive"))
    )
    (net (code "116") (name "Net-(LTC1-C10)") (class "Default")
      (node (ref "C4") (pin "1") (pinfunction "1_1") (pintype "passive"))
      (node (ref "D6") (pin "C") (pinfunction "C_C") (pintype "passive"))
      (node (ref "LTC1") (pin "P$2") (pinfunction "C12_P$2") (pintype "bidirectional"))
      (node (ref "LTC1") (pin "P$4") (pinfunction "C11_P$4") (pintype "bidirectional"))
      (node (ref "LTC1") (pin "P$6") (pinfunction "C10_P$6") (pintype "bidirectional"))
      (node (ref "LTC1_C10") (pin "P$1") (pinfunction "TP_P$1") (pintype "input"))
      (node (ref "R10") (pin "2") (pinfunction "2_2") (pintype "passive"))
    )
    (net (code "117") (name "Net-(LTC1-S1)") (class "Default")
      (node (ref "LTC1") (pin "P$25") (pinfunction "S1_P$25") (pintype "bidirectional"))
      (node (ref "LTC1_S1") (pin "P$1") (pinfunction "TP_P$1") (pintype "input"))
      (node (ref "R47") (pin "2") (pinfunction "2_2") (pintype "passive"))
    )
    (net (code "118") (name "Net-(LTC1-S2)") (class "Default")
      (node (ref "LTC1") (pin "P$23") (pinfunction "S2_P$23") (pintype "bidirectional"))
      (node (ref "LTC1_S2") (pin "P$1") (pinfunction "TP_P$1") (pintype "input"))
      (node (ref "R43") (pin "2") (pinfunction "2_2") (pintype "passive"))
    )
    (net (code "119") (name "Net-(LTC1-S3)") (class "Default")
      (node (ref "LTC1") (pin "P$21") (pinfunction "S3_P$21") (pintype "bidirectional"))
      (node (ref "LTC1_S3") (pin "P$1") (pinfunction "TP_P$1") (pintype "input"))
      (node (ref "R39") (pin "2") (pinfunction "2_2") (pintype "passive"))
    )
    (net (code "120") (name "Net-(LTC1-S4)") (class "Default")
      (node (ref "LTC1") (pin "P$19") (pinfunction "S4_P$19") (pintype "bidirectional"))
      (node (ref "LTC1_S4") (pin "P$1") (pinfunction "TP_P$1") (pintype "input"))
      (node (ref "R35") (pin "2") (pinfunction "2_2") (pintype "passive"))
    )
    (net (code "121") (name "Net-(LTC1-S5)") (class "Default")
      (node (ref "LTC1") (pin "P$17") (pinfunction "S5_P$17") (pintype "bidirectional"))
      (node (ref "LTC1_S5") (pin "P$1") (pinfunction "TP_P$1") (pintype "input"))
      (node (ref "R31") (pin "2") (pinfunction "2_2") (pintype "passive"))
    )
    (net (code "122") (name "Net-(LTC1-S6)") (class "Default")
      (node (ref "LTC1") (pin "P$15") (pinfunction "S6_P$15") (pintype "bidirectional"))
      (node (ref "LTC1_S6") (pin "P$1") (pinfunction "TP_P$1") (pintype "input"))
      (node (ref "R27") (pin "2") (pinfunction "2_2") (pintype "passive"))
    )
    (net (code "123") (name "Net-(LTC1-S7)") (class "Default")
      (node (ref "LTC1") (pin "P$13") (pinfunction "S7_P$13") (pintype "bidirectional"))
      (node (ref "LTC1_S7") (pin "P$1") (pinfunction "TP_P$1") (pintype "input"))
      (node (ref "R23") (pin "2") (pinfunction "2_2") (pintype "passive"))
    )
    (net (code "124") (name "Net-(LTC1-S8)") (class "Default")
      (node (ref "LTC1") (pin "P$11") (pinfunction "S8_P$11") (pintype "bidirectional"))
      (node (ref "LTC1_S8") (pin "P$1") (pinfunction "TP_P$1") (pintype "input"))
      (node (ref "R19") (pin "2") (pinfunction "2_2") (pintype "passive"))
    )
    (net (code "125") (name "Net-(LTC1-S9)") (class "Default")
      (node (ref "LTC1") (pin "P$9") (pinfunction "S9_P$9") (pintype "bidirectional"))
      (node (ref "LTC1_S9") (pin "P$1") (pinfunction "TP_P$1") (pintype "input"))
      (node (ref "R15") (pin "2") (pinfunction "2_2") (pintype "passive"))
    )
    (net (code "126") (name "Net-(LTC1-S10)") (class "Default")
      (node (ref "LTC1") (pin "P$7") (pinfunction "S10_P$7") (pintype "bidirectional"))
      (node (ref "LTC1_S10") (pin "P$1") (pinfunction "TP_P$1") (pintype "input"))
      (node (ref "R11") (pin "2") (pinfunction "2_2") (pintype "passive"))
    )
    (net (code "127") (name "Net-(LTC1-TOS)") (class "Default")
      (node (ref "LTC1") (pin "P$33") (pinfunction "TOS_P$33") (pintype "bidirectional"))
      (node (ref "R5") (pin "1") (pinfunction "1_1") (pintype "passive"))
    )
    (net (code "128") (name "Net-(LTC1-V+)") (class "Default")
      (node (ref "C14") (pin "1") (pinfunction "1_1") (pintype "passive"))
      (node (ref "LTC1") (pin "P$1") (pinfunction "V+_P$1") (pintype "bidirectional"))
      (node (ref "LTC1_V+") (pin "P$1") (pinfunction "TP_P$1") (pintype "input"))
      (node (ref "R50") (pin "2") (pinfunction "2_2") (pintype "passive"))
    )
    (net (code "129") (name "Net-(LTC1-VREF)") (class "Default")
      (node (ref "C15") (pin "1") (pinfunction "1_1") (pintype "passive"))
      (node (ref "LTC1") (pin "P$31") (pinfunction "VREF_P$31") (pintype "bidirectional"))
    )
    (net (code "130") (name "Net-(LTC1-WDTB)") (class "Default")
      (node (ref "LTC1") (pin "P$34") (pinfunction "WDTB_P$34") (pintype "bidirectional"))
      (node (ref "U$8") (pin "2") (pinfunction "2_2") (pintype "passive"))
    )
    (net (code "131") (name "Net-(LTC2-A0)") (class "Default")
      (node (ref "LTC2") (pin "P$37") (pinfunction "A0_P$37") (pintype "bidirectional"))
      (node (ref "U$9") (pin "8") (pinfunction "2_8") (pintype "passive"))
    )
    (net (code "132") (name "Net-(LTC2-A1)") (class "Default")
      (node (ref "LTC2") (pin "P$38") (pinfunction "A1_P$38") (pintype "bidirectional"))
      (node (ref "U$9") (pin "11") (pinfunction "2_11") (pintype "passive"))
    )
    (net (code "133") (name "Net-(LTC2-A2)") (class "Default")
      (node (ref "LTC2") (pin "P$39") (pinfunction "A2_P$39") (pintype "bidirectional"))
      (node (ref "U$9") (pin "14") (pinfunction "2_14") (pintype "passive"))
    )
    (net (code "134") (name "Net-(LTC2-A3)") (class "Default")
      (node (ref "LTC2") (pin "P$40") (pinfunction "A3_P$40") (pintype "bidirectional"))
      (node (ref "U$9") (pin "17") (pinfunction "2_17") (pintype "passive"))
    )
    (net (code "135") (name "Net-(LTC2-C0)") (class "Default")
      (node (ref "D27") (pin "A") (pinfunction "A_A") (pintype "passive"))
      (node (ref "LTC2") (pin "P$26") (pinfunction "C0_P$26") (pintype "bidirectional"))
      (node (ref "LTC2_C0") (pin "P$1") (pinfunction "TP_P$1") (pintype "input"))
      (node (ref "R103") (pin "2") (pinfunction "2_2") (pintype "passive"))
    )
    (net (code "136") (name "Net-(LTC2-C1)") (class "Default")
      (node (ref "C29") (pin "1") (pinfunction "1_1") (pintype "passive"))
      (node (ref "D26") (pin "A") (pinfunction "A_A") (pintype "passive"))
      (node (ref "D27") (pin "C") (pinfunction "C_C") (pintype "passive"))
      (node (ref "LTC2") (pin "P$24") (pinfunction "C1_P$24") (pintype "bidirectional"))
      (node (ref "LTC2_C1") (pin "P$1") (pinfunction "TP_P$1") (pintype "input"))
      (node (ref "R98") (pin "2") (pinfunction "2_2") (pintype "passive"))
    )
    (net (code "137") (name "Net-(LTC2-C2)") (class "Default")
      (node (ref "C28") (pin "1") (pinfunction "1_1") (pintype "passive"))
      (node (ref "D25") (pin "A") (pinfunction "A_A") (pintype "passive"))
      (node (ref "D26") (pin "C") (pinfunction "C_C") (pintype "passive"))
      (node (ref "LTC2") (pin "P$22") (pinfunction "C2_P$22") (pintype "bidirectional"))
      (node (ref "LTC2_C2") (pin "P$1") (pinfunction "TP_P$1") (pintype "input"))
      (node (ref "R94") (pin "2") (pinfunction "2_2") (pintype "passive"))
    )
    (net (code "138") (name "Net-(LTC2-C3)") (class "Default")
      (node (ref "C27") (pin "1") (pinfunction "1_1") (pintype "passive"))
      (node (ref "D24") (pin "A") (pinfunction "A_A") (pintype "passive"))
      (node (ref "D25") (pin "C") (pinfunction "C_C") (pintype "passive"))
      (node (ref "LTC2") (pin "P$20") (pinfunction "C3_P$20") (pintype "bidirectional"))
      (node (ref "LTC2_C3") (pin "P$1") (pinfunction "TP_P$1") (pintype "input"))
      (node (ref "R90") (pin "2") (pinfunction "2_2") (pintype "passive"))
    )
    (net (code "139") (name "Net-(LTC2-C4)") (class "Default")
      (node (ref "C26") (pin "1") (pinfunction "1_1") (pintype "passive"))
      (node (ref "D23") (pin "A") (pinfunction "A_A") (pintype "passive"))
      (node (ref "D24") (pin "C") (pinfunction "C_C") (pintype "passive"))
      (node (ref "LTC2") (pin "P$18") (pinfunction "C4_P$18") (pintype "bidirectional"))
      (node (ref "LTC2_C4") (pin "P$1") (pinfunction "TP_P$1") (pintype "input"))
      (node (ref "R86") (pin "2") (pinfunction "2_2") (pintype "passive"))
    )
    (net (code "140") (name "Net-(LTC2-C5)") (class "Default")
      (node (ref "C25") (pin "1") (pinfunction "1_1") (pintype "passive"))
      (node (ref "D22") (pin "A") (pinfunction "A_A") (pintype "passive"))
      (node (ref "D23") (pin "C") (pinfunction "C_C") (pintype "passive"))
      (node (ref "LTC2") (pin "P$16") (pinfunction "C5_P$16") (pintype "bidirectional"))
      (node (ref "LTC2_C5") (pin "P$1") (pinfunction "TP_P$1") (pintype "input"))
      (node (ref "R82") (pin "2") (pinfunction "2_2") (pintype "passive"))
    )
    (net (code "141") (name "Net-(LTC2-C6)") (class "Default")
      (node (ref "C24") (pin "1") (pinfunction "1_1") (pintype "passive"))
      (node (ref "D21") (pin "A") (pinfunction "A_A") (pintype "passive"))
      (node (ref "D22") (pin "C") (pinfunction "C_C") (pintype "passive"))
      (node (ref "LTC2") (pin "P$14") (pinfunction "C6_P$14") (pintype "bidirectional"))
      (node (ref "LTC2_C6") (pin "P$1") (pinfunction "TP_P$1") (pintype "input"))
      (node (ref "R78") (pin "2") (pinfunction "2_2") (pintype "passive"))
    )
    (net (code "142") (name "Net-(LTC2-C7)") (class "Default")
      (node (ref "C23") (pin "1") (pinfunction "1_1") (pintype "passive"))
      (node (ref "D20") (pin "A") (pinfunction "A_A") (pintype "passive"))
      (node (ref "D21") (pin "C") (pinfunction "C_C") (pintype "passive"))
      (node (ref "LTC2") (pin "P$12") (pinfunction "C7_P$12") (pintype "bidirectional"))
      (node (ref "LTC2_C7") (pin "P$1") (pinfunction "TP_P$1") (pintype "input"))
      (node (ref "R74") (pin "2") (pinfunction "2_2") (pintype "passive"))
    )
    (net (code "143") (name "Net-(LTC2-C8)") (class "Default")
      (node (ref "C21") (pin "1") (pinfunction "1_1") (pintype "passive"))
      (node (ref "D19") (pin "A") (pinfunction "A_A") (pintype "passive"))
      (node (ref "D20") (pin "C") (pinfunction "C_C") (pintype "passive"))
      (node (ref "LTC2") (pin "P$10") (pinfunction "C8_P$10") (pintype "bidirectional"))
      (node (ref "LTC2_C8") (pin "P$1") (pinfunction "TP_P$1") (pintype "input"))
      (node (ref "R70") (pin "2") (pinfunction "2_2") (pintype "passive"))
    )
    (net (code "144") (name "Net-(LTC2-C9)") (class "Default")
      (node (ref "C20") (pin "1") (pinfunction "1_1") (pintype "passive"))
      (node (ref "D19") (pin "C") (pinfunction "C_C") (pintype "passive"))
      (node (ref "D4") (pin "A") (pinfunction "A_A") (pintype "passive"))
      (node (ref "LTC2") (pin "P$8") (pinfunction "C9_P$8") (pintype "bidirectional"))
      (node (ref "LTC2_C9") (pin "P$1") (pinfunction "TP_P$1") (pintype "input"))
      (node (ref "R66") (pin "2") (pinfunction "2_2") (pintype "passive"))
    )
    (net (code "145") (name "Net-(LTC2-C10)") (class "Default")
      (node (ref "C19") (pin "1") (pinfunction "1_1") (pintype "passive"))
      (node (ref "D4") (pin "C") (pinfunction "C_C") (pintype "passive"))
      (node (ref "LTC2") (pin "P$2") (pinfunction "C12_P$2") (pintype "bidirectional"))
      (node (ref "LTC2") (pin "P$4") (pinfunction "C11_P$4") (pintype "bidirectional"))
      (node (ref "LTC2") (pin "P$6") (pinfunction "C10_P$6") (pintype "bidirectional"))
      (node (ref "LTC2_C10") (pin "P$1") (pinfunction "TP_P$1") (pintype "input"))
      (node (ref "R62") (pin "2") (pinfunction "2_2") (pintype "passive"))
    )
    (net (code "146") (name "Net-(LTC2-S1)") (class "Default")
      (node (ref "LTC2") (pin "P$25") (pinfunction "S1_P$25") (pintype "bidirectional"))
      (node (ref "LTC2_S1") (pin "P$1") (pinfunction "TP_P$1") (pintype "input"))
      (node (ref "R99") (pin "2") (pinfunction "2_2") (pintype "passive"))
    )
    (net (code "147") (name "Net-(LTC2-S2)") (class "Default")
      (node (ref "LTC2") (pin "P$23") (pinfunction "S2_P$23") (pintype "bidirectional"))
      (node (ref "LTC2_S2") (pin "P$1") (pinfunction "TP_P$1") (pintype "input"))
      (node (ref "R95") (pin "2") (pinfunction "2_2") (pintype "passive"))
    )
    (net (code "148") (name "Net-(LTC2-S3)") (class "Default")
      (node (ref "LTC2") (pin "P$21") (pinfunction "S3_P$21") (pintype "bidirectional"))
      (node (ref "LTC2_S3") (pin "P$1") (pinfunction "TP_P$1") (pintype "input"))
      (node (ref "R91") (pin "2") (pinfunction "2_2") (pintype "passive"))
    )
    (net (code "149") (name "Net-(LTC2-S4)") (class "Default")
      (node (ref "LTC2") (pin "P$19") (pinfunction "S4_P$19") (pintype "bidirectional"))
      (node (ref "LTC2_S4") (pin "P$1") (pinfunction "TP_P$1") (pintype "input"))
      (node (ref "R87") (pin "2") (pinfunction "2_2") (pintype "passive"))
    )
    (net (code "150") (name "Net-(LTC2-S5)") (class "Default")
      (node (ref "LTC2") (pin "P$17") (pinfunction "S5_P$17") (pintype "bidirectional"))
      (node (ref "LTC2_S5") (pin "P$1") (pinfunction "TP_P$1") (pintype "input"))
      (node (ref "R83") (pin "2") (pinfunction "2_2") (pintype "passive"))
    )
    (net (code "151") (name "Net-(LTC2-S6)") (class "Default")
      (node (ref "LTC2") (pin "P$15") (pinfunction "S6_P$15") (pintype "bidirectional"))
      (node (ref "LTC2_S6") (pin "P$1") (pinfunction "TP_P$1") (pintype "input"))
      (node (ref "R79") (pin "2") (pinfunction "2_2") (pintype "passive"))
    )
    (net (code "152") (name "Net-(LTC2-S7)") (class "Default")
      (node (ref "LTC2") (pin "P$13") (pinfunction "S7_P$13") (pintype "bidirectional"))
      (node (ref "LTC2_S7") (pin "P$1") (pinfunction "TP_P$1") (pintype "input"))
      (node (ref "R75") (pin "2") (pinfunction "2_2") (pintype "passive"))
    )
    (net (code "153") (name "Net-(LTC2-S8)") (class "Default")
      (node (ref "LTC2") (pin "P$11") (pinfunction "S8_P$11") (pintype "bidirectional"))
      (node (ref "LTC2_S8") (pin "P$1") (pinfunction "TP_P$1") (pintype "input"))
      (node (ref "R71") (pin "2") (pinfunction "2_2") (pintype "passive"))
    )
    (net (code "154") (name "Net-(LTC2-S9)") (class "Default")
      (node (ref "LTC2") (pin "P$9") (pinfunction "S9_P$9") (pintype "bidirectional"))
      (node (ref "LTC2_S9") (pin "P$1") (pinfunction "TP_P$1") (pintype "input"))
      (node (ref "R67") (pin "2") (pinfunction "2_2") (pintype "passive"))
    )
    (net (code "155") (name "Net-(LTC2-S10)") (class "Default")
      (node (ref "LTC2") (pin "P$7") (pinfunction "S10_P$7") (pintype "bidirectional"))
      (node (ref "LTC2_S10") (pin "P$1") (pinfunction "TP_P$1") (pintype "input"))
      (node (ref "R63") (pin "2") (pinfunction "2_2") (pintype "passive"))
    )
    (net (code "156") (name "Net-(LTC2-TOS)") (class "Default")
      (node (ref "LTC2") (pin "P$33") (pinfunction "TOS_P$33") (pintype "bidirectional"))
      (node (ref "R104") (pin "1") (pinfunction "1_1") (pintype "passive"))
    )
    (net (code "157") (name "Net-(LTC2-V+)") (class "Default")
      (node (ref "C30") (pin "1") (pinfunction "1_1") (pintype "passive"))
      (node (ref "LTC2") (pin "P$1") (pinfunction "V+_P$1") (pintype "bidirectional"))
      (node (ref "LTC2_V+") (pin "P$1") (pinfunction "TP_P$1") (pintype "input"))
      (node (ref "R102") (pin "2") (pinfunction "2_2") (pintype "passive"))
    )
    (net (code "158") (name "Net-(LTC2-VREF)") (class "Default")
      (node (ref "C32") (pin "1") (pinfunction "1_1") (pintype "passive"))
      (node (ref "LTC2") (pin "P$31") (pinfunction "VREF_P$31") (pintype "bidirectional"))
    )
    (net (code "159") (name "Net-(LTC2-WDTB)") (class "Default")
      (node (ref "LTC2") (pin "P$34") (pinfunction "WDTB_P$34") (pintype "bidirectional"))
      (node (ref "U$9") (pin "2") (pinfunction "2_2") (pintype "passive"))
    )
    (net (code "160") (name "Net-(LTC3-A0)") (class "Default")
      (node (ref "LTC3") (pin "P$37") (pinfunction "A0_P$37") (pintype "bidirectional"))
      (node (ref "U$10") (pin "8") (pinfunction "2_8") (pintype "passive"))
    )
    (net (code "161") (name "Net-(LTC3-A1)") (class "Default")
      (node (ref "LTC3") (pin "P$38") (pinfunction "A1_P$38") (pintype "bidirectional"))
      (node (ref "U$10") (pin "11") (pinfunction "2_11") (pintype "passive"))
    )
    (net (code "162") (name "Net-(LTC3-A2)") (class "Default")
      (node (ref "LTC3") (pin "P$39") (pinfunction "A2_P$39") (pintype "bidirectional"))
      (node (ref "U$10") (pin "14") (pinfunction "2_14") (pintype "passive"))
    )
    (net (code "163") (name "Net-(LTC3-A3)") (class "Default")
      (node (ref "LTC3") (pin "P$40") (pinfunction "A3_P$40") (pintype "bidirectional"))
      (node (ref "U$10") (pin "17") (pinfunction "2_17") (pintype "passive"))
    )
    (net (code "164") (name "Net-(LTC3-C0)") (class "Default")
      (node (ref "D42") (pin "A") (pinfunction "A_A") (pintype "passive"))
      (node (ref "LTC3") (pin "P$26") (pinfunction "C0_P$26") (pintype "bidirectional"))
      (node (ref "LTC3_C0") (pin "P$1") (pinfunction "TP_P$1") (pintype "input"))
      (node (ref "R154") (pin "2") (pinfunction "2_2") (pintype "passive"))
    )
    (net (code "165") (name "Net-(LTC3-C1)") (class "Default")
      (node (ref "C44") (pin "1") (pinfunction "1_1") (pintype "passive"))
      (node (ref "D41") (pin "A") (pinfunction "A_A") (pintype "passive"))
      (node (ref "D42") (pin "C") (pinfunction "C_C") (pintype "passive"))
      (node (ref "LTC3") (pin "P$24") (pinfunction "C1_P$24") (pintype "bidirectional"))
      (node (ref "LTC3_C1") (pin "P$1") (pinfunction "TP_P$1") (pintype "input"))
      (node (ref "R149") (pin "2") (pinfunction "2_2") (pintype "passive"))
    )
    (net (code "166") (name "Net-(LTC3-C2)") (class "Default")
      (node (ref "C43") (pin "1") (pinfunction "1_1") (pintype "passive"))
      (node (ref "D40") (pin "A") (pinfunction "A_A") (pintype "passive"))
      (node (ref "D41") (pin "C") (pinfunction "C_C") (pintype "passive"))
      (node (ref "LTC3") (pin "P$22") (pinfunction "C2_P$22") (pintype "bidirectional"))
      (node (ref "LTC3_C2") (pin "P$1") (pinfunction "TP_P$1") (pintype "input"))
      (node (ref "R145") (pin "2") (pinfunction "2_2") (pintype "passive"))
    )
    (net (code "167") (name "Net-(LTC3-C3)") (class "Default")
      (node (ref "C42") (pin "1") (pinfunction "1_1") (pintype "passive"))
      (node (ref "D39") (pin "A") (pinfunction "A_A") (pintype "passive"))
      (node (ref "D40") (pin "C") (pinfunction "C_C") (pintype "passive"))
      (node (ref "LTC3") (pin "P$20") (pinfunction "C3_P$20") (pintype "bidirectional"))
      (node (ref "LTC3_C3") (pin "P$1") (pinfunction "TP_P$1") (pintype "input"))
      (node (ref "R141") (pin "2") (pinfunction "2_2") (pintype "passive"))
    )
    (net (code "168") (name "Net-(LTC3-C4)") (class "Default")
      (node (ref "C41") (pin "1") (pinfunction "1_1") (pintype "passive"))
      (node (ref "D38") (pin "A") (pinfunction "A_A") (pintype "passive"))
      (node (ref "D39") (pin "C") (pinfunction "C_C") (pintype "passive"))
      (node (ref "LTC3") (pin "P$18") (pinfunction "C4_P$18") (pintype "bidirectional"))
      (node (ref "LTC3_C4") (pin "P$1") (pinfunction "TP_P$1") (pintype "input"))
      (node (ref "R137") (pin "2") (pinfunction "2_2") (pintype "passive"))
    )
    (net (code "169") (name "Net-(LTC3-C5)") (class "Default")
      (node (ref "C40") (pin "1") (pinfunction "1_1") (pintype "passive"))
      (node (ref "D37") (pin "A") (pinfunction "A_A") (pintype "passive"))
      (node (ref "D38") (pin "C") (pinfunction "C_C") (pintype "passive"))
      (node (ref "LTC3") (pin "P$16") (pinfunction "C5_P$16") (pintype "bidirectional"))
      (node (ref "LTC3_C5") (pin "P$1") (pinfunction "TP_P$1") (pintype "input"))
      (node (ref "R133") (pin "2") (pinfunction "2_2") (pintype "passive"))
    )
    (net (code "170") (name "Net-(LTC3-C6)") (class "Default")
      (node (ref "C39") (pin "1") (pinfunction "1_1") (pintype "passive"))
      (node (ref "D36") (pin "A") (pinfunction "A_A") (pintype "passive"))
      (node (ref "D37") (pin "C") (pinfunction "C_C") (pintype "passive"))
      (node (ref "LTC3") (pin "P$14") (pinfunction "C6_P$14") (pintype "bidirectional"))
      (node (ref "LTC3_C6") (pin "P$1") (pinfunction "TP_P$1") (pintype "input"))
      (node (ref "R129") (pin "2") (pinfunction "2_2") (pintype "passive"))
    )
    (net (code "171") (name "Net-(LTC3-C7)") (class "Default")
      (node (ref "C38") (pin "1") (pinfunction "1_1") (pintype "passive"))
      (node (ref "D35") (pin "A") (pinfunction "A_A") (pintype "passive"))
      (node (ref "D36") (pin "C") (pinfunction "C_C") (pintype "passive"))
      (node (ref "LTC3") (pin "P$12") (pinfunction "C7_P$12") (pintype "bidirectional"))
      (node (ref "LTC3_C7") (pin "P$1") (pinfunction "TP_P$1") (pintype "input"))
      (node (ref "R125") (pin "2") (pinfunction "2_2") (pintype "passive"))
    )
    (net (code "172") (name "Net-(LTC3-C8)") (class "Default")
      (node (ref "C37") (pin "1") (pinfunction "1_1") (pintype "passive"))
      (node (ref "D34") (pin "A") (pinfunction "A_A") (pintype "passive"))
      (node (ref "D35") (pin "C") (pinfunction "C_C") (pintype "passive"))
      (node (ref "LTC3") (pin "P$10") (pinfunction "C8_P$10") (pintype "bidirectional"))
      (node (ref "LTC3_C8") (pin "P$1") (pinfunction "TP_P$1") (pintype "input"))
      (node (ref "R121") (pin "2") (pinfunction "2_2") (pintype "passive"))
    )
    (net (code "173") (name "Net-(LTC3-C9)") (class "Default")
      (node (ref "C36") (pin "1") (pinfunction "1_1") (pintype "passive"))
      (node (ref "D33") (pin "A") (pinfunction "A_A") (pintype "passive"))
      (node (ref "D34") (pin "C") (pinfunction "C_C") (pintype "passive"))
      (node (ref "LTC3") (pin "P$8") (pinfunction "C9_P$8") (pintype "bidirectional"))
      (node (ref "LTC3_C9") (pin "P$1") (pinfunction "TP_P$1") (pintype "input"))
      (node (ref "R117") (pin "2") (pinfunction "2_2") (pintype "passive"))
    )
    (net (code "174") (name "Net-(LTC3-C10)") (class "Default")
      (node (ref "C35") (pin "1") (pinfunction "1_1") (pintype "passive"))
      (node (ref "D33") (pin "C") (pinfunction "C_C") (pintype "passive"))
      (node (ref "LTC3") (pin "P$2") (pinfunction "C12_P$2") (pintype "bidirectional"))
      (node (ref "LTC3") (pin "P$4") (pinfunction "C11_P$4") (pintype "bidirectional"))
      (node (ref "LTC3") (pin "P$6") (pinfunction "C10_P$6") (pintype "bidirectional"))
      (node (ref "LTC3_C10") (pin "P$1") (pinfunction "TP_P$1") (pintype "input"))
      (node (ref "R113") (pin "2") (pinfunction "2_2") (pintype "passive"))
    )
    (net (code "175") (name "Net-(LTC3-S1)") (class "Default")
      (node (ref "LTC3") (pin "P$25") (pinfunction "S1_P$25") (pintype "bidirectional"))
      (node (ref "LTC3_S1") (pin "P$1") (pinfunction "TP_P$1") (pintype "input"))
      (node (ref "R150") (pin "2") (pinfunction "2_2") (pintype "passive"))
    )
    (net (code "176") (name "Net-(LTC3-S2)") (class "Default")
      (node (ref "LTC3") (pin "P$23") (pinfunction "S2_P$23") (pintype "bidirectional"))
      (node (ref "LTC3_S2") (pin "P$1") (pinfunction "TP_P$1") (pintype "input"))
      (node (ref "R146") (pin "2") (pinfunction "2_2") (pintype "passive"))
    )
    (net (code "177") (name "Net-(LTC3-S3)") (class "Default")
      (node (ref "LTC3") (pin "P$21") (pinfunction "S3_P$21") (pintype "bidirectional"))
      (node (ref "LTC3_S3") (pin "P$1") (pinfunction "TP_P$1") (pintype "input"))
      (node (ref "R142") (pin "2") (pinfunction "2_2") (pintype "passive"))
    )
    (net (code "178") (name "Net-(LTC3-S4)") (class "Default")
      (node (ref "LTC3") (pin "P$19") (pinfunction "S4_P$19") (pintype "bidirectional"))
      (node (ref "LTC3_S4") (pin "P$1") (pinfunction "TP_P$1") (pintype "input"))
      (node (ref "R138") (pin "2") (pinfunction "2_2") (pintype "passive"))
    )
    (net (code "179") (name "Net-(LTC3-S5)") (class "Default")
      (node (ref "LTC3") (pin "P$17") (pinfunction "S5_P$17") (pintype "bidirectional"))
      (node (ref "LTC3_S5") (pin "P$1") (pinfunction "TP_P$1") (pintype "input"))
      (node (ref "R134") (pin "2") (pinfunction "2_2") (pintype "passive"))
    )
    (net (code "180") (name "Net-(LTC3-S6)") (class "Default")
      (node (ref "LTC3") (pin "P$15") (pinfunction "S6_P$15") (pintype "bidirectional"))
      (node (ref "LTC3_S6") (pin "P$1") (pinfunction "TP_P$1") (pintype "input"))
      (node (ref "R130") (pin "2") (pinfunction "2_2") (pintype "passive"))
    )
    (net (code "181") (name "Net-(LTC3-S7)") (class "Default")
      (node (ref "LTC3") (pin "P$13") (pinfunction "S7_P$13") (pintype "bidirectional"))
      (node (ref "LTC3_S7") (pin "P$1") (pinfunction "TP_P$1") (pintype "input"))
      (node (ref "R126") (pin "2") (pinfunction "2_2") (pintype "passive"))
    )
    (net (code "182") (name "Net-(LTC3-S8)") (class "Default")
      (node (ref "LTC3") (pin "P$11") (pinfunction "S8_P$11") (pintype "bidirectional"))
      (node (ref "LTC3_S8") (pin "P$1") (pinfunction "TP_P$1") (pintype "input"))
      (node (ref "R122") (pin "2") (pinfunction "2_2") (pintype "passive"))
    )
    (net (code "183") (name "Net-(LTC3-S9)") (class "Default")
      (node (ref "LTC3") (pin "P$9") (pinfunction "S9_P$9") (pintype "bidirectional"))
      (node (ref "LTC3_S9") (pin "P$1") (pinfunction "TP_P$1") (pintype "input"))
      (node (ref "R118") (pin "2") (pinfunction "2_2") (pintype "passive"))
    )
    (net (code "184") (name "Net-(LTC3-S10)") (class "Default")
      (node (ref "LTC3") (pin "P$7") (pinfunction "S10_P$7") (pintype "bidirectional"))
      (node (ref "LTC3_S10") (pin "P$1") (pinfunction "TP_P$1") (pintype "input"))
      (node (ref "R114") (pin "2") (pinfunction "2_2") (pintype "passive"))
    )
    (net (code "185") (name "Net-(LTC3-TOS)") (class "Default")
      (node (ref "LTC3") (pin "P$33") (pinfunction "TOS_P$33") (pintype "bidirectional"))
      (node (ref "R155") (pin "1") (pinfunction "1_1") (pintype "passive"))
    )
    (net (code "186") (name "Net-(LTC3-V+)") (class "Default")
      (node (ref "C45") (pin "1") (pinfunction "1_1") (pintype "passive"))
      (node (ref "LTC3") (pin "P$1") (pinfunction "V+_P$1") (pintype "bidirectional"))
      (node (ref "LTC3_V+") (pin "P$1") (pinfunction "TP_P$1") (pintype "input"))
      (node (ref "R153") (pin "2") (pinfunction "2_2") (pintype "passive"))
    )
    (net (code "187") (name "Net-(LTC3-VREF)") (class "Default")
      (node (ref "C47") (pin "1") (pinfunction "1_1") (pintype "passive"))
      (node (ref "LTC3") (pin "P$31") (pinfunction "VREF_P$31") (pintype "bidirectional"))
    )
    (net (code "188") (name "Net-(LTC3-WDTB)") (class "Default")
      (node (ref "LTC3") (pin "P$34") (pinfunction "WDTB_P$34") (pintype "bidirectional"))
      (node (ref "U$10") (pin "2") (pinfunction "2_2") (pintype "passive"))
    )
    (net (code "189") (name "Net-(Q3-D)") (class "Default")
      (node (ref "Q3") (pin "3") (pinfunction "D_3") (pintype "passive"))
      (node (ref "R12") (pin "2") (pinfunction "2_2") (pintype "passive"))
    )
    (net (code "190") (name "Net-(Q3-G)") (class "Default")
      (node (ref "Q3") (pin "1") (pinfunction "G_1") (pintype "passive"))
      (node (ref "R11") (pin "1") (pinfunction "1_1") (pintype "passive"))
    )
    (net (code "191") (name "Net-(Q3-S)") (class "Default")
      (node (ref "L5") (pin "2") (pinfunction "2_2") (pintype "passive"))
      (node (ref "Q3") (pin "2") (pinfunction "S_2") (pintype "passive"))
      (node (ref "R10") (pin "1") (pinfunction "1_1") (pintype "passive"))
    )
    (net (code "192") (name "Net-(Q4-D)") (class "Default")
      (node (ref "Q4") (pin "3") (pinfunction "D_3") (pintype "passive"))
      (node (ref "R16") (pin "2") (pinfunction "2_2") (pintype "passive"))
    )
    (net (code "193") (name "Net-(Q4-G)") (class "Default")
      (node (ref "Q4") (pin "1") (pinfunction "G_1") (pintype "passive"))
      (node (ref "R15") (pin "1") (pinfunction "1_1") (pintype "passive"))
    )
    (net (code "194") (name "Net-(Q4-S)") (class "Default")
      (node (ref "L6") (pin "2") (pinfunction "2_2") (pintype "passive"))
      (node (ref "Q4") (pin "2") (pinfunction "S_2") (pintype "passive"))
      (node (ref "R12") (pin "1") (pinfunction "1_1") (pintype "passive"))
      (node (ref "R14") (pin "1") (pinfunction "1_1") (pintype "passive"))
    )
    (net (code "195") (name "Net-(Q5-D)") (class "Default")
      (node (ref "Q5") (pin "3") (pinfunction "D_3") (pintype "passive"))
      (node (ref "R20") (pin "2") (pinfunction "2_2") (pintype "passive"))
    )
    (net (code "196") (name "Net-(Q5-G)") (class "Default")
      (node (ref "Q5") (pin "1") (pinfunction "G_1") (pintype "passive"))
      (node (ref "R19") (pin "1") (pinfunction "1_1") (pintype "passive"))
    )
    (net (code "197") (name "Net-(Q5-S)") (class "Default")
      (node (ref "L7") (pin "2") (pinfunction "2_2") (pintype "passive"))
      (node (ref "Q5") (pin "2") (pinfunction "S_2") (pintype "passive"))
      (node (ref "R16") (pin "1") (pinfunction "1_1") (pintype "passive"))
      (node (ref "R18") (pin "1") (pinfunction "1_1") (pintype "passive"))
    )
    (net (code "198") (name "Net-(Q6-D)") (class "Default")
      (node (ref "Q6") (pin "3") (pinfunction "D_3") (pintype "passive"))
      (node (ref "R24") (pin "2") (pinfunction "2_2") (pintype "passive"))
    )
    (net (code "199") (name "Net-(Q6-G)") (class "Default")
      (node (ref "Q6") (pin "1") (pinfunction "G_1") (pintype "passive"))
      (node (ref "R23") (pin "1") (pinfunction "1_1") (pintype "passive"))
    )
    (net (code "200") (name "Net-(Q6-S)") (class "Default")
      (node (ref "L8") (pin "2") (pinfunction "2_2") (pintype "passive"))
      (node (ref "Q6") (pin "2") (pinfunction "S_2") (pintype "passive"))
      (node (ref "R20") (pin "1") (pinfunction "1_1") (pintype "passive"))
      (node (ref "R22") (pin "1") (pinfunction "1_1") (pintype "passive"))
    )
    (net (code "201") (name "Net-(Q7-D)") (class "Default")
      (node (ref "Q7") (pin "3") (pinfunction "D_3") (pintype "passive"))
      (node (ref "R28") (pin "2") (pinfunction "2_2") (pintype "passive"))
    )
    (net (code "202") (name "Net-(Q7-G)") (class "Default")
      (node (ref "Q7") (pin "1") (pinfunction "G_1") (pintype "passive"))
      (node (ref "R27") (pin "1") (pinfunction "1_1") (pintype "passive"))
    )
    (net (code "203") (name "Net-(Q7-S)") (class "Default")
      (node (ref "L9") (pin "2") (pinfunction "2_2") (pintype "passive"))
      (node (ref "Q7") (pin "2") (pinfunction "S_2") (pintype "passive"))
      (node (ref "R24") (pin "1") (pinfunction "1_1") (pintype "passive"))
      (node (ref "R26") (pin "1") (pinfunction "1_1") (pintype "passive"))
    )
    (net (code "204") (name "Net-(Q8-D)") (class "Default")
      (node (ref "Q8") (pin "3") (pinfunction "D_3") (pintype "passive"))
      (node (ref "R32") (pin "2") (pinfunction "2_2") (pintype "passive"))
    )
    (net (code "205") (name "Net-(Q8-G)") (class "Default")
      (node (ref "Q8") (pin "1") (pinfunction "G_1") (pintype "passive"))
      (node (ref "R31") (pin "1") (pinfunction "1_1") (pintype "passive"))
    )
    (net (code "206") (name "Net-(Q8-S)") (class "Default")
      (node (ref "L10") (pin "2") (pinfunction "2_2") (pintype "passive"))
      (node (ref "Q8") (pin "2") (pinfunction "S_2") (pintype "passive"))
      (node (ref "R28") (pin "1") (pinfunction "1_1") (pintype "passive"))
      (node (ref "R30") (pin "1") (pinfunction "1_1") (pintype "passive"))
    )
    (net (code "207") (name "Net-(Q9-D)") (class "Default")
      (node (ref "Q9") (pin "3") (pinfunction "D_3") (pintype "passive"))
      (node (ref "R36") (pin "2") (pinfunction "2_2") (pintype "passive"))
    )
    (net (code "208") (name "Net-(Q9-G)") (class "Default")
      (node (ref "Q9") (pin "1") (pinfunction "G_1") (pintype "passive"))
      (node (ref "R35") (pin "1") (pinfunction "1_1") (pintype "passive"))
    )
    (net (code "209") (name "Net-(Q9-S)") (class "Default")
      (node (ref "L11") (pin "2") (pinfunction "2_2") (pintype "passive"))
      (node (ref "Q9") (pin "2") (pinfunction "S_2") (pintype "passive"))
      (node (ref "R32") (pin "1") (pinfunction "1_1") (pintype "passive"))
      (node (ref "R34") (pin "1") (pinfunction "1_1") (pintype "passive"))
    )
    (net (code "210") (name "Net-(Q10-D)") (class "Default")
      (node (ref "Q10") (pin "3") (pinfunction "D_3") (pintype "passive"))
      (node (ref "R40") (pin "2") (pinfunction "2_2") (pintype "passive"))
    )
    (net (code "211") (name "Net-(Q10-G)") (class "Default")
      (node (ref "Q10") (pin "1") (pinfunction "G_1") (pintype "passive"))
      (node (ref "R39") (pin "1") (pinfunction "1_1") (pintype "passive"))
    )
    (net (code "212") (name "Net-(Q10-S)") (class "Default")
      (node (ref "L12") (pin "2") (pinfunction "2_2") (pintype "passive"))
      (node (ref "Q10") (pin "2") (pinfunction "S_2") (pintype "passive"))
      (node (ref "R36") (pin "1") (pinfunction "1_1") (pintype "passive"))
      (node (ref "R38") (pin "1") (pinfunction "1_1") (pintype "passive"))
    )
    (net (code "213") (name "Net-(Q11-D)") (class "Default")
      (node (ref "Q11") (pin "3") (pinfunction "D_3") (pintype "passive"))
      (node (ref "R44") (pin "2") (pinfunction "2_2") (pintype "passive"))
    )
    (net (code "214") (name "Net-(Q11-G)") (class "Default")
      (node (ref "Q11") (pin "1") (pinfunction "G_1") (pintype "passive"))
      (node (ref "R43") (pin "1") (pinfunction "1_1") (pintype "passive"))
    )
    (net (code "215") (name "Net-(Q11-S)") (class "Default")
      (node (ref "L13") (pin "2") (pinfunction "2_2") (pintype "passive"))
      (node (ref "Q11") (pin "2") (pinfunction "S_2") (pintype "passive"))
      (node (ref "R40") (pin "1") (pinfunction "1_1") (pintype "passive"))
      (node (ref "R42") (pin "1") (pinfunction "1_1") (pintype "passive"))
    )
    (net (code "216") (name "Net-(Q12-D)") (class "Default")
      (node (ref "Q12") (pin "3") (pinfunction "D_3") (pintype "passive"))
      (node (ref "R48") (pin "2") (pinfunction "2_2") (pintype "passive"))
    )
    (net (code "217") (name "Net-(Q12-G)") (class "Default")
      (node (ref "Q12") (pin "1") (pinfunction "G_1") (pintype "passive"))
      (node (ref "R47") (pin "1") (pinfunction "1_1") (pintype "passive"))
    )
    (net (code "218") (name "Net-(Q12-S)") (class "Default")
      (node (ref "L14") (pin "2") (pinfunction "2_2") (pintype "passive"))
      (node (ref "Q12") (pin "2") (pinfunction "S_2") (pintype "passive"))
      (node (ref "R44") (pin "1") (pinfunction "1_1") (pintype "passive"))
      (node (ref "R46") (pin "1") (pinfunction "1_1") (pintype "passive"))
    )
    (net (code "219") (name "Net-(Q15-D)") (class "Default")
      (node (ref "Q15") (pin "3") (pinfunction "D_3") (pintype "passive"))
      (node (ref "R64") (pin "2") (pinfunction "2_2") (pintype "passive"))
    )
    (net (code "220") (name "Net-(Q15-G)") (class "Default")
      (node (ref "Q15") (pin "1") (pinfunction "G_1") (pintype "passive"))
      (node (ref "R63") (pin "1") (pinfunction "1_1") (pintype "passive"))
    )
    (net (code "221") (name "Net-(Q15-S)") (class "Default")
      (node (ref "L18") (pin "2") (pinfunction "2_2") (pintype "passive"))
      (node (ref "Q15") (pin "2") (pinfunction "S_2") (pintype "passive"))
      (node (ref "R62") (pin "1") (pinfunction "1_1") (pintype "passive"))
    )
    (net (code "222") (name "Net-(Q16-D)") (class "Default")
      (node (ref "Q16") (pin "3") (pinfunction "D_3") (pintype "passive"))
      (node (ref "R68") (pin "2") (pinfunction "2_2") (pintype "passive"))
    )
    (net (code "223") (name "Net-(Q16-G)") (class "Default")
      (node (ref "Q16") (pin "1") (pinfunction "G_1") (pintype "passive"))
      (node (ref "R67") (pin "1") (pinfunction "1_1") (pintype "passive"))
    )
    (net (code "224") (name "Net-(Q16-S)") (class "Default")
      (node (ref "L19") (pin "2") (pinfunction "2_2") (pintype "passive"))
      (node (ref "Q16") (pin "2") (pinfunction "S_2") (pintype "passive"))
      (node (ref "R64") (pin "1") (pinfunction "1_1") (pintype "passive"))
      (node (ref "R66") (pin "1") (pinfunction "1_1") (pintype "passive"))
    )
    (net (code "225") (name "Net-(Q17-D)") (class "Default")
      (node (ref "Q17") (pin "3") (pinfunction "D_3") (pintype "passive"))
      (node (ref "R72") (pin "2") (pinfunction "2_2") (pintype "passive"))
    )
    (net (code "226") (name "Net-(Q17-G)") (class "Default")
      (node (ref "Q17") (pin "1") (pinfunction "G_1") (pintype "passive"))
      (node (ref "R71") (pin "1") (pinfunction "1_1") (pintype "passive"))
    )
    (net (code "227") (name "Net-(Q17-S)") (class "Default")
      (node (ref "L20") (pin "2") (pinfunction "2_2") (pintype "passive"))
      (node (ref "Q17") (pin "2") (pinfunction "S_2") (pintype "passive"))
      (node (ref "R68") (pin "1") (pinfunction "1_1") (pintype "passive"))
      (node (ref "R70") (pin "1") (pinfunction "1_1") (pintype "passive"))
    )
    (net (code "228") (name "Net-(Q18-D)") (class "Default")
      (node (ref "Q18") (pin "3") (pinfunction "D_3") (pintype "passive"))
      (node (ref "R76") (pin "2") (pinfunction "2_2") (pintype "passive"))
    )
    (net (code "229") (name "Net-(Q18-G)") (class "Default")
      (node (ref "Q18") (pin "1") (pinfunction "G_1") (pintype "passive"))
      (node (ref "R75") (pin "1") (pinfunction "1_1") (pintype "passive"))
    )
    (net (code "230") (name "Net-(Q18-S)") (class "Default")
      (node (ref "L21") (pin "2") (pinfunction "2_2") (pintype "passive"))
      (node (ref "Q18") (pin "2") (pinfunction "S_2") (pintype "passive"))
      (node (ref "R72") (pin "1") (pinfunction "1_1") (pintype "passive"))
      (node (ref "R74") (pin "1") (pinfunction "1_1") (pintype "passive"))
    )
    (net (code "231") (name "Net-(Q19-D)") (class "Default")
      (node (ref "Q19") (pin "3") (pinfunction "D_3") (pintype "passive"))
      (node (ref "R80") (pin "2") (pinfunction "2_2") (pintype "passive"))
    )
    (net (code "232") (name "Net-(Q19-G)") (class "Default")
      (node (ref "Q19") (pin "1") (pinfunction "G_1") (pintype "passive"))
      (node (ref "R79") (pin "1") (pinfunction "1_1") (pintype "passive"))
    )
    (net (code "233") (name "Net-(Q19-S)") (class "Default")
      (node (ref "L22") (pin "2") (pinfunction "2_2") (pintype "passive"))
      (node (ref "Q19") (pin "2") (pinfunction "S_2") (pintype "passive"))
      (node (ref "R76") (pin "1") (pinfunction "1_1") (pintype "passive"))
      (node (ref "R78") (pin "1") (pinfunction "1_1") (pintype "passive"))
    )
    (net (code "234") (name "Net-(Q20-D)") (class "Default")
      (node (ref "Q20") (pin "3") (pinfunction "D_3") (pintype "passive"))
      (node (ref "R84") (pin "2") (pinfunction "2_2") (pintype "passive"))
    )
    (net (code "235") (name "Net-(Q20-G)") (class "Default")
      (node (ref "Q20") (pin "1") (pinfunction "G_1") (pintype "passive"))
      (node (ref "R83") (pin "1") (pinfunction "1_1") (pintype "passive"))
    )
    (net (code "236") (name "Net-(Q20-S)") (class "Default")
      (node (ref "L23") (pin "2") (pinfunction "2_2") (pintype "passive"))
      (node (ref "Q20") (pin "2") (pinfunction "S_2") (pintype "passive"))
      (node (ref "R80") (pin "1") (pinfunction "1_1") (pintype "passive"))
      (node (ref "R82") (pin "1") (pinfunction "1_1") (pintype "passive"))
    )
    (net (code "237") (name "Net-(Q21-D)") (class "Default")
      (node (ref "Q21") (pin "3") (pinfunction "D_3") (pintype "passive"))
      (node (ref "R88") (pin "2") (pinfunction "2_2") (pintype "passive"))
    )
    (net (code "238") (name "Net-(Q21-G)") (class "Default")
      (node (ref "Q21") (pin "1") (pinfunction "G_1") (pintype "passive"))
      (node (ref "R87") (pin "1") (pinfunction "1_1") (pintype "passive"))
    )
    (net (code "239") (name "Net-(Q21-S)") (class "Default")
      (node (ref "L24") (pin "2") (pinfunction "2_2") (pintype "passive"))
      (node (ref "Q21") (pin "2") (pinfunction "S_2") (pintype "passive"))
      (node (ref "R84") (pin "1") (pinfunction "1_1") (pintype "passive"))
      (node (ref "R86") (pin "1") (pinfunction "1_1") (pintype "passive"))
    )
    (net (code "240") (name "Net-(Q22-D)") (class "Default")
      (node (ref "Q22") (pin "3") (pinfunction "D_3") (pintype "passive"))
      (node (ref "R92") (pin "2") (pinfunction "2_2") (pintype "passive"))
    )
    (net (code "241") (name "Net-(Q22-G)") (class "Default")
      (node (ref "Q22") (pin "1") (pinfunction "G_1") (pintype "passive"))
      (node (ref "R91") (pin "1") (pinfunction "1_1") (pintype "passive"))
    )
    (net (code "242") (name "Net-(Q22-S)") (class "Default")
      (node (ref "L25") (pin "2") (pinfunction "2_2") (pintype "passive"))
      (node (ref "Q22") (pin "2") (pinfunction "S_2") (pintype "passive"))
      (node (ref "R88") (pin "1") (pinfunction "1_1") (pintype "passive"))
      (node (ref "R90") (pin "1") (pinfunction "1_1") (pintype "passive"))
    )
    (net (code "243") (name "Net-(Q23-D)") (class "Default")
      (node (ref "Q23") (pin "3") (pinfunction "D_3") (pintype "passive"))
      (node (ref "R96") (pin "2") (pinfunction "2_2") (pintype "passive"))
    )
    (net (code "244") (name "Net-(Q23-G)") (class "Default")
      (node (ref "Q23") (pin "1") (pinfunction "G_1") (pintype "passive"))
      (node (ref "R95") (pin "1") (pinfunction "1_1") (pintype "passive"))
    )
    (net (code "245") (name "Net-(Q23-S)") (class "Default")
      (node (ref "L26") (pin "2") (pinfunction "2_2") (pintype "passive"))
      (node (ref "Q23") (pin "2") (pinfunction "S_2") (pintype "passive"))
      (node (ref "R92") (pin "1") (pinfunction "1_1") (pintype "passive"))
      (node (ref "R94") (pin "1") (pinfunction "1_1") (pintype "passive"))
    )
    (net (code "246") (name "Net-(Q24-D)") (class "Default")
      (node (ref "Q24") (pin "3") (pinfunction "D_3") (pintype "passive"))
      (node (ref "R100") (pin "2") (pinfunction "2_2") (pintype "passive"))
    )
    (net (code "247") (name "Net-(Q24-G)") (class "Default")
      (node (ref "Q24") (pin "1") (pinfunction "G_1") (pintype "passive"))
      (node (ref "R99") (pin "1") (pinfunction "1_1") (pintype "passive"))
    )
    (net (code "248") (name "Net-(Q24-S)") (class "Default")
      (node (ref "L27") (pin "2") (pinfunction "2_2") (pintype "passive"))
      (node (ref "Q24") (pin "2") (pinfunction "S_2") (pintype "passive"))
      (node (ref "R96") (pin "1") (pinfunction "1_1") (pintype "passive"))
      (node (ref "R98") (pin "1") (pinfunction "1_1") (pintype "passive"))
    )
    (net (code "249") (name "Net-(Q27-D)") (class "Default")
      (node (ref "Q27") (pin "3") (pinfunction "D_3") (pintype "passive"))
      (node (ref "R115") (pin "2") (pinfunction "2_2") (pintype "passive"))
    )
    (net (code "250") (name "Net-(Q27-G)") (class "Default")
      (node (ref "Q27") (pin "1") (pinfunction "G_1") (pintype "passive"))
      (node (ref "R114") (pin "1") (pinfunction "1_1") (pintype "passive"))
    )
    (net (code "251") (name "Net-(Q27-S)") (class "Default")
      (node (ref "L33") (pin "2") (pinfunction "2_2") (pintype "passive"))
      (node (ref "Q27") (pin "2") (pinfunction "S_2") (pintype "passive"))
      (node (ref "R113") (pin "1") (pinfunction "1_1") (pintype "passive"))
    )
    (net (code "252") (name "Net-(Q28-D)") (class "Default")
      (node (ref "Q28") (pin "3") (pinfunction "D_3") (pintype "passive"))
      (node (ref "R119") (pin "2") (pinfunction "2_2") (pintype "passive"))
    )
    (net (code "253") (name "Net-(Q28-G)") (class "Default")
      (node (ref "Q28") (pin "1") (pinfunction "G_1") (pintype "passive"))
      (node (ref "R118") (pin "1") (pinfunction "1_1") (pintype "passive"))
    )
    (net (code "254") (name "Net-(Q28-S)") (class "Default")
      (node (ref "L34") (pin "2") (pinfunction "2_2") (pintype "passive"))
      (node (ref "Q28") (pin "2") (pinfunction "S_2") (pintype "passive"))
      (node (ref "R115") (pin "1") (pinfunction "1_1") (pintype "passive"))
      (node (ref "R117") (pin "1") (pinfunction "1_1") (pintype "passive"))
    )
    (net (code "255") (name "Net-(Q29-D)") (class "Default")
      (node (ref "Q29") (pin "3") (pinfunction "D_3") (pintype "passive"))
      (node (ref "R123") (pin "2") (pinfunction "2_2") (pintype "passive"))
    )
    (net (code "256") (name "Net-(Q29-G)") (class "Default")
      (node (ref "Q29") (pin "1") (pinfunction "G_1") (pintype "passive"))
      (node (ref "R122") (pin "1") (pinfunction "1_1") (pintype "passive"))
    )
    (net (code "257") (name "Net-(Q29-S)") (class "Default")
      (node (ref "L35") (pin "2") (pinfunction "2_2") (pintype "passive"))
      (node (ref "Q29") (pin "2") (pinfunction "S_2") (pintype "passive"))
      (node (ref "R119") (pin "1") (pinfunction "1_1") (pintype "passive"))
      (node (ref "R121") (pin "1") (pinfunction "1_1") (pintype "passive"))
    )
    (net (code "258") (name "Net-(Q30-D)") (class "Default")
      (node (ref "Q30") (pin "3") (pinfunction "D_3") (pintype "passive"))
      (node (ref "R127") (pin "2") (pinfunction "2_2") (pintype "passive"))
    )
    (net (code "259") (name "Net-(Q30-G)") (class "Default")
      (node (ref "Q30") (pin "1") (pinfunction "G_1") (pintype "passive"))
      (node (ref "R126") (pin "1") (pinfunction "1_1") (pintype "passive"))
    )
    (net (code "260") (name "Net-(Q30-S)") (class "Default")
      (node (ref "L36") (pin "2") (pinfunction "2_2") (pintype "passive"))
      (node (ref "Q30") (pin "2") (pinfunction "S_2") (pintype "passive"))
      (node (ref "R123") (pin "1") (pinfunction "1_1") (pintype "passive"))
      (node (ref "R125") (pin "1") (pinfunction "1_1") (pintype "passive"))
    )
    (net (code "261") (name "Net-(Q31-D)") (class "Default")
      (node (ref "Q31") (pin "3") (pinfunction "D_3") (pintype "passive"))
      (node (ref "R131") (pin "2") (pinfunction "2_2") (pintype "passive"))
    )
    (net (code "262") (name "Net-(Q31-G)") (class "Default")
      (node (ref "Q31") (pin "1") (pinfunction "G_1") (pintype "passive"))
      (node (ref "R130") (pin "1") (pinfunction "1_1") (pintype "passive"))
    )
    (net (code "263") (name "Net-(Q31-S)") (class "Default")
      (node (ref "L37") (pin "2") (pinfunction "2_2") (pintype "passive"))
      (node (ref "Q31") (pin "2") (pinfunction "S_2") (pintype "passive"))
      (node (ref "R127") (pin "1") (pinfunction "1_1") (pintype "passive"))
      (node (ref "R129") (pin "1") (pinfunction "1_1") (pintype "passive"))
    )
    (net (code "264") (name "Net-(Q32-D)") (class "Default")
      (node (ref "Q32") (pin "3") (pinfunction "D_3") (pintype "passive"))
      (node (ref "R135") (pin "2") (pinfunction "2_2") (pintype "passive"))
    )
    (net (code "265") (name "Net-(Q32-G)") (class "Default")
      (node (ref "Q32") (pin "1") (pinfunction "G_1") (pintype "passive"))
      (node (ref "R134") (pin "1") (pinfunction "1_1") (pintype "passive"))
    )
    (net (code "266") (name "Net-(Q32-S)") (class "Default")
      (node (ref "L38") (pin "2") (pinfunction "2_2") (pintype "passive"))
      (node (ref "Q32") (pin "2") (pinfunction "S_2") (pintype "passive"))
      (node (ref "R131") (pin "1") (pinfunction "1_1") (pintype "passive"))
      (node (ref "R133") (pin "1") (pinfunction "1_1") (pintype "passive"))
    )
    (net (code "267") (name "Net-(Q33-D)") (class "Default")
      (node (ref "Q33") (pin "3") (pinfunction "D_3") (pintype "passive"))
      (node (ref "R139") (pin "2") (pinfunction "2_2") (pintype "passive"))
    )
    (net (code "268") (name "Net-(Q33-G)") (class "Default")
      (node (ref "Q33") (pin "1") (pinfunction "G_1") (pintype "passive"))
      (node (ref "R138") (pin "1") (pinfunction "1_1") (pintype "passive"))
    )
    (net (code "269") (name "Net-(Q33-S)") (class "Default")
      (node (ref "L39") (pin "2") (pinfunction "2_2") (pintype "passive"))
      (node (ref "Q33") (pin "2") (pinfunction "S_2") (pintype "passive"))
      (node (ref "R135") (pin "1") (pinfunction "1_1") (pintype "passive"))
      (node (ref "R137") (pin "1") (pinfunction "1_1") (pintype "passive"))
    )
    (net (code "270") (name "Net-(Q34-D)") (class "Default")
      (node (ref "Q34") (pin "3") (pinfunction "D_3") (pintype "passive"))
      (node (ref "R143") (pin "2") (pinfunction "2_2") (pintype "passive"))
    )
    (net (code "271") (name "Net-(Q34-G)") (class "Default")
      (node (ref "Q34") (pin "1") (pinfunction "G_1") (pintype "passive"))
      (node (ref "R142") (pin "1") (pinfunction "1_1") (pintype "passive"))
    )
    (net (code "272") (name "Net-(Q34-S)") (class "Default")
      (node (ref "L40") (pin "2") (pinfunction "2_2") (pintype "passive"))
      (node (ref "Q34") (pin "2") (pinfunction "S_2") (pintype "passive"))
      (node (ref "R139") (pin "1") (pinfunction "1_1") (pintype "passive"))
      (node (ref "R141") (pin "1") (pinfunction "1_1") (pintype "passive"))
    )
    (net (code "273") (name "Net-(Q35-D)") (class "Default")
      (node (ref "Q35") (pin "3") (pinfunction "D_3") (pintype "passive"))
      (node (ref "R147") (pin "2") (pinfunction "2_2") (pintype "passive"))
    )
    (net (code "274") (name "Net-(Q35-G)") (class "Default")
      (node (ref "Q35") (pin "1") (pinfunction "G_1") (pintype "passive"))
      (node (ref "R146") (pin "1") (pinfunction "1_1") (pintype "passive"))
    )
    (net (code "275") (name "Net-(Q35-S)") (class "Default")
      (node (ref "L41") (pin "2") (pinfunction "2_2") (pintype "passive"))
      (node (ref "Q35") (pin "2") (pinfunction "S_2") (pintype "passive"))
      (node (ref "R143") (pin "1") (pinfunction "1_1") (pintype "passive"))
      (node (ref "R145") (pin "1") (pinfunction "1_1") (pintype "passive"))
    )
    (net (code "276") (name "Net-(Q36-D)") (class "Default")
      (node (ref "Q36") (pin "3") (pinfunction "D_3") (pintype "passive"))
      (node (ref "R151") (pin "2") (pinfunction "2_2") (pintype "passive"))
    )
    (net (code "277") (name "Net-(Q36-G)") (class "Default")
      (node (ref "Q36") (pin "1") (pinfunction "G_1") (pintype "passive"))
      (node (ref "R150") (pin "1") (pinfunction "1_1") (pintype "passive"))
    )
    (net (code "278") (name "Net-(Q36-S)") (class "Default")
      (node (ref "L42") (pin "2") (pinfunction "2_2") (pintype "passive"))
      (node (ref "Q36") (pin "2") (pinfunction "S_2") (pintype "passive"))
      (node (ref "R147") (pin "1") (pinfunction "1_1") (pintype "passive"))
      (node (ref "R149") (pin "1") (pinfunction "1_1") (pintype "passive"))
    )
    (net (code "279") (name "Net-(R164-Pad1)") (class "Default")
      (node (ref "R164") (pin "1") (pinfunction "1_1") (pintype "passive"))
      (node (ref "U$10") (pin "3") (pinfunction "3_3") (pintype "passive"))
    )
    (net (code "280") (name "Net-(R166-Pad1)") (class "Default")
      (node (ref "R166") (pin "1") (pinfunction "1_1") (pintype "passive"))
      (node (ref "U$9") (pin "3") (pinfunction "3_3") (pintype "passive"))
    )
    (net (code "281") (name "Net-(R168-Pad1)") (class "Default")
      (node (ref "R168") (pin "1") (pinfunction "1_1") (pintype "passive"))
      (node (ref "U$8") (pin "3") (pinfunction "3_3") (pintype "passive"))
    )
    (net (code "282") (name "Net-(S2-P)") (class "Default")
      (node (ref "LED_SWITCH") (pin "1") (pinfunction "1_1") (pintype "passive"))
      (node (ref "R1") (pin "1") (pinfunction "1_1") (pintype "passive"))
      (node (ref "S2") (pin "3") (pinfunction "P_3") (pintype "passive"))
      (node (ref "S2") (pin "4") (pinfunction "P1_4") (pintype "passive"))
    )
    (net (code "283") (name "Net-(T1-D)") (class "Default")
      (node (ref "K1") (pin "2") (pinfunction "2_2") (pintype "passive"))
      (node (ref "T1") (pin "3") (pinfunction "D_3") (pintype "passive"))
    )
    (net (code "284") (name "Net-(U$2-~{MCLR})") (class "Default")
      (node (ref "MCLR") (pin "1") (pinfunction "1_1") (pintype "passive"))
      (node (ref "MCLR") (pin "2") (pinfunction "2_2") (pintype "passive"))
      (node (ref "MCLR") (pin "3") (pinfunction "3_3") (pintype "passive"))
      (node (ref "R53") (pin "2") (pinfunction "2_2") (pintype "passive"))
      (node (ref "U$2") (pin "1") (pinfunction "~{MCLR}_1") (pintype "bidirectional"))
    )
    (net (code "285") (name "Net-(U$8B-2)") (class "Default")
      (node (ref "R5") (pin "2") (pinfunction "2_2") (pintype "passive"))
      (node (ref "U$8") (pin "5") (pinfunction "2_5") (pintype "passive"))
    )
    (net (code "286") (name "Net-(U$9B-2)") (class "Default")
      (node (ref "R104") (pin "2") (pinfunction "2_2") (pintype "passive"))
      (node (ref "U$9") (pin "5") (pinfunction "2_5") (pintype "passive"))
    )
    (net (code "287") (name "Net-(U$10B-2)") (class "Default")
      (node (ref "R155") (pin "2") (pinfunction "2_2") (pintype "passive"))
      (node (ref "U$10") (pin "5") (pinfunction "2_5") (pintype "passive"))
    )
    (net (code "288") (name "OSC1") (class "Default")
      (node (ref "PROGRAM") (pin "1") (pinfunction "S_1") (pintype "passive"))
      (node (ref "U$2") (pin "9") (pinfunction "OSC1_9") (pintype "bidirectional"))
      (node (ref "U$3") (pin "3") (pinfunction "OUT_3") (pintype "output"))
    )
    (net (code "289") (name "PE") (class "Default")
      (node (ref "C35") (pin "2") (pinfunction "2_2") (pintype "passive"))
      (node (ref "C36") (pin "2") (pinfunction "2_2") (pintype "passive"))
      (node (ref "C37") (pin "2") (pinfunction "2_2") (pintype "passive"))
      (node (ref "C38") (pin "2") (pinfunction "2_2") (pintype "passive"))
      (node (ref "C39") (pin "2") (pinfunction "2_2") (pintype "passive"))
      (node (ref "C40") (pin "2") (pinfunction "2_2") (pintype "passive"))
      (node (ref "C41") (pin "2") (pinfunction "2_2") (pintype "passive"))
      (node (ref "C42") (pin "2") (pinfunction "2_2") (pintype "passive"))
      (node (ref "C43") (pin "2") (pinfunction "2_2") (pintype "passive"))
      (node (ref "C44") (pin "2") (pinfunction "2_2") (pintype "passive"))
      (node (ref "C45") (pin "2") (pinfunction "2_2") (pintype "passive"))
      (node (ref "C46") (pin "2") (pinfunction "2_2") (pintype "passive"))
      (node (ref "C47") (pin "2") (pinfunction "2_2") (pintype "passive"))
      (node (ref "D43") (pin "A") (pinfunction "A_A") (pintype "passive"))
      (node (ref "D44") (pin "A") (pinfunction "A_A") (pintype "passive"))
      (node (ref "D45") (pin "A") (pinfunction "A_A") (pintype "passive"))
      (node (ref "IC3_") (pin "15") (pinfunction "GND2_15") (pintype "power_in"))
      (node (ref "IC3_") (pin "9") (pinfunction "GND2_9") (pintype "power_in"))
      (node (ref "L44") (pin "2") (pinfunction "2_2") (pintype "passive"))
      (node (ref "LTC3") (pin "P$27") (pinfunction "V-_P$27") (pintype "bidirectional"))
      (node (ref "LTC3") (pin "P$28") (pinfunction "NC_P$28") (pintype "bidirectional"))
      (node (ref "LTC3") (pin "P$29") (pinfunction "V_TEMP1_P$29") (pintype "bidirectional"))
      (node (ref "LTC3") (pin "P$30") (pinfunction "V_TEMP2_P$30") (pintype "bidirectional"))
      (node (ref "LTC3") (pin "P$35") (pinfunction "GPIO1_P$35") (pintype "bidirectional"))
      (node (ref "LTC3") (pin "P$36") (pinfunction "GPIO2_P$36") (pintype "bidirectional"))
      (node (ref "LTC3_V-") (pin "P$1") (pinfunction "TP_P$1") (pintype "input"))
      (node (ref "U$10") (pin "1") (pinfunction "1_1") (pintype "passive"))
      (node (ref "U$10") (pin "10") (pinfunction "1_10") (pintype "passive"))
      (node (ref "U$10") (pin "13") (pinfunction "1_13") (pintype "passive"))
      (node (ref "U$10") (pin "16") (pinfunction "1_16") (pintype "passive"))
      (node (ref "U$10") (pin "4") (pinfunction "1_4") (pintype "passive"))
      (node (ref "U$10") (pin "7") (pinfunction "1_7") (pintype "passive"))
    )
    (net (code "290") (name "PGEC1") (class "Default")
      (node (ref "PROGRAM") (pin "2") (pinfunction "S_2") (pintype "passive"))
      (node (ref "SV3") (pin "7") (pinfunction "7_7") (pintype "passive"))
      (node (ref "SV3") (pin "8") (pinfunction "8_8") (pintype "passive"))
      (node (ref "SV4") (pin "7") (pinfunction "7_7") (pintype "passive"))
      (node (ref "SV4") (pin "8") (pinfunction "8_8") (pintype "passive"))
      (node (ref "U$2") (pin "5") (pinfunction "PGEC1/RB1_5") (pintype "bidirectional"))
    )
    (net (code "291") (name "PGED1") (class "Default")
      (node (ref "PROGRAM") (pin "3") (pinfunction "S_3") (pintype "passive"))
      (node (ref "SV3") (pin "5") (pinfunction "5_5") (pintype "passive"))
      (node (ref "SV3") (pin "6") (pinfunction "6_6") (pintype "passive"))
      (node (ref "SV4") (pin "5") (pinfunction "5_5") (pintype "passive"))
      (node (ref "SV4") (pin "6") (pinfunction "6_6") (pintype "passive"))
      (node (ref "U$2") (pin "4") (pinfunction "PGED1/RB0_4") (pintype "bidirectional"))
    )
    (net (code "292") (name "RELAY") (class "Default")
      (node (ref "SV3") (pin "15") (pinfunction "15_15") (pintype "passive"))
      (node (ref "SV3") (pin "16") (pinfunction "16_16") (pintype "passive"))
      (node (ref "SV4") (pin "15") (pinfunction "15_15") (pintype "passive"))
      (node (ref "SV4") (pin "16") (pinfunction "16_16") (pintype "passive"))
      (node (ref "U$2") (pin "11") (pinfunction "RB4_11") (pintype "bidirectional"))
    )
    (net (code "293") (name "RELAY_1") (class "Default")
      (node (ref "R2") (pin "2") (pinfunction "2_2") (pintype "passive"))
      (node (ref "RELAY") (pin "1") (pinfunction "1_1") (pintype "passive"))
      (node (ref "RELAY") (pin "2") (pinfunction "2_2") (pintype "passive"))
      (node (ref "RELAY") (pin "3") (pinfunction "3_3") (pintype "passive"))
      (node (ref "T1") (pin "1") (pinfunction "G_1") (pintype "passive"))
    )
    (net (code "294") (name "RX") (class "Default")
      (node (ref "SV3") (pin "33") (pinfunction "33_33") (pintype "passive"))
      (node (ref "SV3") (pin "34") (pinfunction "34_34") (pintype "passive"))
      (node (ref "SV4") (pin "33") (pinfunction "33_33") (pintype "passive"))
      (node (ref "SV4") (pin "34") (pinfunction "34_34") (pintype "passive"))
      (node (ref "U$2") (pin "18") (pinfunction "RB9_18") (pintype "bidirectional"))
    )
    (net (code "295") (name "SCK") (class "Default")
      (node (ref "SV3") (pin "11") (pinfunction "11_11") (pintype "passive"))
      (node (ref "SV3") (pin "12") (pinfunction "12_12") (pintype "passive"))
      (node (ref "SV4") (pin "11") (pinfunction "11_11") (pintype "passive"))
      (node (ref "SV4") (pin "12") (pinfunction "12_12") (pintype "passive"))
      (node (ref "U$2") (pin "7") (pinfunction "RB3_7") (pintype "bidirectional"))
    )
    (net (code "296") (name "SCK_ISO1") (class "Default")
      (node (ref "IC1") (pin "3") (pinfunction "VIA_3") (pintype "input"))
      (node (ref "LTC1_HEAD") (pin "7") (pinfunction "7_7") (pintype "passive"))
      (node (ref "LTC1_HEAD") (pin "8") (pinfunction "8_8") (pintype "passive"))
    )
    (net (code "297") (name "SCK_ISO2") (class "Default")
      (node (ref "IC2_\\") (pin "3") (pinfunction "VIA_3") (pintype "input"))
      (node (ref "LTC2_HEAD") (pin "7") (pinfunction "7_7") (pintype "passive"))
      (node (ref "LTC2_HEAD") (pin "8") (pinfunction "8_8") (pintype "passive"))
    )
    (net (code "298") (name "SCK_ISO3") (class "Default")
      (node (ref "IC3_") (pin "3") (pinfunction "VIA_3") (pintype "input"))
      (node (ref "LTC3_HEAD") (pin "7") (pinfunction "7_7") (pintype "passive"))
      (node (ref "LTC3_HEAD") (pin "8") (pinfunction "8_8") (pintype "passive"))
    )
    (net (code "299") (name "SELECT1") (class "Default")
      (node (ref "RS-485") (pin "1") (pinfunction "1_1") (pintype "passive"))
      (node (ref "RS-485") (pin "2") (pinfunction "2_2") (pintype "passive"))
      (node (ref "U$4") (pin "1") (pinfunction "FAULT_1") (pintype "bidirectional"))
    )
    (net (code "300") (name "SELECT2") (class "Default")
      (node (ref "RS-485") (pin "3") (pinfunction "3_3") (pintype "passive"))
      (node (ref "RS-485") (pin "4") (pinfunction "4_4") (pintype "passive"))
      (node (ref "U$4") (pin "2") (pinfunction "RO_2") (pintype "bidirectional"))
    )
    (net (code "301") (name "SELECT3") (class "Default")
      (node (ref "RS-485") (pin "5") (pinfunction "5_5") (pintype "passive"))
      (node (ref "RS-485") (pin "6") (pinfunction "6_6") (pintype "passive"))
      (node (ref "U$4") (pin "3") (pinfunction "DE/RE_3") (pintype "bidirectional"))
    )
    (net (code "302") (name "SELECT4") (class "Default")
      (node (ref "RS-485") (pin "7") (pinfunction "7_7") (pintype "passive"))
      (node (ref "RS-485") (pin "8") (pinfunction "8_8") (pintype "passive"))
      (node (ref "U$4") (pin "4") (pinfunction "DI_4") (pintype "bidirectional"))
    )
    (net (code "303") (name "TX") (class "Default")
      (node (ref "SV3") (pin "31") (pinfunction "31_31") (pintype "passive"))
      (node (ref "SV3") (pin "32") (pinfunction "32_32") (pintype "passive"))
      (node (ref "SV4") (pin "31") (pinfunction "31_31") (pintype "passive"))
      (node (ref "SV4") (pin "32") (pinfunction "32_32") (pintype "passive"))
      (node (ref "U$2") (pin "21") (pinfunction "RB10_21") (pintype "bidirectional"))
    )
    (net (code "304") (name "V+") (class "Default")
      (node (ref "C2") (pin "1") (pinfunction "1_1") (pintype "passive"))
      (node (ref "IC1") (pin "10") (pinfunction "VE2_10") (pintype "passive"))
      (node (ref "IC1") (pin "16") (pinfunction "VDD2_16") (pintype "power_in"))
      (node (ref "LTC1") (pin "P$32") (pinfunction "VREG_P$32") (pintype "bidirectional"))
      (node (ref "R167") (pin "1") (pinfunction "1_1") (pintype "passive"))
      (node (ref "U$8") (pin "12") (pinfunction "3_12") (pintype "passive"))
      (node (ref "U$8") (pin "15") (pinfunction "3_15") (pintype "passive"))
      (node (ref "U$8") (pin "18") (pinfunction "3_18") (pintype "passive"))
      (node (ref "U$8") (pin "6") (pinfunction "3_6") (pintype "passive"))
      (node (ref "U$8") (pin "9") (pinfunction "3_9") (pintype "passive"))
    )
    (net (code "305") (name "VCC") (class "Default")
      (node (ref "C31") (pin "1") (pinfunction "1_1") (pintype "passive"))
      (node (ref "IC2_\\") (pin "10") (pinfunction "VE2_10") (pintype "passive"))
      (node (ref "IC2_\\") (pin "16") (pinfunction "VDD2_16") (pintype "power_in"))
      (node (ref "LTC2") (pin "P$32") (pinfunction "VREG_P$32") (pintype "bidirectional"))
      (node (ref "R165") (pin "1") (pinfunction "1_1") (pintype "passive"))
      (node (ref "U$9") (pin "12") (pinfunction "3_12") (pintype "passive"))
      (node (ref "U$9") (pin "15") (pinfunction "3_15") (pintype "passive"))
      (node (ref "U$9") (pin "18") (pinfunction "3_18") (pintype "passive"))
      (node (ref "U$9") (pin "6") (pinfunction "3_6") (pintype "passive"))
      (node (ref "U$9") (pin "9") (pinfunction "3_9") (pintype "passive"))
    )
    (net (code "306") (name "VCCIO") (class "Default")
      (node (ref "ADC_POWER") (pin "1") (pinfunction "1_1") (pintype "passive"))
      (node (ref "C49") (pin "1") (pinfunction "1_1") (pintype "passive"))
      (node (ref "U$6") (pin "15") (pinfunction "VREF_15") (pintype "bidirectional"))
      (node (ref "U$7") (pin "2") (pinfunction "OUT_2") (pintype "bidirectional"))
    )
    (net (code "307") (name "VCC{slash}2") (class "Default")
      (node (ref "C46") (pin "1") (pinfunction "1_1") (pintype "passive"))
      (node (ref "IC3_") (pin "10") (pinfunction "VE2_10") (pintype "passive"))
      (node (ref "IC3_") (pin "16") (pinfunction "VDD2_16") (pintype "power_in"))
      (node (ref "LTC3") (pin "P$32") (pinfunction "VREG_P$32") (pintype "bidirectional"))
      (node (ref "R163") (pin "1") (pinfunction "1_1") (pintype "passive"))
      (node (ref "U$10") (pin "12") (pinfunction "3_12") (pintype "passive"))
      (node (ref "U$10") (pin "15") (pinfunction "3_15") (pintype "passive"))
      (node (ref "U$10") (pin "18") (pinfunction "3_18") (pintype "passive"))
      (node (ref "U$10") (pin "6") (pinfunction "3_6") (pintype "passive"))
      (node (ref "U$10") (pin "9") (pinfunction "3_9") (pintype "passive"))
    )
    (net (code "308") (name "WARN1") (class "Default")
      (node (ref "SV3") (pin "1") (pinfunction "1_1") (pintype "passive"))
      (node (ref "SV3") (pin "2") (pinfunction "2_2") (pintype "passive"))
      (node (ref "SV4") (pin "1") (pinfunction "1_1") (pintype "passive"))
      (node (ref "SV4") (pin "2") (pinfunction "2_2") (pintype "passive"))
      (node (ref "U$2") (pin "2") (pinfunction "RA0_2") (pintype "bidirectional"))
    )
    (net (code "309") (name "WARN1_LED") (class "Default")
      (node (ref "LED") (pin "5") (pinfunction "5_5") (pintype "passive"))
      (node (ref "LED") (pin "6") (pinfunction "6_6") (pintype "passive"))
      (node (ref "LED_SWITCH") (pin "2") (pinfunction "2_2") (pintype "passive"))
    )
    (net (code "310") (name "WARN2") (class "Default")
      (node (ref "SV3") (pin "3") (pinfunction "3_3") (pintype "passive"))
      (node (ref "SV3") (pin "4") (pinfunction "4_4") (pintype "passive"))
      (node (ref "SV4") (pin "3") (pinfunction "3_3") (pintype "passive"))
      (node (ref "SV4") (pin "4") (pinfunction "4_4") (pintype "passive"))
      (node (ref "U$2") (pin "3") (pinfunction "RA1_3") (pintype "bidirectional"))
    )
    (net (code "311") (name "WARN2_LED") (class "Default")
      (node (ref "LED") (pin "3") (pinfunction "3_3") (pintype "passive"))
      (node (ref "LED") (pin "4") (pinfunction "4_4") (pintype "passive"))
      (node (ref "R157") (pin "2") (pinfunction "2_2") (pintype "passive"))
    )
    (net (code "312") (name "unconnected-(LTC1-S11-PadP$5)") (class "Default")
      (node (ref "LTC1") (pin "P$5") (pinfunction "S11_P$5") (pintype "bidirectional"))
    )
    (net (code "313") (name "unconnected-(LTC1-S12-PadP$3)") (class "Default")
      (node (ref "LTC1") (pin "P$3") (pinfunction "S12_P$3") (pintype "bidirectional"))
    )
    (net (code "314") (name "unconnected-(LTC2-S11-PadP$5)") (class "Default")
      (node (ref "LTC2") (pin "P$5") (pinfunction "S11_P$5") (pintype "bidirectional"))
    )
    (net (code "315") (name "unconnected-(LTC2-S12-PadP$3)") (class "Default")
      (node (ref "LTC2") (pin "P$3") (pinfunction "S12_P$3") (pintype "bidirectional"))
    )
    (net (code "316") (name "unconnected-(LTC3-S11-PadP$5)") (class "Default")
      (node (ref "LTC3") (pin "P$5") (pinfunction "S11_P$5") (pintype "bidirectional"))
    )
    (net (code "317") (name "unconnected-(LTC3-S12-PadP$3)") (class "Default")
      (node (ref "LTC3") (pin "P$3") (pinfunction "S12_P$3") (pintype "bidirectional"))
    )
    (net (code "318") (name "unconnected-(U$1-IN6-Pad6)") (class "Default")
      (node (ref "U$1") (pin "6") (pinfunction "IN6_6") (pintype "bidirectional"))
    )
    (net (code "319") (name "unconnected-(U$1-IN7-Pad7)") (class "Default")
      (node (ref "U$1") (pin "7") (pinfunction "IN7_7") (pintype "bidirectional"))
    )
    (net (code "320") (name "unconnected-(U$1-IN9-Pad9)") (class "Default")
      (node (ref "U$1") (pin "9") (pinfunction "IN9_9") (pintype "bidirectional"))
    )
    (net (code "321") (name "unconnected-(U$1-IN10-Pad10)") (class "Default")
      (node (ref "U$1") (pin "10") (pinfunction "IN10_10") (pintype "bidirectional"))
    )
    (net (code "322") (name "unconnected-(U$1-IN11-Pad11)") (class "Default")
      (node (ref "U$1") (pin "11") (pinfunction "IN11_11") (pintype "bidirectional"))
    )
    (net (code "323") (name "unconnected-(U$1-IN12-Pad12)") (class "Default")
      (node (ref "U$1") (pin "12") (pinfunction "IN12_12") (pintype "bidirectional"))
    )
    (net (code "324") (name "unconnected-(U$1-IN13-Pad13)") (class "Default")
      (node (ref "U$1") (pin "13") (pinfunction "IN13_13") (pintype "bidirectional"))
    )
    (net (code "325") (name "unconnected-(U$1-IN14-Pad14)") (class "Default")
      (node (ref "U$1") (pin "14") (pinfunction "IN14_14") (pintype "bidirectional"))
    )
    (net (code "326") (name "unconnected-(U$1-IN15-Pad15)") (class "Default")
      (node (ref "U$1") (pin "15") (pinfunction "IN15_15") (pintype "bidirectional"))
    )
    (net (code "327") (name "unconnected-(U$6-CH5-Pad6)") (class "Default")
      (node (ref "U$6") (pin "6") (pinfunction "CH5_6") (pintype "bidirectional"))
    )
    (net (code "328") (name "unconnected-(U$6-CH6-Pad7)") (class "Default")
      (node (ref "U$6") (pin "7") (pinfunction "CH6_7") (pintype "bidirectional"))
    )
    (net (code "329") (name "unconnected-(U$6-CH7-Pad8)") (class "Default")
      (node (ref "U$6") (pin "8") (pinfunction "CH7_8") (pintype "bidirectional"))
    )
  )
)
